# untitled.net
KiCad netlist of a schematic drawn in EAGLE
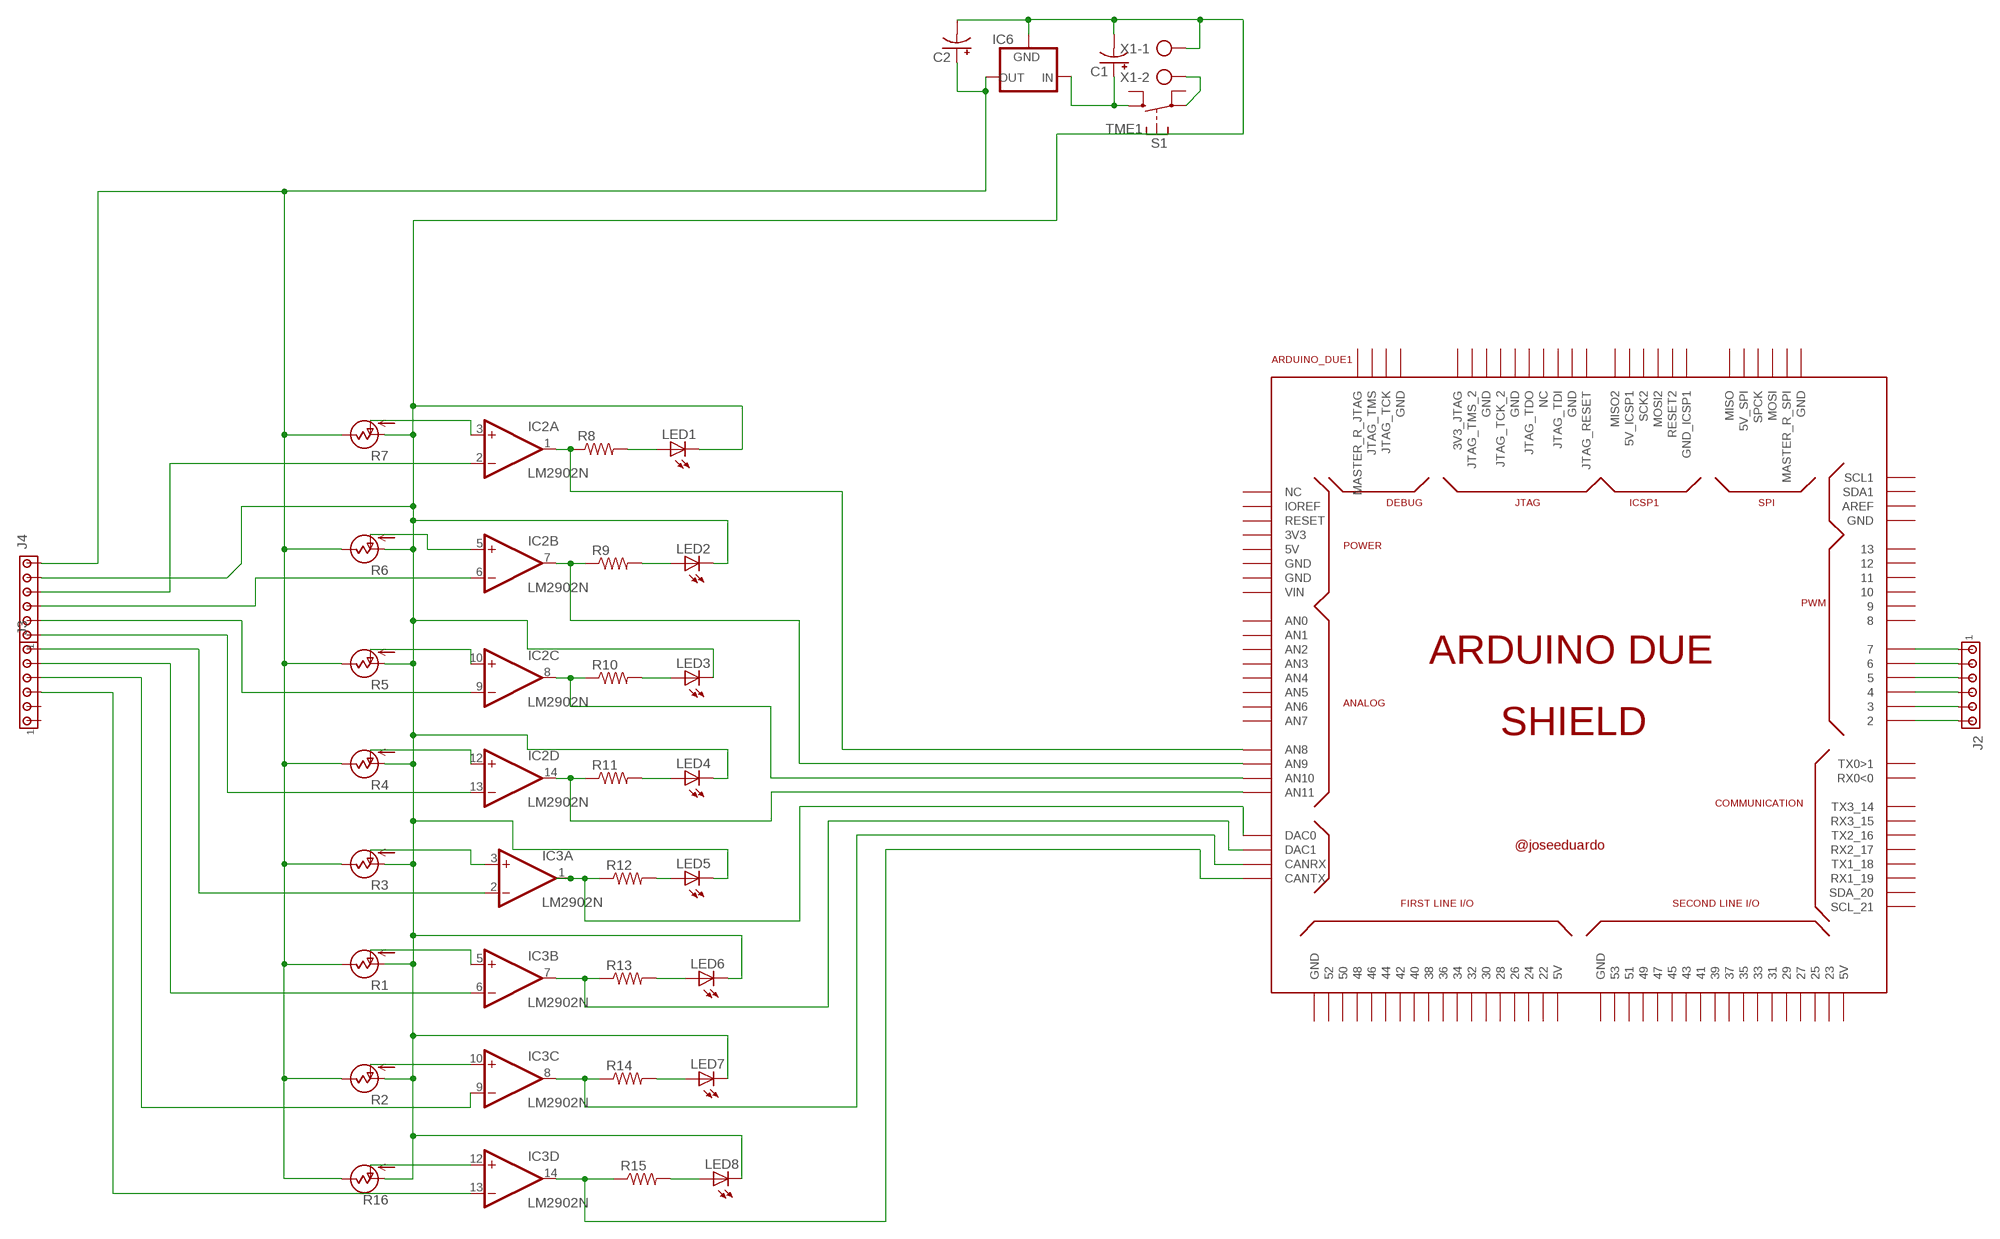
[diagram p0: schematic, sheet 1]
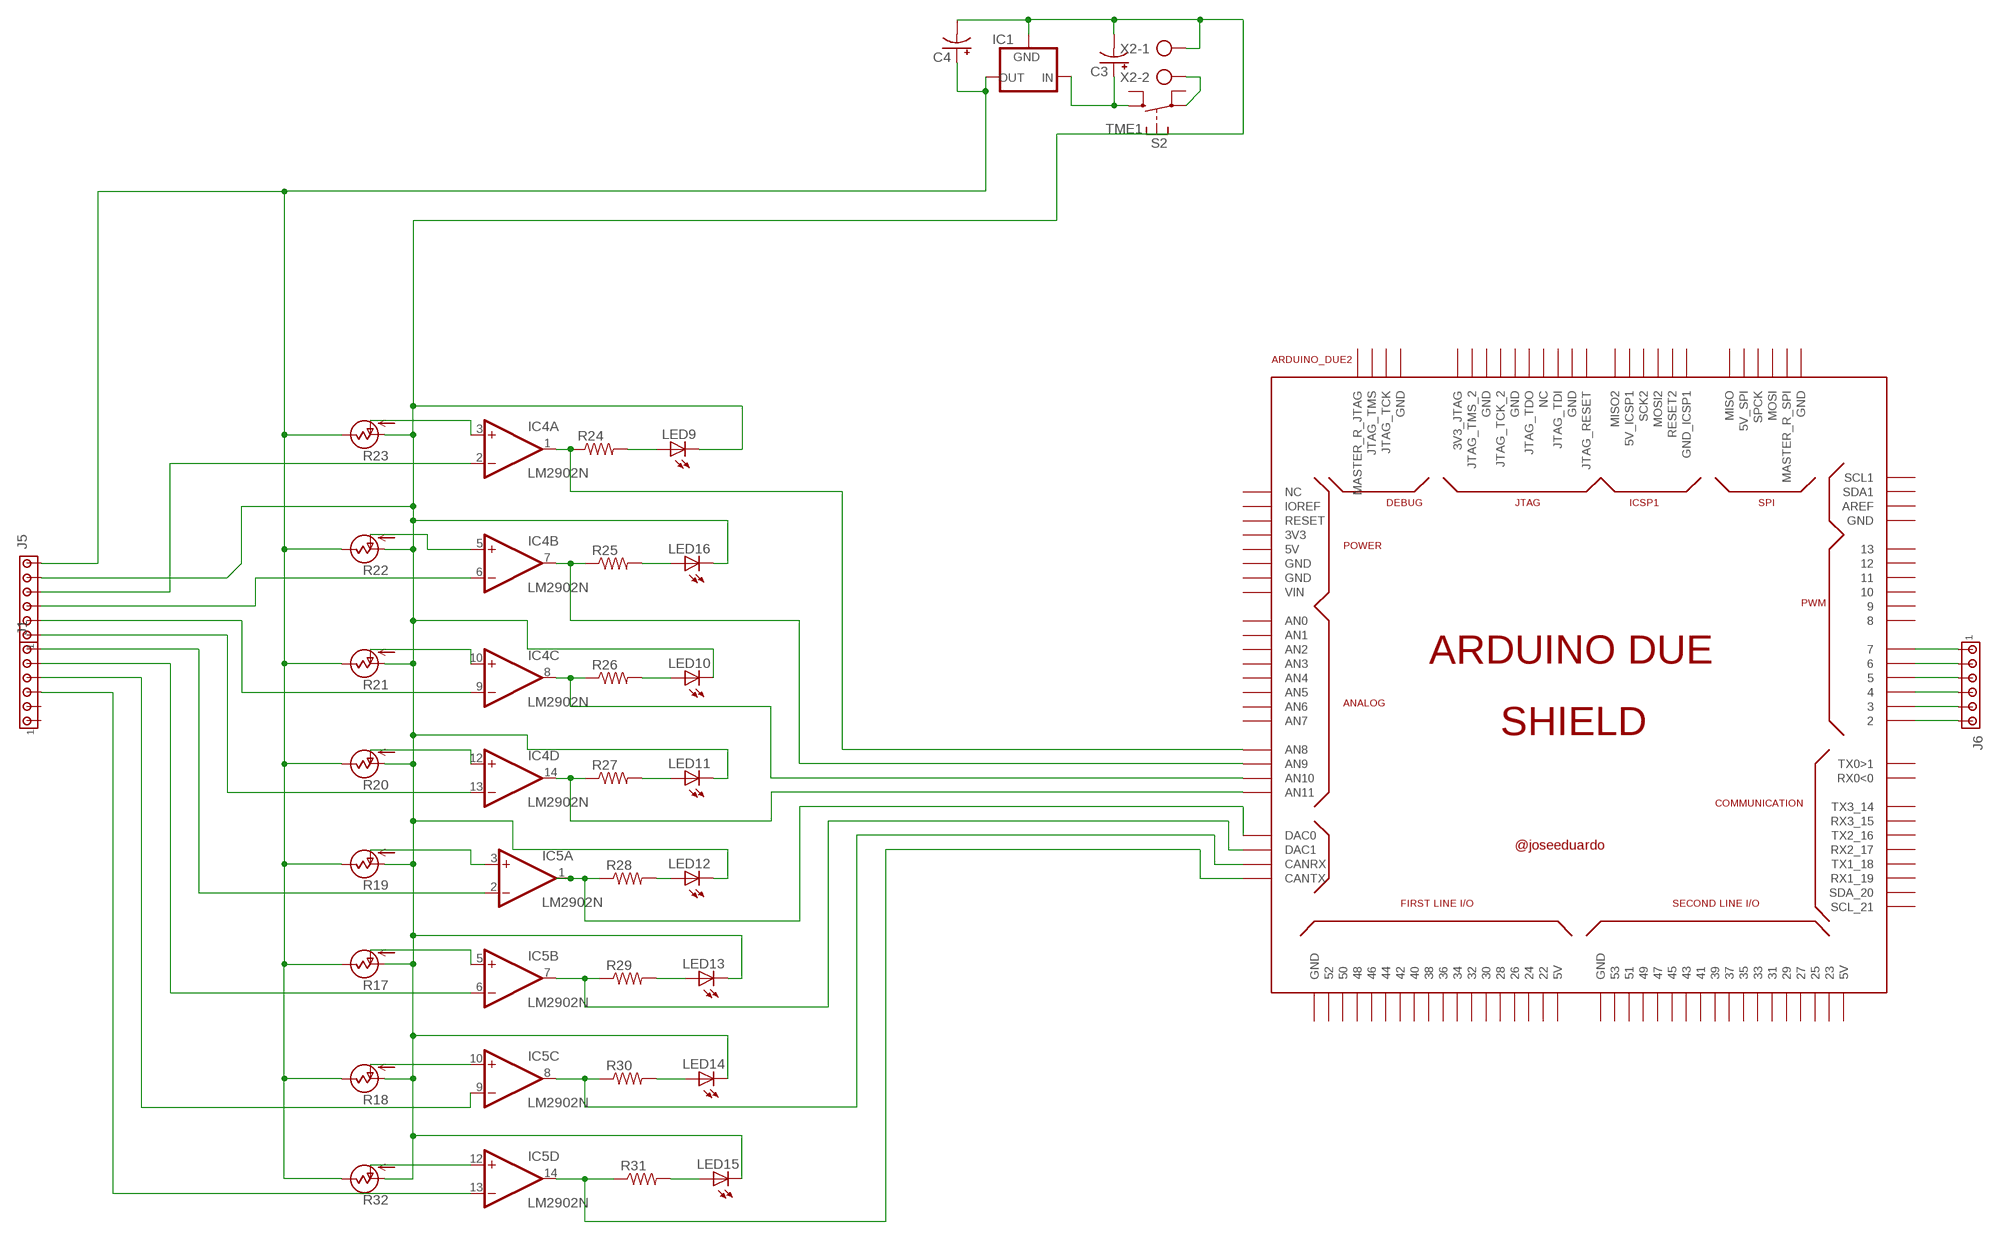
[diagram p1: schematic, sheet 2]
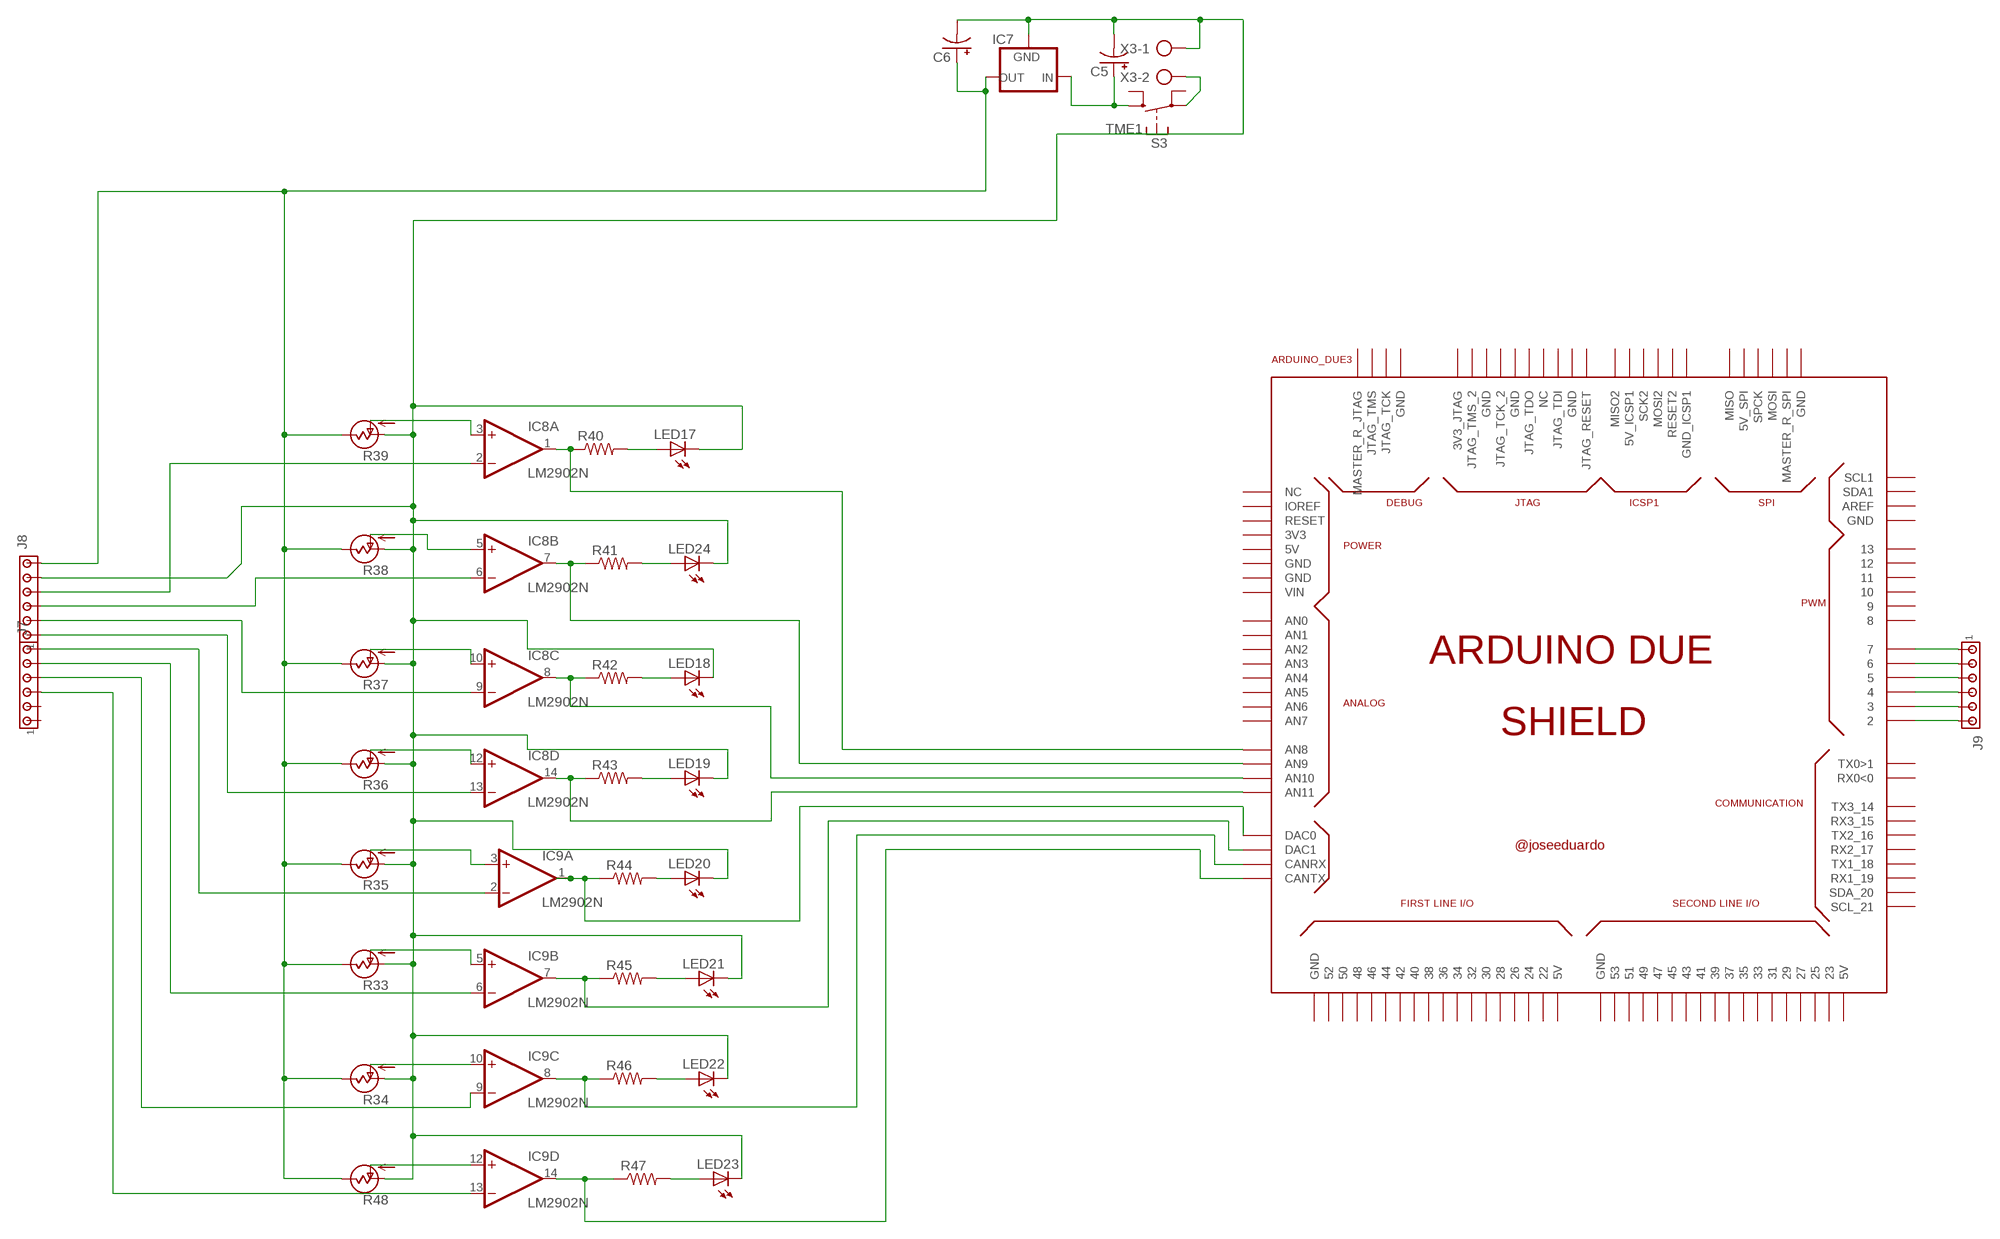
[diagram p2: schematic, sheet 3]
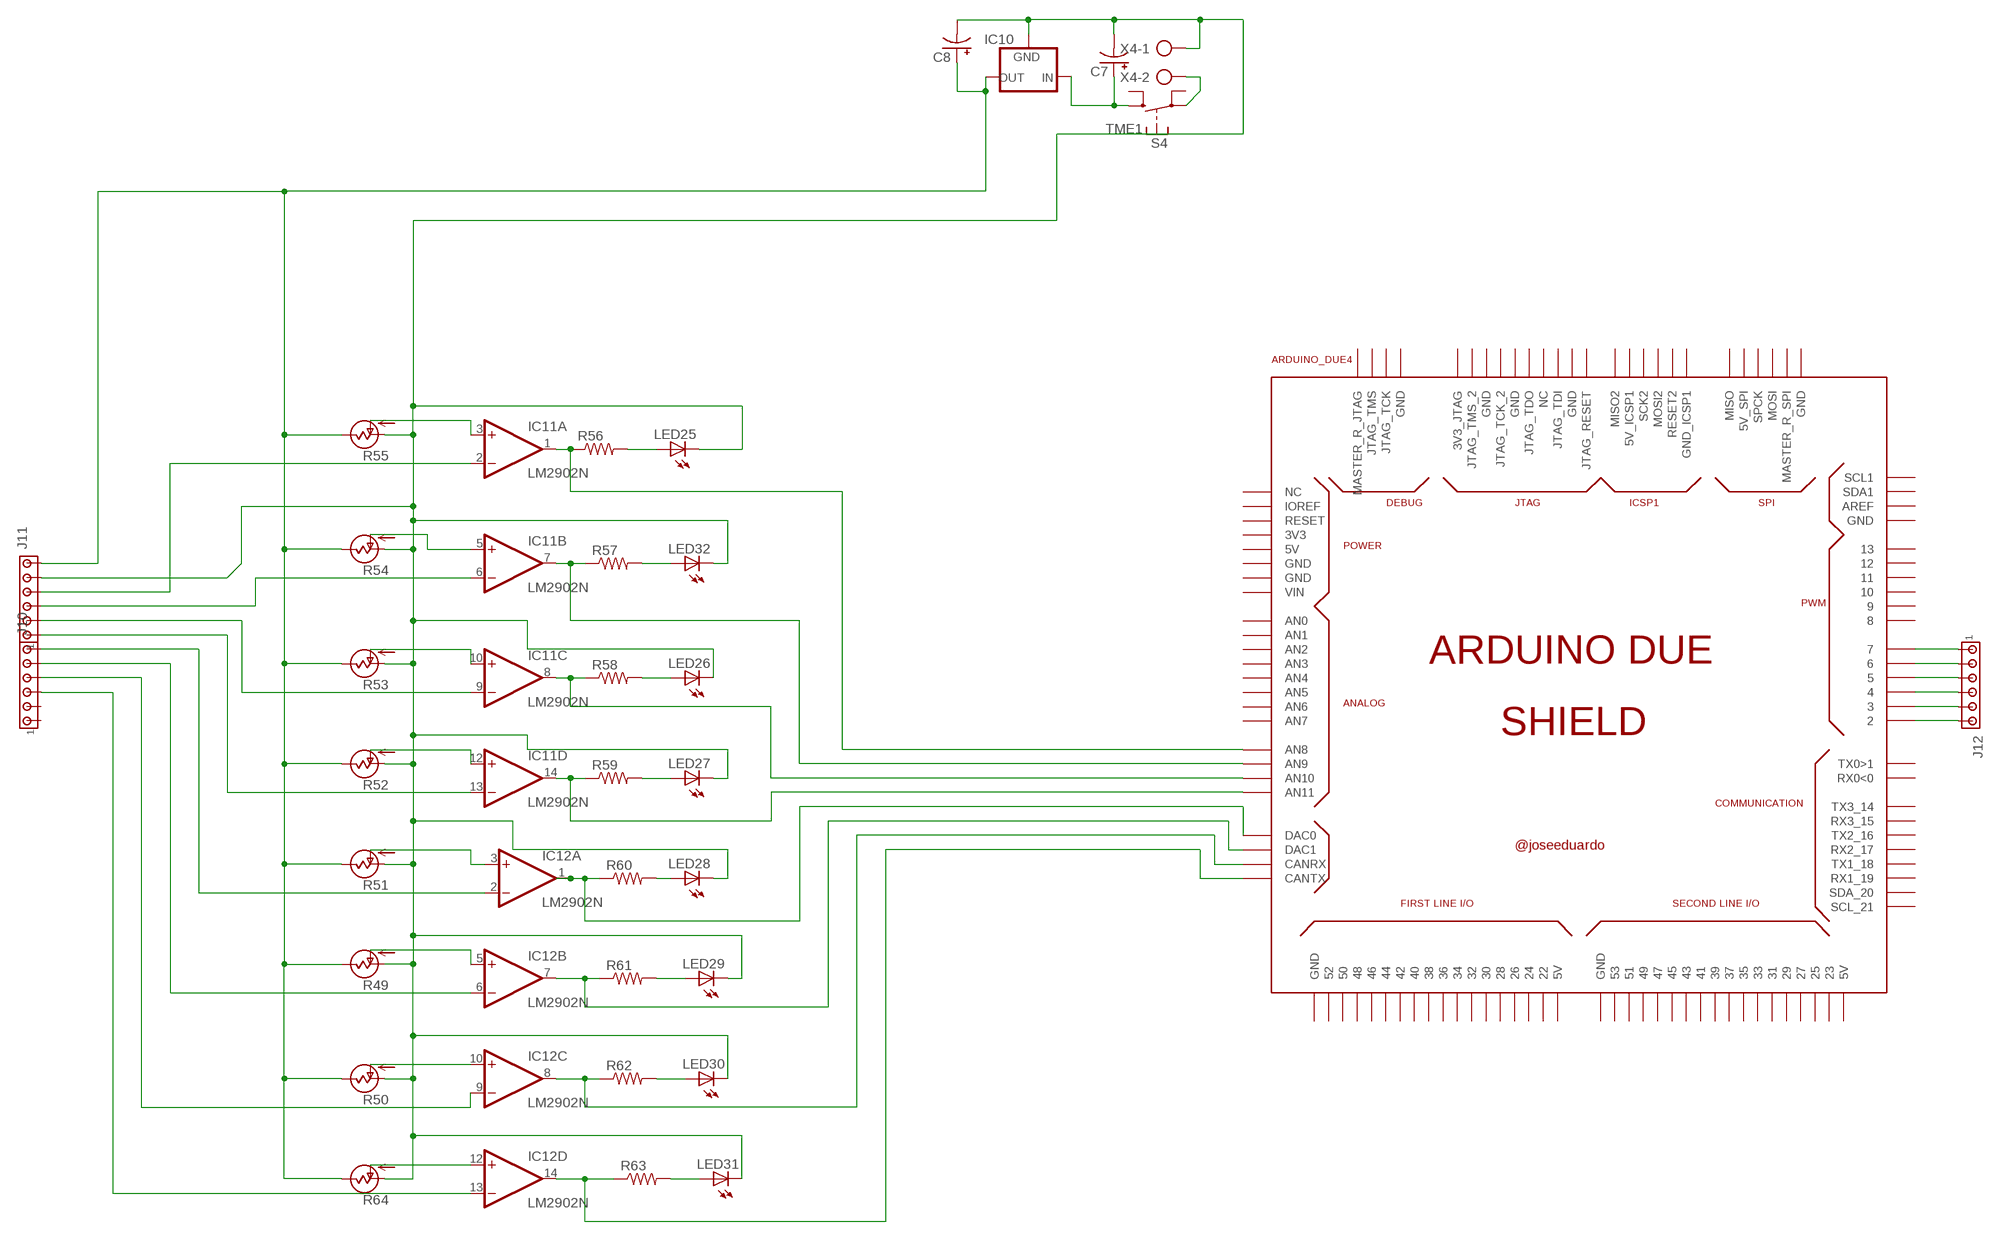
[diagram p3: schematic, sheet 4]

(export (version "E")
  (design (tool "Eeschema 10.0.6"))
  (components
    (comp (ref "ARDUINO_DUE1")
      (value "ARDUINO_DUE_SHIELD")
      (footprint "eagle-import:ARDUINO_DUE_SHIELD")
      (libsource (lib "eagle-import") (part "ARDUINO_DUE_SHIELD"))
    )
    (comp (ref "C1")
      (value "CPOL-USE5-10.5")
      (footprint "eagle-import:E5-10,5")
      (libsource (lib "eagle-import") (part "CPOL-USE5-10.5"))
    )
    (comp (ref "C2")
      (value "CPOL-USE5-10.5")
      (footprint "eagle-import:E5-10,5")
      (libsource (lib "eagle-import") (part "CPOL-USE5-10.5"))
    )
    (comp (ref "IC2")
      (value "LM2902N")
      (footprint "eagle-import:DIL14")
      (libsource (lib "eagle-import") (part "LM2902N"))
    )
    (comp (ref "IC3")
      (value "LM2902N")
      (footprint "eagle-import:DIL14")
      (libsource (lib "eagle-import") (part "LM2902N"))
    )
    (comp (ref "IC6")
      (value "V_REG_78XXSIDE")
      (footprint "eagle-import:78XXL")
      (libsource (lib "eagle-import") (part "V_REG_78XXSIDE"))
    )
    (comp (ref "J2")
      (value "MTA06-156")
      (footprint "eagle-import:1X6MTA")
      (libsource (lib "eagle-import") (part "MTA06-156"))
    )
    (comp (ref "J3")
      (value "MTA06-156")
      (footprint "eagle-import:1X6MTA")
      (libsource (lib "eagle-import") (part "MTA06-156"))
    )
    (comp (ref "J4")
      (value "MTA06-156")
      (footprint "eagle-import:1X6MTA")
      (libsource (lib "eagle-import") (part "MTA06-156"))
    )
    (comp (ref "LED1")
      (value "LED3MM")
      (footprint "eagle-import:LED3MM")
      (libsource (lib "eagle-import") (part "LED3MM"))
    )
    (comp (ref "LED2")
      (value "LED3MM")
      (footprint "eagle-import:LED3MM")
      (libsource (lib "eagle-import") (part "LED3MM"))
    )
    (comp (ref "LED3")
      (value "LED3MM")
      (footprint "eagle-import:LED3MM")
      (libsource (lib "eagle-import") (part "LED3MM"))
    )
    (comp (ref "LED4")
      (value "LED3MM")
      (footprint "eagle-import:LED3MM")
      (libsource (lib "eagle-import") (part "LED3MM"))
    )
    (comp (ref "LED5")
      (value "LED3MM")
      (footprint "eagle-import:LED3MM")
      (libsource (lib "eagle-import") (part "LED3MM"))
    )
    (comp (ref "LED6")
      (value "LED3MM")
      (footprint "eagle-import:LED3MM")
      (libsource (lib "eagle-import") (part "LED3MM"))
    )
    (comp (ref "LED7")
      (value "LED3MM")
      (footprint "eagle-import:LED3MM")
      (libsource (lib "eagle-import") (part "LED3MM"))
    )
    (comp (ref "LED8")
      (value "LED3MM")
      (footprint "eagle-import:LED3MM")
      (libsource (lib "eagle-import") (part "LED3MM"))
    )
    (comp (ref "R1")
      (value "POTTRS63P")
      (footprint "eagle-import:S63P")
      (libsource (lib "eagle-import") (part "POTTRS63P"))
    )
    (comp (ref "R2")
      (value "POTTRS63P")
      (footprint "eagle-import:S63P")
      (libsource (lib "eagle-import") (part "POTTRS63P"))
    )
    (comp (ref "R3")
      (value "POTTRS63P")
      (footprint "eagle-import:S63P")
      (libsource (lib "eagle-import") (part "POTTRS63P"))
    )
    (comp (ref "R4")
      (value "POTTRS63P")
      (footprint "eagle-import:S63P")
      (libsource (lib "eagle-import") (part "POTTRS63P"))
    )
    (comp (ref "R5")
      (value "POTTRS63P")
      (footprint "eagle-import:S63P")
      (libsource (lib "eagle-import") (part "POTTRS63P"))
    )
    (comp (ref "R6")
      (value "POTTRS63P")
      (footprint "eagle-import:S63P")
      (libsource (lib "eagle-import") (part "POTTRS63P"))
    )
    (comp (ref "R7")
      (value "POTTRS63P")
      (footprint "eagle-import:S63P")
      (libsource (lib "eagle-import") (part "POTTRS63P"))
    )
    (comp (ref "R8")
      (value "R-US_0207/10")
      (footprint "eagle-import:0207_10")
      (libsource (lib "eagle-import") (part "R-US_0207/10"))
    )
    (comp (ref "R9")
      (value "R-US_0207/10")
      (footprint "eagle-import:0207_10")
      (libsource (lib "eagle-import") (part "R-US_0207/10"))
    )
    (comp (ref "R10")
      (value "R-US_0207/10")
      (footprint "eagle-import:0207_10")
      (libsource (lib "eagle-import") (part "R-US_0207/10"))
    )
    (comp (ref "R11")
      (value "R-US_0207/10")
      (footprint "eagle-import:0207_10")
      (libsource (lib "eagle-import") (part "R-US_0207/10"))
    )
    (comp (ref "R12")
      (value "R-US_0207/10")
      (footprint "eagle-import:0207_10")
      (libsource (lib "eagle-import") (part "R-US_0207/10"))
    )
    (comp (ref "R13")
      (value "R-US_0207/10")
      (footprint "eagle-import:0207_10")
      (libsource (lib "eagle-import") (part "R-US_0207/10"))
    )
    (comp (ref "R14")
      (value "R-US_0207/10")
      (footprint "eagle-import:0207_10")
      (libsource (lib "eagle-import") (part "R-US_0207/10"))
    )
    (comp (ref "R15")
      (value "R-US_0207/10")
      (footprint "eagle-import:0207_10")
      (libsource (lib "eagle-import") (part "R-US_0207/10"))
    )
    (comp (ref "R16")
      (value "POTTRS63P")
      (footprint "eagle-import:S63P")
      (libsource (lib "eagle-import") (part "POTTRS63P"))
    )
    (comp (ref "S1")
      (value "TME1")
      (footprint "eagle-import:TME1")
      (libsource (lib "eagle-import") (part "TME1"))
    )
    (comp (ref "X1")
      (value "AK300/2")
      (footprint "eagle-import:AK300_2")
      (libsource (lib "eagle-import") (part "AK300/2"))
    )
    (comp (ref "ARDUINO_DUE3")
      (value "ARDUINO_DUE_SHIELD")
      (footprint "eagle-import:ARDUINO_DUE_SHIELD")
      (libsource (lib "eagle-import") (part "ARDUINO_DUE_SHIELD"))
    )
    (comp (ref "C5")
      (value "CPOL-USE5-10.5")
      (footprint "eagle-import:E5-10,5")
      (libsource (lib "eagle-import") (part "CPOL-USE5-10.5"))
    )
    (comp (ref "C6")
      (value "CPOL-USE5-10.5")
      (footprint "eagle-import:E5-10,5")
      (libsource (lib "eagle-import") (part "CPOL-USE5-10.5"))
    )
    (comp (ref "IC7")
      (value "V_REG_78XXSIDE")
      (footprint "eagle-import:78XXL")
      (libsource (lib "eagle-import") (part "V_REG_78XXSIDE"))
    )
    (comp (ref "IC8")
      (value "LM2902N")
      (footprint "eagle-import:DIL14")
      (libsource (lib "eagle-import") (part "LM2902N"))
    )
    (comp (ref "IC9")
      (value "LM2902N")
      (footprint "eagle-import:DIL14")
      (libsource (lib "eagle-import") (part "LM2902N"))
    )
    (comp (ref "J7")
      (value "MTA06-156")
      (footprint "eagle-import:1X6MTA")
      (libsource (lib "eagle-import") (part "MTA06-156"))
    )
    (comp (ref "J8")
      (value "MTA06-156")
      (footprint "eagle-import:1X6MTA")
      (libsource (lib "eagle-import") (part "MTA06-156"))
    )
    (comp (ref "J9")
      (value "MTA06-156")
      (footprint "eagle-import:1X6MTA")
      (libsource (lib "eagle-import") (part "MTA06-156"))
    )
    (comp (ref "LED17")
      (value "LED3MM")
      (footprint "eagle-import:LED3MM")
      (libsource (lib "eagle-import") (part "LED3MM"))
    )
    (comp (ref "LED18")
      (value "LED3MM")
      (footprint "eagle-import:LED3MM")
      (libsource (lib "eagle-import") (part "LED3MM"))
    )
    (comp (ref "LED19")
      (value "LED3MM")
      (footprint "eagle-import:LED3MM")
      (libsource (lib "eagle-import") (part "LED3MM"))
    )
    (comp (ref "LED20")
      (value "LED3MM")
      (footprint "eagle-import:LED3MM")
      (libsource (lib "eagle-import") (part "LED3MM"))
    )
    (comp (ref "LED21")
      (value "LED3MM")
      (footprint "eagle-import:LED3MM")
      (libsource (lib "eagle-import") (part "LED3MM"))
    )
    (comp (ref "LED22")
      (value "LED3MM")
      (footprint "eagle-import:LED3MM")
      (libsource (lib "eagle-import") (part "LED3MM"))
    )
    (comp (ref "LED23")
      (value "LED3MM")
      (footprint "eagle-import:LED3MM")
      (libsource (lib "eagle-import") (part "LED3MM"))
    )
    (comp (ref "LED24")
      (value "LED3MM")
      (footprint "eagle-import:LED3MM")
      (libsource (lib "eagle-import") (part "LED3MM"))
    )
    (comp (ref "R33")
      (value "POTTRS63P")
      (footprint "eagle-import:S63P")
      (libsource (lib "eagle-import") (part "POTTRS63P"))
    )
    (comp (ref "R34")
      (value "POTTRS63P")
      (footprint "eagle-import:S63P")
      (libsource (lib "eagle-import") (part "POTTRS63P"))
    )
    (comp (ref "R35")
      (value "POTTRS63P")
      (footprint "eagle-import:S63P")
      (libsource (lib "eagle-import") (part "POTTRS63P"))
    )
    (comp (ref "R36")
      (value "POTTRS63P")
      (footprint "eagle-import:S63P")
      (libsource (lib "eagle-import") (part "POTTRS63P"))
    )
    (comp (ref "R37")
      (value "POTTRS63P")
      (footprint "eagle-import:S63P")
      (libsource (lib "eagle-import") (part "POTTRS63P"))
    )
    (comp (ref "R38")
      (value "POTTRS63P")
      (footprint "eagle-import:S63P")
      (libsource (lib "eagle-import") (part "POTTRS63P"))
    )
    (comp (ref "R39")
      (value "POTTRS63P")
      (footprint "eagle-import:S63P")
      (libsource (lib "eagle-import") (part "POTTRS63P"))
    )
    (comp (ref "R40")
      (value "R-US_0207/10")
      (footprint "eagle-import:0207_10")
      (libsource (lib "eagle-import") (part "R-US_0207/10"))
    )
    (comp (ref "R41")
      (value "R-US_0207/10")
      (footprint "eagle-import:0207_10")
      (libsource (lib "eagle-import") (part "R-US_0207/10"))
    )
    (comp (ref "R42")
      (value "R-US_0207/10")
      (footprint "eagle-import:0207_10")
      (libsource (lib "eagle-import") (part "R-US_0207/10"))
    )
    (comp (ref "R43")
      (value "R-US_0207/10")
      (footprint "eagle-import:0207_10")
      (libsource (lib "eagle-import") (part "R-US_0207/10"))
    )
    (comp (ref "R44")
      (value "R-US_0207/10")
      (footprint "eagle-import:0207_10")
      (libsource (lib "eagle-import") (part "R-US_0207/10"))
    )
    (comp (ref "R45")
      (value "R-US_0207/10")
      (footprint "eagle-import:0207_10")
      (libsource (lib "eagle-import") (part "R-US_0207/10"))
    )
    (comp (ref "R46")
      (value "R-US_0207/10")
      (footprint "eagle-import:0207_10")
      (libsource (lib "eagle-import") (part "R-US_0207/10"))
    )
    (comp (ref "R47")
      (value "R-US_0207/10")
      (footprint "eagle-import:0207_10")
      (libsource (lib "eagle-import") (part "R-US_0207/10"))
    )
    (comp (ref "R48")
      (value "POTTRS63P")
      (footprint "eagle-import:S63P")
      (libsource (lib "eagle-import") (part "POTTRS63P"))
    )
    (comp (ref "S3")
      (value "TME1")
      (footprint "eagle-import:TME1")
      (libsource (lib "eagle-import") (part "TME1"))
    )
    (comp (ref "X3")
      (value "AK300/2")
      (footprint "eagle-import:AK300_2")
      (libsource (lib "eagle-import") (part "AK300/2"))
    )
    (comp (ref "ARDUINO_DUE2")
      (value "ARDUINO_DUE_SHIELD")
      (footprint "eagle-import:ARDUINO_DUE_SHIELD")
      (libsource (lib "eagle-import") (part "ARDUINO_DUE_SHIELD"))
    )
    (comp (ref "C3")
      (value "CPOL-USE5-10.5")
      (footprint "eagle-import:E5-10,5")
      (libsource (lib "eagle-import") (part "CPOL-USE5-10.5"))
    )
    (comp (ref "C4")
      (value "CPOL-USE5-10.5")
      (footprint "eagle-import:E5-10,5")
      (libsource (lib "eagle-import") (part "CPOL-USE5-10.5"))
    )
    (comp (ref "IC1")
      (value "V_REG_78XXSIDE")
      (footprint "eagle-import:78XXL")
      (libsource (lib "eagle-import") (part "V_REG_78XXSIDE"))
    )
    (comp (ref "IC4")
      (value "LM2902N")
      (footprint "eagle-import:DIL14")
      (libsource (lib "eagle-import") (part "LM2902N"))
    )
    (comp (ref "IC5")
      (value "LM2902N")
      (footprint "eagle-import:DIL14")
      (libsource (lib "eagle-import") (part "LM2902N"))
    )
    (comp (ref "J1")
      (value "MTA06-156")
      (footprint "eagle-import:1X6MTA")
      (libsource (lib "eagle-import") (part "MTA06-156"))
    )
    (comp (ref "J5")
      (value "MTA06-156")
      (footprint "eagle-import:1X6MTA")
      (libsource (lib "eagle-import") (part "MTA06-156"))
    )
    (comp (ref "J6")
      (value "MTA06-156")
      (footprint "eagle-import:1X6MTA")
      (libsource (lib "eagle-import") (part "MTA06-156"))
    )
    (comp (ref "LED9")
      (value "LED3MM")
      (footprint "eagle-import:LED3MM")
      (libsource (lib "eagle-import") (part "LED3MM"))
    )
    (comp (ref "LED10")
      (value "LED3MM")
      (footprint "eagle-import:LED3MM")
      (libsource (lib "eagle-import") (part "LED3MM"))
    )
    (comp (ref "LED11")
      (value "LED3MM")
      (footprint "eagle-import:LED3MM")
      (libsource (lib "eagle-import") (part "LED3MM"))
    )
    (comp (ref "LED12")
      (value "LED3MM")
      (footprint "eagle-import:LED3MM")
      (libsource (lib "eagle-import") (part "LED3MM"))
    )
    (comp (ref "LED13")
      (value "LED3MM")
      (footprint "eagle-import:LED3MM")
      (libsource (lib "eagle-import") (part "LED3MM"))
    )
    (comp (ref "LED14")
      (value "LED3MM")
      (footprint "eagle-import:LED3MM")
      (libsource (lib "eagle-import") (part "LED3MM"))
    )
    (comp (ref "LED15")
      (value "LED3MM")
      (footprint "eagle-import:LED3MM")
      (libsource (lib "eagle-import") (part "LED3MM"))
    )
    (comp (ref "LED16")
      (value "LED3MM")
      (footprint "eagle-import:LED3MM")
      (libsource (lib "eagle-import") (part "LED3MM"))
    )
    (comp (ref "R17")
      (value "POTTRS63P")
      (footprint "eagle-import:S63P")
      (libsource (lib "eagle-import") (part "POTTRS63P"))
    )
    (comp (ref "R18")
      (value "POTTRS63P")
      (footprint "eagle-import:S63P")
      (libsource (lib "eagle-import") (part "POTTRS63P"))
    )
    (comp (ref "R19")
      (value "POTTRS63P")
      (footprint "eagle-import:S63P")
      (libsource (lib "eagle-import") (part "POTTRS63P"))
    )
    (comp (ref "R20")
      (value "POTTRS63P")
      (footprint "eagle-import:S63P")
      (libsource (lib "eagle-import") (part "POTTRS63P"))
    )
    (comp (ref "R21")
      (value "POTTRS63P")
      (footprint "eagle-import:S63P")
      (libsource (lib "eagle-import") (part "POTTRS63P"))
    )
    (comp (ref "R22")
      (value "POTTRS63P")
      (footprint "eagle-import:S63P")
      (libsource (lib "eagle-import") (part "POTTRS63P"))
    )
    (comp (ref "R23")
      (value "POTTRS63P")
      (footprint "eagle-import:S63P")
      (libsource (lib "eagle-import") (part "POTTRS63P"))
    )
    (comp (ref "R24")
      (value "R-US_0207/10")
      (footprint "eagle-import:0207_10")
      (libsource (lib "eagle-import") (part "R-US_0207/10"))
    )
    (comp (ref "R25")
      (value "R-US_0207/10")
      (footprint "eagle-import:0207_10")
      (libsource (lib "eagle-import") (part "R-US_0207/10"))
    )
    (comp (ref "R26")
      (value "R-US_0207/10")
      (footprint "eagle-import:0207_10")
      (libsource (lib "eagle-import") (part "R-US_0207/10"))
    )
    (comp (ref "R27")
      (value "R-US_0207/10")
      (footprint "eagle-import:0207_10")
      (libsource (lib "eagle-import") (part "R-US_0207/10"))
    )
    (comp (ref "R28")
      (value "R-US_0207/10")
      (footprint "eagle-import:0207_10")
      (libsource (lib "eagle-import") (part "R-US_0207/10"))
    )
    (comp (ref "R29")
      (value "R-US_0207/10")
      (footprint "eagle-import:0207_10")
      (libsource (lib "eagle-import") (part "R-US_0207/10"))
    )
    (comp (ref "R30")
      (value "R-US_0207/10")
      (footprint "eagle-import:0207_10")
      (libsource (lib "eagle-import") (part "R-US_0207/10"))
    )
    (comp (ref "R31")
      (value "R-US_0207/10")
      (footprint "eagle-import:0207_10")
      (libsource (lib "eagle-import") (part "R-US_0207/10"))
    )
    (comp (ref "R32")
      (value "POTTRS63P")
      (footprint "eagle-import:S63P")
      (libsource (lib "eagle-import") (part "POTTRS63P"))
    )
    (comp (ref "S2")
      (value "TME1")
      (footprint "eagle-import:TME1")
      (libsource (lib "eagle-import") (part "TME1"))
    )
    (comp (ref "X2")
      (value "AK300/2")
      (footprint "eagle-import:AK300_2")
      (libsource (lib "eagle-import") (part "AK300/2"))
    )
    (comp (ref "ARDUINO_DUE4")
      (value "ARDUINO_DUE_SHIELD")
      (footprint "eagle-import:ARDUINO_DUE_SHIELD")
      (libsource (lib "eagle-import") (part "ARDUINO_DUE_SHIELD"))
    )
    (comp (ref "C7")
      (value "CPOL-USE5-10.5")
      (footprint "eagle-import:E5-10,5")
      (libsource (lib "eagle-import") (part "CPOL-USE5-10.5"))
    )
    (comp (ref "C8")
      (value "CPOL-USE5-10.5")
      (footprint "eagle-import:E5-10,5")
      (libsource (lib "eagle-import") (part "CPOL-USE5-10.5"))
    )
    (comp (ref "IC10")
      (value "V_REG_78XXSIDE")
      (footprint "eagle-import:78XXL")
      (libsource (lib "eagle-import") (part "V_REG_78XXSIDE"))
    )
    (comp (ref "IC11")
      (value "LM2902N")
      (footprint "eagle-import:DIL14")
      (libsource (lib "eagle-import") (part "LM2902N"))
    )
    (comp (ref "IC12")
      (value "LM2902N")
      (footprint "eagle-import:DIL14")
      (libsource (lib "eagle-import") (part "LM2902N"))
    )
    (comp (ref "J10")
      (value "MTA06-156")
      (footprint "eagle-import:1X6MTA")
      (libsource (lib "eagle-import") (part "MTA06-156"))
    )
    (comp (ref "J11")
      (value "MTA06-156")
      (footprint "eagle-import:1X6MTA")
      (libsource (lib "eagle-import") (part "MTA06-156"))
    )
    (comp (ref "J12")
      (value "MTA06-156")
      (footprint "eagle-import:1X6MTA")
      (libsource (lib "eagle-import") (part "MTA06-156"))
    )
    (comp (ref "LED25")
      (value "LED3MM")
      (footprint "eagle-import:LED3MM")
      (libsource (lib "eagle-import") (part "LED3MM"))
    )
    (comp (ref "LED26")
      (value "LED3MM")
      (footprint "eagle-import:LED3MM")
      (libsource (lib "eagle-import") (part "LED3MM"))
    )
    (comp (ref "LED27")
      (value "LED3MM")
      (footprint "eagle-import:LED3MM")
      (libsource (lib "eagle-import") (part "LED3MM"))
    )
    (comp (ref "LED28")
      (value "LED3MM")
      (footprint "eagle-import:LED3MM")
      (libsource (lib "eagle-import") (part "LED3MM"))
    )
    (comp (ref "LED29")
      (value "LED3MM")
      (footprint "eagle-import:LED3MM")
      (libsource (lib "eagle-import") (part "LED3MM"))
    )
    (comp (ref "LED30")
      (value "LED3MM")
      (footprint "eagle-import:LED3MM")
      (libsource (lib "eagle-import") (part "LED3MM"))
    )
    (comp (ref "LED31")
      (value "LED3MM")
      (footprint "eagle-import:LED3MM")
      (libsource (lib "eagle-import") (part "LED3MM"))
    )
    (comp (ref "LED32")
      (value "LED3MM")
      (footprint "eagle-import:LED3MM")
      (libsource (lib "eagle-import") (part "LED3MM"))
    )
    (comp (ref "R49")
      (value "POTTRS63P")
      (footprint "eagle-import:S63P")
      (libsource (lib "eagle-import") (part "POTTRS63P"))
    )
    (comp (ref "R50")
      (value "POTTRS63P")
      (footprint "eagle-import:S63P")
      (libsource (lib "eagle-import") (part "POTTRS63P"))
    )
    (comp (ref "R51")
      (value "POTTRS63P")
      (footprint "eagle-import:S63P")
      (libsource (lib "eagle-import") (part "POTTRS63P"))
    )
    (comp (ref "R52")
      (value "POTTRS63P")
      (footprint "eagle-import:S63P")
      (libsource (lib "eagle-import") (part "POTTRS63P"))
    )
    (comp (ref "R53")
      (value "POTTRS63P")
      (footprint "eagle-import:S63P")
      (libsource (lib "eagle-import") (part "POTTRS63P"))
    )
    (comp (ref "R54")
      (value "POTTRS63P")
      (footprint "eagle-import:S63P")
      (libsource (lib "eagle-import") (part "POTTRS63P"))
    )
    (comp (ref "R55")
      (value "POTTRS63P")
      (footprint "eagle-import:S63P")
      (libsource (lib "eagle-import") (part "POTTRS63P"))
    )
    (comp (ref "R56")
      (value "R-US_0207/10")
      (footprint "eagle-import:0207_10")
      (libsource (lib "eagle-import") (part "R-US_0207/10"))
    )
    (comp (ref "R57")
      (value "R-US_0207/10")
      (footprint "eagle-import:0207_10")
      (libsource (lib "eagle-import") (part "R-US_0207/10"))
    )
    (comp (ref "R58")
      (value "R-US_0207/10")
      (footprint "eagle-import:0207_10")
      (libsource (lib "eagle-import") (part "R-US_0207/10"))
    )
    (comp (ref "R59")
      (value "R-US_0207/10")
      (footprint "eagle-import:0207_10")
      (libsource (lib "eagle-import") (part "R-US_0207/10"))
    )
    (comp (ref "R60")
      (value "R-US_0207/10")
      (footprint "eagle-import:0207_10")
      (libsource (lib "eagle-import") (part "R-US_0207/10"))
    )
    (comp (ref "R61")
      (value "R-US_0207/10")
      (footprint "eagle-import:0207_10")
      (libsource (lib "eagle-import") (part "R-US_0207/10"))
    )
    (comp (ref "R62")
      (value "R-US_0207/10")
      (footprint "eagle-import:0207_10")
      (libsource (lib "eagle-import") (part "R-US_0207/10"))
    )
    (comp (ref "R63")
      (value "R-US_0207/10")
      (footprint "eagle-import:0207_10")
      (libsource (lib "eagle-import") (part "R-US_0207/10"))
    )
    (comp (ref "R64")
      (value "POTTRS63P")
      (footprint "eagle-import:S63P")
      (libsource (lib "eagle-import") (part "POTTRS63P"))
    )
    (comp (ref "S4")
      (value "TME1")
      (footprint "eagle-import:TME1")
      (libsource (lib "eagle-import") (part "TME1"))
    )
    (comp (ref "X4")
      (value "AK300/2")
      (footprint "eagle-import:AK300_2")
      (libsource (lib "eagle-import") (part "AK300/2"))
    )
  )
  (nets
    (net (code "1") (name "Net-(ARDUINO_DUE1-AN8)") (class "Default")
      (node (ref "ARDUINO_DUE1") (pin "A8") (pinfunction "AN8_A8") (pintype "bidirectional"))
      (node (ref "IC2") (pin "1") (pinfunction "OUT_1") (pintype "output"))
      (node (ref "R8") (pin "1") (pinfunction "1_1") (pintype "passive"))
    )
    (net (code "2") (name "Net-(ARDUINO_DUE1-AN9)") (class "Default")
      (node (ref "ARDUINO_DUE1") (pin "A9") (pinfunction "AN9_A9") (pintype "bidirectional"))
      (node (ref "IC2") (pin "7") (pinfunction "OUT_7") (pintype "output"))
      (node (ref "R9") (pin "1") (pinfunction "1_1") (pintype "passive"))
    )
    (net (code "3") (name "Net-(ARDUINO_DUE1-AN10)") (class "Default")
      (node (ref "ARDUINO_DUE1") (pin "A10") (pinfunction "AN10_A10") (pintype "bidirectional"))
      (node (ref "IC2") (pin "8") (pinfunction "OUT_8") (pintype "output"))
      (node (ref "R10") (pin "1") (pinfunction "1_1") (pintype "passive"))
    )
    (net (code "4") (name "Net-(ARDUINO_DUE1-AN11)") (class "Default")
      (node (ref "ARDUINO_DUE1") (pin "A11") (pinfunction "AN11_A11") (pintype "bidirectional"))
      (node (ref "IC2") (pin "14") (pinfunction "OUT_14") (pintype "output"))
      (node (ref "R11") (pin "1") (pinfunction "1_1") (pintype "passive"))
    )
    (net (code "5") (name "Net-(ARDUINO_DUE1-Pad2)") (class "Default")
      (node (ref "ARDUINO_DUE1") (pin "2") (pinfunction "2_2") (pintype "bidirectional"))
      (node (ref "J2") (pin "6") (pinfunction "6_6") (pintype "passive"))
    )
    (net (code "6") (name "Net-(ARDUINO_DUE1-Pad3)") (class "Default")
      (node (ref "ARDUINO_DUE1") (pin "3") (pinfunction "3_3") (pintype "bidirectional"))
      (node (ref "J2") (pin "5") (pinfunction "5_5") (pintype "passive"))
    )
    (net (code "7") (name "Net-(ARDUINO_DUE1-Pad4)") (class "Default")
      (node (ref "ARDUINO_DUE1") (pin "4") (pinfunction "4_4") (pintype "bidirectional"))
      (node (ref "J2") (pin "4") (pinfunction "4_4") (pintype "passive"))
    )
    (net (code "8") (name "Net-(ARDUINO_DUE1-Pad5)") (class "Default")
      (node (ref "ARDUINO_DUE1") (pin "5") (pinfunction "5_5") (pintype "bidirectional"))
      (node (ref "J2") (pin "3") (pinfunction "3_3") (pintype "passive"))
    )
    (net (code "9") (name "Net-(ARDUINO_DUE1-Pad6)") (class "Default")
      (node (ref "ARDUINO_DUE1") (pin "6") (pinfunction "6_6") (pintype "bidirectional"))
      (node (ref "J2") (pin "2") (pinfunction "2_2") (pintype "passive"))
    )
    (net (code "10") (name "Net-(ARDUINO_DUE1-Pad7)") (class "Default")
      (node (ref "ARDUINO_DUE1") (pin "7") (pinfunction "7_7") (pintype "bidirectional"))
      (node (ref "J2") (pin "1") (pinfunction "1_1") (pintype "passive"))
    )
    (net (code "11") (name "Net-(ARDUINO_DUE2-AN8)") (class "Default")
      (node (ref "ARDUINO_DUE2") (pin "A8") (pinfunction "AN8_A8") (pintype "bidirectional"))
      (node (ref "IC4") (pin "1") (pinfunction "OUT_1") (pintype "output"))
      (node (ref "R24") (pin "1") (pinfunction "1_1") (pintype "passive"))
    )
    (net (code "12") (name "Net-(ARDUINO_DUE2-AN9)") (class "Default")
      (node (ref "ARDUINO_DUE2") (pin "A9") (pinfunction "AN9_A9") (pintype "bidirectional"))
      (node (ref "IC4") (pin "7") (pinfunction "OUT_7") (pintype "output"))
      (node (ref "R25") (pin "1") (pinfunction "1_1") (pintype "passive"))
    )
    (net (code "13") (name "Net-(ARDUINO_DUE2-AN10)") (class "Default")
      (node (ref "ARDUINO_DUE2") (pin "A10") (pinfunction "AN10_A10") (pintype "bidirectional"))
      (node (ref "IC4") (pin "8") (pinfunction "OUT_8") (pintype "output"))
      (node (ref "R26") (pin "1") (pinfunction "1_1") (pintype "passive"))
    )
    (net (code "14") (name "Net-(ARDUINO_DUE2-AN11)") (class "Default")
      (node (ref "ARDUINO_DUE2") (pin "A11") (pinfunction "AN11_A11") (pintype "bidirectional"))
      (node (ref "IC4") (pin "14") (pinfunction "OUT_14") (pintype "output"))
      (node (ref "R27") (pin "1") (pinfunction "1_1") (pintype "passive"))
    )
    (net (code "15") (name "Net-(ARDUINO_DUE2-Pad2)") (class "Default")
      (node (ref "ARDUINO_DUE2") (pin "2") (pinfunction "2_2") (pintype "bidirectional"))
      (node (ref "J6") (pin "6") (pinfunction "6_6") (pintype "passive"))
    )
    (net (code "16") (name "Net-(ARDUINO_DUE2-Pad3)") (class "Default")
      (node (ref "ARDUINO_DUE2") (pin "3") (pinfunction "3_3") (pintype "bidirectional"))
      (node (ref "J6") (pin "5") (pinfunction "5_5") (pintype "passive"))
    )
    (net (code "17") (name "Net-(ARDUINO_DUE2-Pad4)") (class "Default")
      (node (ref "ARDUINO_DUE2") (pin "4") (pinfunction "4_4") (pintype "bidirectional"))
      (node (ref "J6") (pin "4") (pinfunction "4_4") (pintype "passive"))
    )
    (net (code "18") (name "Net-(ARDUINO_DUE2-Pad5)") (class "Default")
      (node (ref "ARDUINO_DUE2") (pin "5") (pinfunction "5_5") (pintype "bidirectional"))
      (node (ref "J6") (pin "3") (pinfunction "3_3") (pintype "passive"))
    )
    (net (code "19") (name "Net-(ARDUINO_DUE2-Pad6)") (class "Default")
      (node (ref "ARDUINO_DUE2") (pin "6") (pinfunction "6_6") (pintype "bidirectional"))
      (node (ref "J6") (pin "2") (pinfunction "2_2") (pintype "passive"))
    )
    (net (code "20") (name "Net-(ARDUINO_DUE2-Pad7)") (class "Default")
      (node (ref "ARDUINO_DUE2") (pin "7") (pinfunction "7_7") (pintype "bidirectional"))
      (node (ref "J6") (pin "1") (pinfunction "1_1") (pintype "passive"))
    )
    (net (code "21") (name "Net-(ARDUINO_DUE3-AN8)") (class "Default")
      (node (ref "ARDUINO_DUE3") (pin "A8") (pinfunction "AN8_A8") (pintype "bidirectional"))
      (node (ref "IC8") (pin "1") (pinfunction "OUT_1") (pintype "output"))
      (node (ref "R40") (pin "1") (pinfunction "1_1") (pintype "passive"))
    )
    (net (code "22") (name "Net-(ARDUINO_DUE3-AN9)") (class "Default")
      (node (ref "ARDUINO_DUE3") (pin "A9") (pinfunction "AN9_A9") (pintype "bidirectional"))
      (node (ref "IC8") (pin "7") (pinfunction "OUT_7") (pintype "output"))
      (node (ref "R41") (pin "1") (pinfunction "1_1") (pintype "passive"))
    )
    (net (code "23") (name "Net-(ARDUINO_DUE3-AN10)") (class "Default")
      (node (ref "ARDUINO_DUE3") (pin "A10") (pinfunction "AN10_A10") (pintype "bidirectional"))
      (node (ref "IC8") (pin "8") (pinfunction "OUT_8") (pintype "output"))
      (node (ref "R42") (pin "1") (pinfunction "1_1") (pintype "passive"))
    )
    (net (code "24") (name "Net-(ARDUINO_DUE3-AN11)") (class "Default")
      (node (ref "ARDUINO_DUE3") (pin "A11") (pinfunction "AN11_A11") (pintype "bidirectional"))
      (node (ref "IC8") (pin "14") (pinfunction "OUT_14") (pintype "output"))
      (node (ref "R43") (pin "1") (pinfunction "1_1") (pintype "passive"))
    )
    (net (code "25") (name "Net-(ARDUINO_DUE3-Pad2)") (class "Default")
      (node (ref "ARDUINO_DUE3") (pin "2") (pinfunction "2_2") (pintype "bidirectional"))
      (node (ref "J9") (pin "6") (pinfunction "6_6") (pintype "passive"))
    )
    (net (code "26") (name "Net-(ARDUINO_DUE3-Pad3)") (class "Default")
      (node (ref "ARDUINO_DUE3") (pin "3") (pinfunction "3_3") (pintype "bidirectional"))
      (node (ref "J9") (pin "5") (pinfunction "5_5") (pintype "passive"))
    )
    (net (code "27") (name "Net-(ARDUINO_DUE3-Pad4)") (class "Default")
      (node (ref "ARDUINO_DUE3") (pin "4") (pinfunction "4_4") (pintype "bidirectional"))
      (node (ref "J9") (pin "4") (pinfunction "4_4") (pintype "passive"))
    )
    (net (code "28") (name "Net-(ARDUINO_DUE3-Pad5)") (class "Default")
      (node (ref "ARDUINO_DUE3") (pin "5") (pinfunction "5_5") (pintype "bidirectional"))
      (node (ref "J9") (pin "3") (pinfunction "3_3") (pintype "passive"))
    )
    (net (code "29") (name "Net-(ARDUINO_DUE3-Pad6)") (class "Default")
      (node (ref "ARDUINO_DUE3") (pin "6") (pinfunction "6_6") (pintype "bidirectional"))
      (node (ref "J9") (pin "2") (pinfunction "2_2") (pintype "passive"))
    )
    (net (code "30") (name "Net-(ARDUINO_DUE3-Pad7)") (class "Default")
      (node (ref "ARDUINO_DUE3") (pin "7") (pinfunction "7_7") (pintype "bidirectional"))
      (node (ref "J9") (pin "1") (pinfunction "1_1") (pintype "passive"))
    )
    (net (code "31") (name "Net-(ARDUINO_DUE4-AN8)") (class "Default")
      (node (ref "ARDUINO_DUE4") (pin "A8") (pinfunction "AN8_A8") (pintype "bidirectional"))
      (node (ref "IC11") (pin "1") (pinfunction "OUT_1") (pintype "output"))
      (node (ref "R56") (pin "1") (pinfunction "1_1") (pintype "passive"))
    )
    (net (code "32") (name "Net-(ARDUINO_DUE4-AN9)") (class "Default")
      (node (ref "ARDUINO_DUE4") (pin "A9") (pinfunction "AN9_A9") (pintype "bidirectional"))
      (node (ref "IC11") (pin "7") (pinfunction "OUT_7") (pintype "output"))
      (node (ref "R57") (pin "1") (pinfunction "1_1") (pintype "passive"))
    )
    (net (code "33") (name "Net-(ARDUINO_DUE4-AN10)") (class "Default")
      (node (ref "ARDUINO_DUE4") (pin "A10") (pinfunction "AN10_A10") (pintype "bidirectional"))
      (node (ref "IC11") (pin "8") (pinfunction "OUT_8") (pintype "output"))
      (node (ref "R58") (pin "1") (pinfunction "1_1") (pintype "passive"))
    )
    (net (code "34") (name "Net-(ARDUINO_DUE4-AN11)") (class "Default")
      (node (ref "ARDUINO_DUE4") (pin "A11") (pinfunction "AN11_A11") (pintype "bidirectional"))
      (node (ref "IC11") (pin "14") (pinfunction "OUT_14") (pintype "output"))
      (node (ref "R59") (pin "1") (pinfunction "1_1") (pintype "passive"))
    )
    (net (code "35") (name "Net-(ARDUINO_DUE4-Pad2)") (class "Default")
      (node (ref "ARDUINO_DUE4") (pin "2") (pinfunction "2_2") (pintype "bidirectional"))
      (node (ref "J12") (pin "6") (pinfunction "6_6") (pintype "passive"))
    )
    (net (code "36") (name "Net-(ARDUINO_DUE4-Pad3)") (class "Default")
      (node (ref "ARDUINO_DUE4") (pin "3") (pinfunction "3_3") (pintype "bidirectional"))
      (node (ref "J12") (pin "5") (pinfunction "5_5") (pintype "passive"))
    )
    (net (code "37") (name "Net-(ARDUINO_DUE4-Pad4)") (class "Default")
      (node (ref "ARDUINO_DUE4") (pin "4") (pinfunction "4_4") (pintype "bidirectional"))
      (node (ref "J12") (pin "4") (pinfunction "4_4") (pintype "passive"))
    )
    (net (code "38") (name "Net-(ARDUINO_DUE4-Pad5)") (class "Default")
      (node (ref "ARDUINO_DUE4") (pin "5") (pinfunction "5_5") (pintype "bidirectional"))
      (node (ref "J12") (pin "3") (pinfunction "3_3") (pintype "passive"))
    )
    (net (code "39") (name "Net-(ARDUINO_DUE4-Pad6)") (class "Default")
      (node (ref "ARDUINO_DUE4") (pin "6") (pinfunction "6_6") (pintype "bidirectional"))
      (node (ref "J12") (pin "2") (pinfunction "2_2") (pintype "passive"))
    )
    (net (code "40") (name "Net-(ARDUINO_DUE4-Pad7)") (class "Default")
      (node (ref "ARDUINO_DUE4") (pin "7") (pinfunction "7_7") (pintype "bidirectional"))
      (node (ref "J12") (pin "1") (pinfunction "1_1") (pintype "passive"))
    )
    (net (code "41") (name "Net-(C1-Pad+)") (class "Default")
      (node (ref "C1") (pin "+") (pinfunction "+_+") (pintype "passive"))
      (node (ref "IC6") (pin "IN") (pinfunction "IN_IN") (pintype "input"))
      (node (ref "S1") (pin "1") (pinfunction "S_1") (pintype "passive"))
    )
    (net (code "42") (name "Net-(C3-Pad+)") (class "Default")
      (node (ref "C3") (pin "+") (pinfunction "+_+") (pintype "passive"))
      (node (ref "IC1") (pin "IN") (pinfunction "IN_IN") (pintype "input"))
      (node (ref "S2") (pin "1") (pinfunction "S_1") (pintype "passive"))
    )
    (net (code "43") (name "Net-(C5-Pad+)") (class "Default")
      (node (ref "C5") (pin "+") (pinfunction "+_+") (pintype "passive"))
      (node (ref "IC7") (pin "IN") (pinfunction "IN_IN") (pintype "input"))
      (node (ref "S3") (pin "1") (pinfunction "S_1") (pintype "passive"))
    )
    (net (code "44") (name "Net-(C7-Pad+)") (class "Default")
      (node (ref "C7") (pin "+") (pinfunction "+_+") (pintype "passive"))
      (node (ref "IC10") (pin "IN") (pinfunction "IN_IN") (pintype "input"))
      (node (ref "S4") (pin "1") (pinfunction "S_1") (pintype "passive"))
    )
    (net (code "45") (name "Net-(IC2A-+IN)") (class "Default")
      (node (ref "IC2") (pin "3") (pinfunction "+IN_3") (pintype "input"))
      (node (ref "R7") (pin "S") (pinfunction "OUT_S") (pintype "passive"))
    )
    (net (code "46") (name "Net-(IC2A--IN)") (class "Default")
      (node (ref "IC2") (pin "2") (pinfunction "-IN_2") (pintype "input"))
      (node (ref "J4") (pin "4") (pinfunction "4_4") (pintype "passive"))
    )
    (net (code "47") (name "Net-(IC2B-+IN)") (class "Default")
      (node (ref "IC2") (pin "5") (pinfunction "+IN_5") (pintype "input"))
      (node (ref "R6") (pin "S") (pinfunction "OUT_S") (pintype "passive"))
    )
    (net (code "48") (name "Net-(IC2B--IN)") (class "Default")
      (node (ref "IC2") (pin "6") (pinfunction "-IN_6") (pintype "input"))
      (node (ref "J4") (pin "3") (pinfunction "3_3") (pintype "passive"))
    )
    (net (code "49") (name "Net-(IC2C-+IN)") (class "Default")
      (node (ref "IC2") (pin "10") (pinfunction "+IN_10") (pintype "input"))
      (node (ref "R5") (pin "S") (pinfunction "OUT_S") (pintype "passive"))
    )
    (net (code "50") (name "Net-(IC2C--IN)") (class "Default")
      (node (ref "IC2") (pin "9") (pinfunction "-IN_9") (pintype "input"))
      (node (ref "J4") (pin "2") (pinfunction "2_2") (pintype "passive"))
    )
    (net (code "51") (name "Net-(IC2D-+IN)") (class "Default")
      (node (ref "IC2") (pin "12") (pinfunction "+IN_12") (pintype "input"))
      (node (ref "R4") (pin "S") (pinfunction "OUT_S") (pintype "passive"))
    )
    (net (code "52") (name "Net-(IC2D--IN)") (class "Default")
      (node (ref "IC2") (pin "13") (pinfunction "-IN_13") (pintype "input"))
      (node (ref "J4") (pin "1") (pinfunction "1_1") (pintype "passive"))
    )
    (net (code "53") (name "Net-(IC3A-+IN)") (class "Default")
      (node (ref "IC3") (pin "3") (pinfunction "+IN_3") (pintype "input"))
      (node (ref "R3") (pin "S") (pinfunction "OUT_S") (pintype "passive"))
    )
    (net (code "54") (name "Net-(IC3A--IN)") (class "Default")
      (node (ref "IC3") (pin "2") (pinfunction "-IN_2") (pintype "input"))
      (node (ref "J3") (pin "6") (pinfunction "6_6") (pintype "passive"))
    )
    (net (code "55") (name "Net-(IC3A-OUT)") (class "Default")
      (node (ref "ARDUINO_DUE1") (pin "DAC0") (pinfunction "DAC0_DAC0") (pintype "bidirectional"))
      (node (ref "IC3") (pin "1") (pinfunction "OUT_1") (pintype "output"))
      (node (ref "R12") (pin "1") (pinfunction "1_1") (pintype "passive"))
    )
    (net (code "56") (name "Net-(IC3B-+IN)") (class "Default")
      (node (ref "IC3") (pin "5") (pinfunction "+IN_5") (pintype "input"))
      (node (ref "R1") (pin "S") (pinfunction "OUT_S") (pintype "passive"))
    )
    (net (code "57") (name "Net-(IC3B--IN)") (class "Default")
      (node (ref "IC3") (pin "6") (pinfunction "-IN_6") (pintype "input"))
      (node (ref "J3") (pin "5") (pinfunction "5_5") (pintype "passive"))
    )
    (net (code "58") (name "Net-(IC3B-OUT)") (class "Default")
      (node (ref "ARDUINO_DUE1") (pin "DAC1") (pinfunction "DAC1_DAC1") (pintype "bidirectional"))
      (node (ref "IC3") (pin "7") (pinfunction "OUT_7") (pintype "output"))
      (node (ref "R13") (pin "1") (pinfunction "1_1") (pintype "passive"))
    )
    (net (code "59") (name "Net-(IC3C-+IN)") (class "Default")
      (node (ref "IC3") (pin "10") (pinfunction "+IN_10") (pintype "input"))
      (node (ref "R2") (pin "S") (pinfunction "OUT_S") (pintype "passive"))
    )
    (net (code "60") (name "Net-(IC3C--IN)") (class "Default")
      (node (ref "IC3") (pin "9") (pinfunction "-IN_9") (pintype "input"))
      (node (ref "J3") (pin "4") (pinfunction "4_4") (pintype "passive"))
    )
    (net (code "61") (name "Net-(IC3C-OUT)") (class "Default")
      (node (ref "ARDUINO_DUE1") (pin "CANRX") (pinfunction "CANRX_CANRX") (pintype "bidirectional"))
      (node (ref "IC3") (pin "8") (pinfunction "OUT_8") (pintype "output"))
      (node (ref "R14") (pin "1") (pinfunction "1_1") (pintype "passive"))
    )
    (net (code "62") (name "Net-(IC3D-+IN)") (class "Default")
      (node (ref "IC3") (pin "12") (pinfunction "+IN_12") (pintype "input"))
      (node (ref "R16") (pin "S") (pinfunction "OUT_S") (pintype "passive"))
    )
    (net (code "63") (name "Net-(IC3D--IN)") (class "Default")
      (node (ref "IC3") (pin "13") (pinfunction "-IN_13") (pintype "input"))
      (node (ref "J3") (pin "3") (pinfunction "3_3") (pintype "passive"))
    )
    (net (code "64") (name "Net-(IC3D-OUT)") (class "Default")
      (node (ref "ARDUINO_DUE1") (pin "CANTX") (pinfunction "CANTX_CANTX") (pintype "bidirectional"))
      (node (ref "IC3") (pin "14") (pinfunction "OUT_14") (pintype "output"))
      (node (ref "R15") (pin "1") (pinfunction "1_1") (pintype "passive"))
    )
    (net (code "65") (name "Net-(IC4A-+IN)") (class "Default")
      (node (ref "IC4") (pin "3") (pinfunction "+IN_3") (pintype "input"))
      (node (ref "R23") (pin "S") (pinfunction "OUT_S") (pintype "passive"))
    )
    (net (code "66") (name "Net-(IC4A--IN)") (class "Default")
      (node (ref "IC4") (pin "2") (pinfunction "-IN_2") (pintype "input"))
      (node (ref "J5") (pin "4") (pinfunction "4_4") (pintype "passive"))
    )
    (net (code "67") (name "Net-(IC4B-+IN)") (class "Default")
      (node (ref "IC4") (pin "5") (pinfunction "+IN_5") (pintype "input"))
      (node (ref "R22") (pin "S") (pinfunction "OUT_S") (pintype "passive"))
    )
    (net (code "68") (name "Net-(IC4B--IN)") (class "Default")
      (node (ref "IC4") (pin "6") (pinfunction "-IN_6") (pintype "input"))
      (node (ref "J5") (pin "3") (pinfunction "3_3") (pintype "passive"))
    )
    (net (code "69") (name "Net-(IC4C-+IN)") (class "Default")
      (node (ref "IC4") (pin "10") (pinfunction "+IN_10") (pintype "input"))
      (node (ref "R21") (pin "S") (pinfunction "OUT_S") (pintype "passive"))
    )
    (net (code "70") (name "Net-(IC4C--IN)") (class "Default")
      (node (ref "IC4") (pin "9") (pinfunction "-IN_9") (pintype "input"))
      (node (ref "J5") (pin "2") (pinfunction "2_2") (pintype "passive"))
    )
    (net (code "71") (name "Net-(IC4D-+IN)") (class "Default")
      (node (ref "IC4") (pin "12") (pinfunction "+IN_12") (pintype "input"))
      (node (ref "R20") (pin "S") (pinfunction "OUT_S") (pintype "passive"))
    )
    (net (code "72") (name "Net-(IC4D--IN)") (class "Default")
      (node (ref "IC4") (pin "13") (pinfunction "-IN_13") (pintype "input"))
      (node (ref "J5") (pin "1") (pinfunction "1_1") (pintype "passive"))
    )
    (net (code "73") (name "Net-(IC5A-+IN)") (class "Default")
      (node (ref "IC5") (pin "3") (pinfunction "+IN_3") (pintype "input"))
      (node (ref "R19") (pin "S") (pinfunction "OUT_S") (pintype "passive"))
    )
    (net (code "74") (name "Net-(IC5A--IN)") (class "Default")
      (node (ref "IC5") (pin "2") (pinfunction "-IN_2") (pintype "input"))
      (node (ref "J1") (pin "6") (pinfunction "6_6") (pintype "passive"))
    )
    (net (code "75") (name "Net-(IC5A-OUT)") (class "Default")
      (node (ref "ARDUINO_DUE2") (pin "DAC0") (pinfunction "DAC0_DAC0") (pintype "bidirectional"))
      (node (ref "IC5") (pin "1") (pinfunction "OUT_1") (pintype "output"))
      (node (ref "R28") (pin "1") (pinfunction "1_1") (pintype "passive"))
    )
    (net (code "76") (name "Net-(IC5B-+IN)") (class "Default")
      (node (ref "IC5") (pin "5") (pinfunction "+IN_5") (pintype "input"))
      (node (ref "R17") (pin "S") (pinfunction "OUT_S") (pintype "passive"))
    )
    (net (code "77") (name "Net-(IC5B--IN)") (class "Default")
      (node (ref "IC5") (pin "6") (pinfunction "-IN_6") (pintype "input"))
      (node (ref "J1") (pin "5") (pinfunction "5_5") (pintype "passive"))
    )
    (net (code "78") (name "Net-(IC5B-OUT)") (class "Default")
      (node (ref "ARDUINO_DUE2") (pin "DAC1") (pinfunction "DAC1_DAC1") (pintype "bidirectional"))
      (node (ref "IC5") (pin "7") (pinfunction "OUT_7") (pintype "output"))
      (node (ref "R29") (pin "1") (pinfunction "1_1") (pintype "passive"))
    )
    (net (code "79") (name "Net-(IC5C-+IN)") (class "Default")
      (node (ref "IC5") (pin "10") (pinfunction "+IN_10") (pintype "input"))
      (node (ref "R18") (pin "S") (pinfunction "OUT_S") (pintype "passive"))
    )
    (net (code "80") (name "Net-(IC5C--IN)") (class "Default")
      (node (ref "IC5") (pin "9") (pinfunction "-IN_9") (pintype "input"))
      (node (ref "J1") (pin "4") (pinfunction "4_4") (pintype "passive"))
    )
    (net (code "81") (name "Net-(IC5C-OUT)") (class "Default")
      (node (ref "ARDUINO_DUE2") (pin "CANRX") (pinfunction "CANRX_CANRX") (pintype "bidirectional"))
      (node (ref "IC5") (pin "8") (pinfunction "OUT_8") (pintype "output"))
      (node (ref "R30") (pin "1") (pinfunction "1_1") (pintype "passive"))
    )
    (net (code "82") (name "Net-(IC5D-+IN)") (class "Default")
      (node (ref "IC5") (pin "12") (pinfunction "+IN_12") (pintype "input"))
      (node (ref "R32") (pin "S") (pinfunction "OUT_S") (pintype "passive"))
    )
    (net (code "83") (name "Net-(IC5D--IN)") (class "Default")
      (node (ref "IC5") (pin "13") (pinfunction "-IN_13") (pintype "input"))
      (node (ref "J1") (pin "3") (pinfunction "3_3") (pintype "passive"))
    )
    (net (code "84") (name "Net-(IC5D-OUT)") (class "Default")
      (node (ref "ARDUINO_DUE2") (pin "CANTX") (pinfunction "CANTX_CANTX") (pintype "bidirectional"))
      (node (ref "IC5") (pin "14") (pinfunction "OUT_14") (pintype "output"))
      (node (ref "R31") (pin "1") (pinfunction "1_1") (pintype "passive"))
    )
    (net (code "85") (name "Net-(IC8A-+IN)") (class "Default")
      (node (ref "IC8") (pin "3") (pinfunction "+IN_3") (pintype "input"))
      (node (ref "R39") (pin "S") (pinfunction "OUT_S") (pintype "passive"))
    )
    (net (code "86") (name "Net-(IC8A--IN)") (class "Default")
      (node (ref "IC8") (pin "2") (pinfunction "-IN_2") (pintype "input"))
      (node (ref "J8") (pin "4") (pinfunction "4_4") (pintype "passive"))
    )
    (net (code "87") (name "Net-(IC8B-+IN)") (class "Default")
      (node (ref "IC8") (pin "5") (pinfunction "+IN_5") (pintype "input"))
      (node (ref "R38") (pin "S") (pinfunction "OUT_S") (pintype "passive"))
    )
    (net (code "88") (name "Net-(IC8B--IN)") (class "Default")
      (node (ref "IC8") (pin "6") (pinfunction "-IN_6") (pintype "input"))
      (node (ref "J8") (pin "3") (pinfunction "3_3") (pintype "passive"))
    )
    (net (code "89") (name "Net-(IC8C-+IN)") (class "Default")
      (node (ref "IC8") (pin "10") (pinfunction "+IN_10") (pintype "input"))
      (node (ref "R37") (pin "S") (pinfunction "OUT_S") (pintype "passive"))
    )
    (net (code "90") (name "Net-(IC8C--IN)") (class "Default")
      (node (ref "IC8") (pin "9") (pinfunction "-IN_9") (pintype "input"))
      (node (ref "J8") (pin "2") (pinfunction "2_2") (pintype "passive"))
    )
    (net (code "91") (name "Net-(IC8D-+IN)") (class "Default")
      (node (ref "IC8") (pin "12") (pinfunction "+IN_12") (pintype "input"))
      (node (ref "R36") (pin "S") (pinfunction "OUT_S") (pintype "passive"))
    )
    (net (code "92") (name "Net-(IC8D--IN)") (class "Default")
      (node (ref "IC8") (pin "13") (pinfunction "-IN_13") (pintype "input"))
      (node (ref "J8") (pin "1") (pinfunction "1_1") (pintype "passive"))
    )
    (net (code "93") (name "Net-(IC9A-+IN)") (class "Default")
      (node (ref "IC9") (pin "3") (pinfunction "+IN_3") (pintype "input"))
      (node (ref "R35") (pin "S") (pinfunction "OUT_S") (pintype "passive"))
    )
    (net (code "94") (name "Net-(IC9A--IN)") (class "Default")
      (node (ref "IC9") (pin "2") (pinfunction "-IN_2") (pintype "input"))
      (node (ref "J7") (pin "6") (pinfunction "6_6") (pintype "passive"))
    )
    (net (code "95") (name "Net-(IC9A-OUT)") (class "Default")
      (node (ref "ARDUINO_DUE3") (pin "DAC0") (pinfunction "DAC0_DAC0") (pintype "bidirectional"))
      (node (ref "IC9") (pin "1") (pinfunction "OUT_1") (pintype "output"))
      (node (ref "R44") (pin "1") (pinfunction "1_1") (pintype "passive"))
    )
    (net (code "96") (name "Net-(IC9B-+IN)") (class "Default")
      (node (ref "IC9") (pin "5") (pinfunction "+IN_5") (pintype "input"))
      (node (ref "R33") (pin "S") (pinfunction "OUT_S") (pintype "passive"))
    )
    (net (code "97") (name "Net-(IC9B--IN)") (class "Default")
      (node (ref "IC9") (pin "6") (pinfunction "-IN_6") (pintype "input"))
      (node (ref "J7") (pin "5") (pinfunction "5_5") (pintype "passive"))
    )
    (net (code "98") (name "Net-(IC9B-OUT)") (class "Default")
      (node (ref "ARDUINO_DUE3") (pin "DAC1") (pinfunction "DAC1_DAC1") (pintype "bidirectional"))
      (node (ref "IC9") (pin "7") (pinfunction "OUT_7") (pintype "output"))
      (node (ref "R45") (pin "1") (pinfunction "1_1") (pintype "passive"))
    )
    (net (code "99") (name "Net-(IC9C-+IN)") (class "Default")
      (node (ref "IC9") (pin "10") (pinfunction "+IN_10") (pintype "input"))
      (node (ref "R34") (pin "S") (pinfunction "OUT_S") (pintype "passive"))
    )
    (net (code "100") (name "Net-(IC9C--IN)") (class "Default")
      (node (ref "IC9") (pin "9") (pinfunction "-IN_9") (pintype "input"))
      (node (ref "J7") (pin "4") (pinfunction "4_4") (pintype "passive"))
    )
    (net (code "101") (name "Net-(IC9C-OUT)") (class "Default")
      (node (ref "ARDUINO_DUE3") (pin "CANRX") (pinfunction "CANRX_CANRX") (pintype "bidirectional"))
      (node (ref "IC9") (pin "8") (pinfunction "OUT_8") (pintype "output"))
      (node (ref "R46") (pin "1") (pinfunction "1_1") (pintype "passive"))
    )
    (net (code "102") (name "Net-(IC9D-+IN)") (class "Default")
      (node (ref "IC9") (pin "12") (pinfunction "+IN_12") (pintype "input"))
      (node (ref "R48") (pin "S") (pinfunction "OUT_S") (pintype "passive"))
    )
    (net (code "103") (name "Net-(IC9D--IN)") (class "Default")
      (node (ref "IC9") (pin "13") (pinfunction "-IN_13") (pintype "input"))
      (node (ref "J7") (pin "3") (pinfunction "3_3") (pintype "passive"))
    )
    (net (code "104") (name "Net-(IC9D-OUT)") (class "Default")
      (node (ref "ARDUINO_DUE3") (pin "CANTX") (pinfunction "CANTX_CANTX") (pintype "bidirectional"))
      (node (ref "IC9") (pin "14") (pinfunction "OUT_14") (pintype "output"))
      (node (ref "R47") (pin "1") (pinfunction "1_1") (pintype "passive"))
    )
    (net (code "105") (name "Net-(IC11A-+IN)") (class "Default")
      (node (ref "IC11") (pin "3") (pinfunction "+IN_3") (pintype "input"))
      (node (ref "R55") (pin "S") (pinfunction "OUT_S") (pintype "passive"))
    )
    (net (code "106") (name "Net-(IC11A--IN)") (class "Default")
      (node (ref "IC11") (pin "2") (pinfunction "-IN_2") (pintype "input"))
      (node (ref "J11") (pin "4") (pinfunction "4_4") (pintype "passive"))
    )
    (net (code "107") (name "Net-(IC11B-+IN)") (class "Default")
      (node (ref "IC11") (pin "5") (pinfunction "+IN_5") (pintype "input"))
      (node (ref "R54") (pin "S") (pinfunction "OUT_S") (pintype "passive"))
    )
    (net (code "108") (name "Net-(IC11B--IN)") (class "Default")
      (node (ref "IC11") (pin "6") (pinfunction "-IN_6") (pintype "input"))
      (node (ref "J11") (pin "3") (pinfunction "3_3") (pintype "passive"))
    )
    (net (code "109") (name "Net-(IC11C-+IN)") (class "Default")
      (node (ref "IC11") (pin "10") (pinfunction "+IN_10") (pintype "input"))
      (node (ref "R53") (pin "S") (pinfunction "OUT_S") (pintype "passive"))
    )
    (net (code "110") (name "Net-(IC11C--IN)") (class "Default")
      (node (ref "IC11") (pin "9") (pinfunction "-IN_9") (pintype "input"))
      (node (ref "J11") (pin "2") (pinfunction "2_2") (pintype "passive"))
    )
    (net (code "111") (name "Net-(IC11D-+IN)") (class "Default")
      (node (ref "IC11") (pin "12") (pinfunction "+IN_12") (pintype "input"))
      (node (ref "R52") (pin "S") (pinfunction "OUT_S") (pintype "passive"))
    )
    (net (code "112") (name "Net-(IC11D--IN)") (class "Default")
      (node (ref "IC11") (pin "13") (pinfunction "-IN_13") (pintype "input"))
      (node (ref "J11") (pin "1") (pinfunction "1_1") (pintype "passive"))
    )
    (net (code "113") (name "Net-(IC12A-+IN)") (class "Default")
      (node (ref "IC12") (pin "3") (pinfunction "+IN_3") (pintype "input"))
      (node (ref "R51") (pin "S") (pinfunction "OUT_S") (pintype "passive"))
    )
    (net (code "114") (name "Net-(IC12A--IN)") (class "Default")
      (node (ref "IC12") (pin "2") (pinfunction "-IN_2") (pintype "input"))
      (node (ref "J10") (pin "6") (pinfunction "6_6") (pintype "passive"))
    )
    (net (code "115") (name "Net-(IC12A-OUT)") (class "Default")
      (node (ref "ARDUINO_DUE4") (pin "DAC0") (pinfunction "DAC0_DAC0") (pintype "bidirectional"))
      (node (ref "IC12") (pin "1") (pinfunction "OUT_1") (pintype "output"))
      (node (ref "R60") (pin "1") (pinfunction "1_1") (pintype "passive"))
    )
    (net (code "116") (name "Net-(IC12B-+IN)") (class "Default")
      (node (ref "IC12") (pin "5") (pinfunction "+IN_5") (pintype "input"))
      (node (ref "R49") (pin "S") (pinfunction "OUT_S") (pintype "passive"))
    )
    (net (code "117") (name "Net-(IC12B--IN)") (class "Default")
      (node (ref "IC12") (pin "6") (pinfunction "-IN_6") (pintype "input"))
      (node (ref "J10") (pin "5") (pinfunction "5_5") (pintype "passive"))
    )
    (net (code "118") (name "Net-(IC12B-OUT)") (class "Default")
      (node (ref "ARDUINO_DUE4") (pin "DAC1") (pinfunction "DAC1_DAC1") (pintype "bidirectional"))
      (node (ref "IC12") (pin "7") (pinfunction "OUT_7") (pintype "output"))
      (node (ref "R61") (pin "1") (pinfunction "1_1") (pintype "passive"))
    )
    (net (code "119") (name "Net-(IC12C-+IN)") (class "Default")
      (node (ref "IC12") (pin "10") (pinfunction "+IN_10") (pintype "input"))
      (node (ref "R50") (pin "S") (pinfunction "OUT_S") (pintype "passive"))
    )
    (net (code "120") (name "Net-(IC12C--IN)") (class "Default")
      (node (ref "IC12") (pin "9") (pinfunction "-IN_9") (pintype "input"))
      (node (ref "J10") (pin "4") (pinfunction "4_4") (pintype "passive"))
    )
    (net (code "121") (name "Net-(IC12C-OUT)") (class "Default")
      (node (ref "ARDUINO_DUE4") (pin "CANRX") (pinfunction "CANRX_CANRX") (pintype "bidirectional"))
      (node (ref "IC12") (pin "8") (pinfunction "OUT_8") (pintype "output"))
      (node (ref "R62") (pin "1") (pinfunction "1_1") (pintype "passive"))
    )
    (net (code "122") (name "Net-(IC12D-+IN)") (class "Default")
      (node (ref "IC12") (pin "12") (pinfunction "+IN_12") (pintype "input"))
      (node (ref "R64") (pin "S") (pinfunction "OUT_S") (pintype "passive"))
    )
    (net (code "123") (name "Net-(IC12D--IN)") (class "Default")
      (node (ref "IC12") (pin "13") (pinfunction "-IN_13") (pintype "input"))
      (node (ref "J10") (pin "3") (pinfunction "3_3") (pintype "passive"))
    )
    (net (code "124") (name "Net-(IC12D-OUT)") (class "Default")
      (node (ref "ARDUINO_DUE4") (pin "CANTX") (pinfunction "CANTX_CANTX") (pintype "bidirectional"))
      (node (ref "IC12") (pin "14") (pinfunction "OUT_14") (pintype "output"))
      (node (ref "R63") (pin "1") (pinfunction "1_1") (pintype "passive"))
    )
    (net (code "125") (name "Net-(LED1-C)") (class "Default")
      (node (ref "C1") (pin "-") (pinfunction "-_-") (pintype "passive"))
      (node (ref "C2") (pin "-") (pinfunction "-_-") (pintype "passive"))
      (node (ref "IC6") (pin "GND") (pinfunction "GND_GND") (pintype "input"))
      (node (ref "J4") (pin "5") (pinfunction "5_5") (pintype "passive"))
      (node (ref "LED1") (pin "K") (pinfunction "C_K") (pintype "passive"))
      (node (ref "LED2") (pin "K") (pinfunction "C_K") (pintype "passive"))
      (node (ref "LED3") (pin "K") (pinfunction "C_K") (pintype "passive"))
      (node (ref "LED4") (pin "K") (pinfunction "C_K") (pintype "passive"))
      (node (ref "LED5") (pin "K") (pinfunction "C_K") (pintype "passive"))
      (node (ref "LED6") (pin "K") (pinfunction "C_K") (pintype "passive"))
      (node (ref "LED7") (pin "K") (pinfunction "C_K") (pintype "passive"))
      (node (ref "LED8") (pin "K") (pinfunction "C_K") (pintype "passive"))
      (node (ref "R1") (pin "A") (pinfunction "VDD_A") (pintype "passive"))
      (node (ref "R16") (pin "A") (pinfunction "VDD_A") (pintype "passive"))
      (node (ref "R2") (pin "A") (pinfunction "VDD_A") (pintype "passive"))
      (node (ref "R3") (pin "A") (pinfunction "VDD_A") (pintype "passive"))
      (node (ref "R4") (pin "A") (pinfunction "VDD_A") (pintype "passive"))
      (node (ref "R5") (pin "A") (pinfunction "VDD_A") (pintype "passive"))
      (node (ref "R6") (pin "A") (pinfunction "VDD_A") (pintype "passive"))
      (node (ref "R7") (pin "A") (pinfunction "VDD_A") (pintype "passive"))
      (node (ref "X1") (pin "1") (pinfunction "KL_1") (pintype "passive"))
    )
    (net (code "126") (name "Net-(LED1-PadA)") (class "Default")
      (node (ref "LED1") (pin "A") (pinfunction "A_A") (pintype "passive"))
      (node (ref "R8") (pin "2") (pinfunction "2_2") (pintype "passive"))
    )
    (net (code "127") (name "Net-(LED2-PadA)") (class "Default")
      (node (ref "LED2") (pin "A") (pinfunction "A_A") (pintype "passive"))
      (node (ref "R9") (pin "2") (pinfunction "2_2") (pintype "passive"))
    )
    (net (code "128") (name "Net-(LED3-PadA)") (class "Default")
      (node (ref "LED3") (pin "A") (pinfunction "A_A") (pintype "passive"))
      (node (ref "R10") (pin "2") (pinfunction "2_2") (pintype "passive"))
    )
    (net (code "129") (name "Net-(LED4-PadA)") (class "Default")
      (node (ref "LED4") (pin "A") (pinfunction "A_A") (pintype "passive"))
      (node (ref "R11") (pin "2") (pinfunction "2_2") (pintype "passive"))
    )
    (net (code "130") (name "Net-(LED5-PadA)") (class "Default")
      (node (ref "LED5") (pin "A") (pinfunction "A_A") (pintype "passive"))
      (node (ref "R12") (pin "2") (pinfunction "2_2") (pintype "passive"))
    )
    (net (code "131") (name "Net-(LED6-PadA)") (class "Default")
      (node (ref "LED6") (pin "A") (pinfunction "A_A") (pintype "passive"))
      (node (ref "R13") (pin "2") (pinfunction "2_2") (pintype "passive"))
    )
    (net (code "132") (name "Net-(LED7-PadA)") (class "Default")
      (node (ref "LED7") (pin "A") (pinfunction "A_A") (pintype "passive"))
      (node (ref "R14") (pin "2") (pinfunction "2_2") (pintype "passive"))
    )
    (net (code "133") (name "Net-(LED8-PadA)") (class "Default")
      (node (ref "LED8") (pin "A") (pinfunction "A_A") (pintype "passive"))
      (node (ref "R15") (pin "2") (pinfunction "2_2") (pintype "passive"))
    )
    (net (code "134") (name "Net-(LED9-PadA)") (class "Default")
      (node (ref "LED9") (pin "A") (pinfunction "A_A") (pintype "passive"))
      (node (ref "R24") (pin "2") (pinfunction "2_2") (pintype "passive"))
    )
    (net (code "135") (name "Net-(LED10-C)") (class "Default")
      (node (ref "C3") (pin "-") (pinfunction "-_-") (pintype "passive"))
      (node (ref "C4") (pin "-") (pinfunction "-_-") (pintype "passive"))
      (node (ref "IC1") (pin "GND") (pinfunction "GND_GND") (pintype "input"))
      (node (ref "J5") (pin "5") (pinfunction "5_5") (pintype "passive"))
      (node (ref "LED10") (pin "K") (pinfunction "C_K") (pintype "passive"))
      (node (ref "LED11") (pin "K") (pinfunction "C_K") (pintype "passive"))
      (node (ref "LED12") (pin "K") (pinfunction "C_K") (pintype "passive"))
      (node (ref "LED13") (pin "K") (pinfunction "C_K") (pintype "passive"))
      (node (ref "LED14") (pin "K") (pinfunction "C_K") (pintype "passive"))
      (node (ref "LED15") (pin "K") (pinfunction "C_K") (pintype "passive"))
      (node (ref "LED16") (pin "K") (pinfunction "C_K") (pintype "passive"))
      (node (ref "LED9") (pin "K") (pinfunction "C_K") (pintype "passive"))
      (node (ref "R17") (pin "A") (pinfunction "VDD_A") (pintype "passive"))
      (node (ref "R18") (pin "A") (pinfunction "VDD_A") (pintype "passive"))
      (node (ref "R19") (pin "A") (pinfunction "VDD_A") (pintype "passive"))
      (node (ref "R20") (pin "A") (pinfunction "VDD_A") (pintype "passive"))
      (node (ref "R21") (pin "A") (pinfunction "VDD_A") (pintype "passive"))
      (node (ref "R22") (pin "A") (pinfunction "VDD_A") (pintype "passive"))
      (node (ref "R23") (pin "A") (pinfunction "VDD_A") (pintype "passive"))
      (node (ref "R32") (pin "A") (pinfunction "VDD_A") (pintype "passive"))
      (node (ref "X2") (pin "1") (pinfunction "KL_1") (pintype "passive"))
    )
    (net (code "136") (name "Net-(LED10-PadA)") (class "Default")
      (node (ref "LED10") (pin "A") (pinfunction "A_A") (pintype "passive"))
      (node (ref "R26") (pin "2") (pinfunction "2_2") (pintype "passive"))
    )
    (net (code "137") (name "Net-(LED11-PadA)") (class "Default")
      (node (ref "LED11") (pin "A") (pinfunction "A_A") (pintype "passive"))
      (node (ref "R27") (pin "2") (pinfunction "2_2") (pintype "passive"))
    )
    (net (code "138") (name "Net-(LED12-PadA)") (class "Default")
      (node (ref "LED12") (pin "A") (pinfunction "A_A") (pintype "passive"))
      (node (ref "R28") (pin "2") (pinfunction "2_2") (pintype "passive"))
    )
    (net (code "139") (name "Net-(LED13-PadA)") (class "Default")
      (node (ref "LED13") (pin "A") (pinfunction "A_A") (pintype "passive"))
      (node (ref "R29") (pin "2") (pinfunction "2_2") (pintype "passive"))
    )
    (net (code "140") (name "Net-(LED14-PadA)") (class "Default")
      (node (ref "LED14") (pin "A") (pinfunction "A_A") (pintype "passive"))
      (node (ref "R30") (pin "2") (pinfunction "2_2") (pintype "passive"))
    )
    (net (code "141") (name "Net-(LED15-PadA)") (class "Default")
      (node (ref "LED15") (pin "A") (pinfunction "A_A") (pintype "passive"))
      (node (ref "R31") (pin "2") (pinfunction "2_2") (pintype "passive"))
    )
    (net (code "142") (name "Net-(LED16-PadA)") (class "Default")
      (node (ref "LED16") (pin "A") (pinfunction "A_A") (pintype "passive"))
      (node (ref "R25") (pin "2") (pinfunction "2_2") (pintype "passive"))
    )
    (net (code "143") (name "Net-(LED17-C)") (class "Default")
      (node (ref "C5") (pin "-") (pinfunction "-_-") (pintype "passive"))
      (node (ref "C6") (pin "-") (pinfunction "-_-") (pintype "passive"))
      (node (ref "IC7") (pin "GND") (pinfunction "GND_GND") (pintype "input"))
      (node (ref "J8") (pin "5") (pinfunction "5_5") (pintype "passive"))
      (node (ref "LED17") (pin "K") (pinfunction "C_K") (pintype "passive"))
      (node (ref "LED18") (pin "K") (pinfunction "C_K") (pintype "passive"))
      (node (ref "LED19") (pin "K") (pinfunction "C_K") (pintype "passive"))
      (node (ref "LED20") (pin "K") (pinfunction "C_K") (pintype "passive"))
      (node (ref "LED21") (pin "K") (pinfunction "C_K") (pintype "passive"))
      (node (ref "LED22") (pin "K") (pinfunction "C_K") (pintype "passive"))
      (node (ref "LED23") (pin "K") (pinfunction "C_K") (pintype "passive"))
      (node (ref "LED24") (pin "K") (pinfunction "C_K") (pintype "passive"))
      (node (ref "R33") (pin "A") (pinfunction "VDD_A") (pintype "passive"))
      (node (ref "R34") (pin "A") (pinfunction "VDD_A") (pintype "passive"))
      (node (ref "R35") (pin "A") (pinfunction "VDD_A") (pintype "passive"))
      (node (ref "R36") (pin "A") (pinfunction "VDD_A") (pintype "passive"))
      (node (ref "R37") (pin "A") (pinfunction "VDD_A") (pintype "passive"))
      (node (ref "R38") (pin "A") (pinfunction "VDD_A") (pintype "passive"))
      (node (ref "R39") (pin "A") (pinfunction "VDD_A") (pintype "passive"))
      (node (ref "R48") (pin "A") (pinfunction "VDD_A") (pintype "passive"))
      (node (ref "X3") (pin "1") (pinfunction "KL_1") (pintype "passive"))
    )
    (net (code "144") (name "Net-(LED17-PadA)") (class "Default")
      (node (ref "LED17") (pin "A") (pinfunction "A_A") (pintype "passive"))
      (node (ref "R40") (pin "2") (pinfunction "2_2") (pintype "passive"))
    )
    (net (code "145") (name "Net-(LED18-PadA)") (class "Default")
      (node (ref "LED18") (pin "A") (pinfunction "A_A") (pintype "passive"))
      (node (ref "R42") (pin "2") (pinfunction "2_2") (pintype "passive"))
    )
    (net (code "146") (name "Net-(LED19-PadA)") (class "Default")
      (node (ref "LED19") (pin "A") (pinfunction "A_A") (pintype "passive"))
      (node (ref "R43") (pin "2") (pinfunction "2_2") (pintype "passive"))
    )
    (net (code "147") (name "Net-(LED20-PadA)") (class "Default")
      (node (ref "LED20") (pin "A") (pinfunction "A_A") (pintype "passive"))
      (node (ref "R44") (pin "2") (pinfunction "2_2") (pintype "passive"))
    )
    (net (code "148") (name "Net-(LED21-PadA)") (class "Default")
      (node (ref "LED21") (pin "A") (pinfunction "A_A") (pintype "passive"))
      (node (ref "R45") (pin "2") (pinfunction "2_2") (pintype "passive"))
    )
    (net (code "149") (name "Net-(LED22-PadA)") (class "Default")
      (node (ref "LED22") (pin "A") (pinfunction "A_A") (pintype "passive"))
      (node (ref "R46") (pin "2") (pinfunction "2_2") (pintype "passive"))
    )
    (net (code "150") (name "Net-(LED23-PadA)") (class "Default")
      (node (ref "LED23") (pin "A") (pinfunction "A_A") (pintype "passive"))
      (node (ref "R47") (pin "2") (pinfunction "2_2") (pintype "passive"))
    )
    (net (code "151") (name "Net-(LED24-PadA)") (class "Default")
      (node (ref "LED24") (pin "A") (pinfunction "A_A") (pintype "passive"))
      (node (ref "R41") (pin "2") (pinfunction "2_2") (pintype "passive"))
    )
    (net (code "152") (name "Net-(LED25-C)") (class "Default")
      (node (ref "C7") (pin "-") (pinfunction "-_-") (pintype "passive"))
      (node (ref "C8") (pin "-") (pinfunction "-_-") (pintype "passive"))
      (node (ref "IC10") (pin "GND") (pinfunction "GND_GND") (pintype "input"))
      (node (ref "J11") (pin "5") (pinfunction "5_5") (pintype "passive"))
      (node (ref "LED25") (pin "K") (pinfunction "C_K") (pintype "passive"))
      (node (ref "LED26") (pin "K") (pinfunction "C_K") (pintype "passive"))
      (node (ref "LED27") (pin "K") (pinfunction "C_K") (pintype "passive"))
      (node (ref "LED28") (pin "K") (pinfunction "C_K") (pintype "passive"))
      (node (ref "LED29") (pin "K") (pinfunction "C_K") (pintype "passive"))
      (node (ref "LED30") (pin "K") (pinfunction "C_K") (pintype "passive"))
      (node (ref "LED31") (pin "K") (pinfunction "C_K") (pintype "passive"))
      (node (ref "LED32") (pin "K") (pinfunction "C_K") (pintype "passive"))
      (node (ref "R49") (pin "A") (pinfunction "VDD_A") (pintype "passive"))
      (node (ref "R50") (pin "A") (pinfunction "VDD_A") (pintype "passive"))
      (node (ref "R51") (pin "A") (pinfunction "VDD_A") (pintype "passive"))
      (node (ref "R52") (pin "A") (pinfunction "VDD_A") (pintype "passive"))
      (node (ref "R53") (pin "A") (pinfunction "VDD_A") (pintype "passive"))
      (node (ref "R54") (pin "A") (pinfunction "VDD_A") (pintype "passive"))
      (node (ref "R55") (pin "A") (pinfunction "VDD_A") (pintype "passive"))
      (node (ref "R64") (pin "A") (pinfunction "VDD_A") (pintype "passive"))
      (node (ref "X4") (pin "1") (pinfunction "KL_1") (pintype "passive"))
    )
    (net (code "153") (name "Net-(LED25-PadA)") (class "Default")
      (node (ref "LED25") (pin "A") (pinfunction "A_A") (pintype "passive"))
      (node (ref "R56") (pin "2") (pinfunction "2_2") (pintype "passive"))
    )
    (net (code "154") (name "Net-(LED26-PadA)") (class "Default")
      (node (ref "LED26") (pin "A") (pinfunction "A_A") (pintype "passive"))
      (node (ref "R58") (pin "2") (pinfunction "2_2") (pintype "passive"))
    )
    (net (code "155") (name "Net-(LED27-PadA)") (class "Default")
      (node (ref "LED27") (pin "A") (pinfunction "A_A") (pintype "passive"))
      (node (ref "R59") (pin "2") (pinfunction "2_2") (pintype "passive"))
    )
    (net (code "156") (name "Net-(LED28-PadA)") (class "Default")
      (node (ref "LED28") (pin "A") (pinfunction "A_A") (pintype "passive"))
      (node (ref "R60") (pin "2") (pinfunction "2_2") (pintype "passive"))
    )
    (net (code "157") (name "Net-(LED29-PadA)") (class "Default")
      (node (ref "LED29") (pin "A") (pinfunction "A_A") (pintype "passive"))
      (node (ref "R61") (pin "2") (pinfunction "2_2") (pintype "passive"))
    )
    (net (code "158") (name "Net-(LED30-PadA)") (class "Default")
      (node (ref "LED30") (pin "A") (pinfunction "A_A") (pintype "passive"))
      (node (ref "R62") (pin "2") (pinfunction "2_2") (pintype "passive"))
    )
    (net (code "159") (name "Net-(LED31-PadA)") (class "Default")
      (node (ref "LED31") (pin "A") (pinfunction "A_A") (pintype "passive"))
      (node (ref "R63") (pin "2") (pinfunction "2_2") (pintype "passive"))
    )
    (net (code "160") (name "Net-(LED32-PadA)") (class "Default")
      (node (ref "LED32") (pin "A") (pinfunction "A_A") (pintype "passive"))
      (node (ref "R57") (pin "2") (pinfunction "2_2") (pintype "passive"))
    )
    (net (code "161") (name "Net-(R1-VSS)") (class "Default")
      (node (ref "C2") (pin "+") (pinfunction "+_+") (pintype "passive"))
      (node (ref "IC6") (pin "OUT") (pinfunction "OUT_OUT") (pintype "output"))
      (node (ref "J4") (pin "6") (pinfunction "6_6") (pintype "passive"))
      (node (ref "R1") (pin "E") (pinfunction "VSS_E") (pintype "passive"))
      (node (ref "R16") (pin "E") (pinfunction "VSS_E") (pintype "passive"))
      (node (ref "R2") (pin "E") (pinfunction "VSS_E") (pintype "passive"))
      (node (ref "R3") (pin "E") (pinfunction "VSS_E") (pintype "passive"))
      (node (ref "R4") (pin "E") (pinfunction "VSS_E") (pintype "passive"))
      (node (ref "R5") (pin "E") (pinfunction "VSS_E") (pintype "passive"))
      (node (ref "R6") (pin "E") (pinfunction "VSS_E") (pintype "passive"))
      (node (ref "R7") (pin "E") (pinfunction "VSS_E") (pintype "passive"))
    )
    (net (code "162") (name "Net-(R17-VSS)") (class "Default")
      (node (ref "C4") (pin "+") (pinfunction "+_+") (pintype "passive"))
      (node (ref "IC1") (pin "OUT") (pinfunction "OUT_OUT") (pintype "output"))
      (node (ref "J5") (pin "6") (pinfunction "6_6") (pintype "passive"))
      (node (ref "R17") (pin "E") (pinfunction "VSS_E") (pintype "passive"))
      (node (ref "R18") (pin "E") (pinfunction "VSS_E") (pintype "passive"))
      (node (ref "R19") (pin "E") (pinfunction "VSS_E") (pintype "passive"))
      (node (ref "R20") (pin "E") (pinfunction "VSS_E") (pintype "passive"))
      (node (ref "R21") (pin "E") (pinfunction "VSS_E") (pintype "passive"))
      (node (ref "R22") (pin "E") (pinfunction "VSS_E") (pintype "passive"))
      (node (ref "R23") (pin "E") (pinfunction "VSS_E") (pintype "passive"))
      (node (ref "R32") (pin "E") (pinfunction "VSS_E") (pintype "passive"))
    )
    (net (code "163") (name "Net-(R33-VSS)") (class "Default")
      (node (ref "C6") (pin "+") (pinfunction "+_+") (pintype "passive"))
      (node (ref "IC7") (pin "OUT") (pinfunction "OUT_OUT") (pintype "output"))
      (node (ref "J8") (pin "6") (pinfunction "6_6") (pintype "passive"))
      (node (ref "R33") (pin "E") (pinfunction "VSS_E") (pintype "passive"))
      (node (ref "R34") (pin "E") (pinfunction "VSS_E") (pintype "passive"))
      (node (ref "R35") (pin "E") (pinfunction "VSS_E") (pintype "passive"))
      (node (ref "R36") (pin "E") (pinfunction "VSS_E") (pintype "passive"))
      (node (ref "R37") (pin "E") (pinfunction "VSS_E") (pintype "passive"))
      (node (ref "R38") (pin "E") (pinfunction "VSS_E") (pintype "passive"))
      (node (ref "R39") (pin "E") (pinfunction "VSS_E") (pintype "passive"))
      (node (ref "R48") (pin "E") (pinfunction "VSS_E") (pintype "passive"))
    )
    (net (code "164") (name "Net-(R49-VSS)") (class "Default")
      (node (ref "C8") (pin "+") (pinfunction "+_+") (pintype "passive"))
      (node (ref "IC10") (pin "OUT") (pinfunction "OUT_OUT") (pintype "output"))
      (node (ref "J11") (pin "6") (pinfunction "6_6") (pintype "passive"))
      (node (ref "R49") (pin "E") (pinfunction "VSS_E") (pintype "passive"))
      (node (ref "R50") (pin "E") (pinfunction "VSS_E") (pintype "passive"))
      (node (ref "R51") (pin "E") (pinfunction "VSS_E") (pintype "passive"))
      (node (ref "R52") (pin "E") (pinfunction "VSS_E") (pintype "passive"))
      (node (ref "R53") (pin "E") (pinfunction "VSS_E") (pintype "passive"))
      (node (ref "R54") (pin "E") (pinfunction "VSS_E") (pintype "passive"))
      (node (ref "R55") (pin "E") (pinfunction "VSS_E") (pintype "passive"))
      (node (ref "R64") (pin "E") (pinfunction "VSS_E") (pintype "passive"))
    )
    (net (code "165") (name "Net-(X1B-KL)") (class "Default")
      (node (ref "S1") (pin "2") (pinfunction "P_2") (pintype "passive"))
      (node (ref "X1") (pin "2") (pinfunction "KL_2") (pintype "passive"))
    )
    (net (code "166") (name "Net-(X2B-KL)") (class "Default")
      (node (ref "S2") (pin "2") (pinfunction "P_2") (pintype "passive"))
      (node (ref "X2") (pin "2") (pinfunction "KL_2") (pintype "passive"))
    )
    (net (code "167") (name "Net-(X3B-KL)") (class "Default")
      (node (ref "S3") (pin "2") (pinfunction "P_2") (pintype "passive"))
      (node (ref "X3") (pin "2") (pinfunction "KL_2") (pintype "passive"))
    )
    (net (code "168") (name "Net-(X4B-KL)") (class "Default")
      (node (ref "S4") (pin "2") (pinfunction "P_2") (pintype "passive"))
      (node (ref "X4") (pin "2") (pinfunction "KL_2") (pintype "passive"))
    )
    (net (code "169") (name "unconnected-(ARDUINO_DUE1-5V-Pad5V0)") (class "Default")
      (node (ref "ARDUINO_DUE1") (pin "5V0") (pinfunction "5V_5V0") (pintype "bidirectional"))
    )
    (net (code "170") (name "unconnected-(ARDUINO_DUE1-5V-Pad5V0_1)") (class "Default")
      (node (ref "ARDUINO_DUE1") (pin "5V0_1") (pinfunction "5V_5V0_1") (pintype "bidirectional"))
    )
    (net (code "171") (name "unconnected-(ARDUINO_DUE1-5V-Pad5V0_2)") (class "Default")
      (node (ref "ARDUINO_DUE1") (pin "5V0_2") (pinfunction "5V_5V0_2") (pintype "bidirectional"))
    )
    (net (code "172") (name "unconnected-(ARDUINO_DUE1-5V_SPI-Pad5V_2)") (class "Default")
      (node (ref "ARDUINO_DUE1") (pin "5V_2") (pinfunction "5V_SPI_5V_2") (pintype "bidirectional"))
    )
    (net (code "173") (name "unconnected-(ARDUINO_DUE1-AN0-PadA0)") (class "Default")
      (node (ref "ARDUINO_DUE1") (pin "A0") (pinfunction "AN0_A0") (pintype "bidirectional"))
    )
    (net (code "174") (name "unconnected-(ARDUINO_DUE1-AN1-PadA1)") (class "Default")
      (node (ref "ARDUINO_DUE1") (pin "A1") (pinfunction "AN1_A1") (pintype "bidirectional"))
    )
    (net (code "175") (name "unconnected-(ARDUINO_DUE1-AN2-PadA2)") (class "Default")
      (node (ref "ARDUINO_DUE1") (pin "A2") (pinfunction "AN2_A2") (pintype "bidirectional"))
    )
    (net (code "176") (name "unconnected-(ARDUINO_DUE1-AN3-PadA3)") (class "Default")
      (node (ref "ARDUINO_DUE1") (pin "A3") (pinfunction "AN3_A3") (pintype "bidirectional"))
    )
    (net (code "177") (name "unconnected-(ARDUINO_DUE1-AN4-PadA4)") (class "Default")
      (node (ref "ARDUINO_DUE1") (pin "A4") (pinfunction "AN4_A4") (pintype "bidirectional"))
    )
    (net (code "178") (name "unconnected-(ARDUINO_DUE1-AN5-PadA5)") (class "Default")
      (node (ref "ARDUINO_DUE1") (pin "A5") (pinfunction "AN5_A5") (pintype "bidirectional"))
    )
    (net (code "179") (name "unconnected-(ARDUINO_DUE1-AN6-PadA6)") (class "Default")
      (node (ref "ARDUINO_DUE1") (pin "A6") (pinfunction "AN6_A6") (pintype "bidirectional"))
    )
    (net (code "180") (name "unconnected-(ARDUINO_DUE1-AN7-PadA7)") (class "Default")
      (node (ref "ARDUINO_DUE1") (pin "A7") (pinfunction "AN7_A7") (pintype "bidirectional"))
    )
    (net (code "181") (name "unconnected-(ARDUINO_DUE1-GND-PadGND_1)") (class "Default")
      (node (ref "ARDUINO_DUE1") (pin "GND_1") (pinfunction "GND_GND_1") (pintype "bidirectional"))
    )
    (net (code "182") (name "unconnected-(ARDUINO_DUE1-GND-PadGND_2)") (class "Default")
      (node (ref "ARDUINO_DUE1") (pin "GND_2") (pinfunction "GND_GND_2") (pintype "bidirectional"))
    )
    (net (code "183") (name "unconnected-(ARDUINO_DUE1-GND-PadGND_3)") (class "Default")
      (node (ref "ARDUINO_DUE1") (pin "GND_3") (pinfunction "GND_GND_3") (pintype "bidirectional"))
    )
    (net (code "184") (name "unconnected-(ARDUINO_DUE1-GND-PadGND_4)") (class "Default")
      (node (ref "ARDUINO_DUE1") (pin "GND_4") (pinfunction "GND_GND_4") (pintype "bidirectional"))
    )
    (net (code "185") (name "unconnected-(ARDUINO_DUE1-GND-PadGND_5)") (class "Default")
      (node (ref "ARDUINO_DUE1") (pin "GND_5") (pinfunction "GND_GND_5") (pintype "bidirectional"))
    )
    (net (code "186") (name "unconnected-(ARDUINO_DUE1-GND-PadGND_7)") (class "Default")
      (node (ref "ARDUINO_DUE1") (pin "GND_7") (pinfunction "GND_GND_7") (pintype "bidirectional"))
    )
    (net (code "187") (name "unconnected-(ARDUINO_DUE1-GND-PadGND_8)") (class "Default")
      (node (ref "ARDUINO_DUE1") (pin "GND_8") (pinfunction "GND_GND_8") (pintype "bidirectional"))
    )
    (net (code "188") (name "unconnected-(ARDUINO_DUE1-GND-PadGND_9)") (class "Default")
      (node (ref "ARDUINO_DUE1") (pin "GND_9") (pinfunction "GND_GND_9") (pintype "bidirectional"))
    )
    (net (code "189") (name "unconnected-(ARDUINO_DUE1-GND-PadGND_10)") (class "Default")
      (node (ref "ARDUINO_DUE1") (pin "GND_10") (pinfunction "GND_GND_10") (pintype "bidirectional"))
    )
    (net (code "190") (name "unconnected-(ARDUINO_DUE1-MASTER_R_JTAG-PadMASTER_RESET_JTAG)") (class "Default")
      (node (ref "ARDUINO_DUE1") (pin "MASTER_RESET_JTAG") (pinfunction "MASTER_R_JTAG_MASTER_RESET_JTAG") (pintype "bidirectional"))
    )
    (net (code "191") (name "unconnected-(ARDUINO_DUE1-MASTER_R_SPI-PadMASTER_RESET_SPI)") (class "Default")
      (node (ref "ARDUINO_DUE1") (pin "MASTER_RESET_SPI") (pinfunction "MASTER_R_SPI_MASTER_RESET_SPI") (pintype "bidirectional"))
    )
    (net (code "192") (name "unconnected-(ARDUINO_DUE1-NC-PadNC_2)") (class "Default")
      (node (ref "ARDUINO_DUE1") (pin "NC_2") (pinfunction "NC_NC_2") (pintype "no_connect"))
    )
    (net (code "193") (name "unconnected-(ARDUINO_DUE1-NC-PadNC_5)") (class "Default")
      (node (ref "ARDUINO_DUE1") (pin "NC_5") (pinfunction "NC_NC_5") (pintype "bidirectional"))
    )
    (net (code "194") (name "unconnected-(ARDUINO_DUE1-Pad3V3)") (class "Default")
      (node (ref "ARDUINO_DUE1") (pin "3V3") (pinfunction "3V3_3V3") (pintype "bidirectional"))
    )
    (net (code "195") (name "unconnected-(ARDUINO_DUE1-Pad3V3_JTAG)") (class "Default")
      (node (ref "ARDUINO_DUE1") (pin "3V3_JTAG") (pinfunction "3V3_JTAG_3V3_JTAG") (pintype "bidirectional"))
    )
    (net (code "196") (name "unconnected-(ARDUINO_DUE1-Pad5V_ICSP1)") (class "Default")
      (node (ref "ARDUINO_DUE1") (pin "5V_ICSP1") (pinfunction "5V_ICSP1_5V_ICSP1") (pintype "bidirectional"))
    )
    (net (code "197") (name "unconnected-(ARDUINO_DUE1-Pad8)") (class "Default")
      (node (ref "ARDUINO_DUE1") (pin "8") (pinfunction "8_8") (pintype "bidirectional"))
    )
    (net (code "198") (name "unconnected-(ARDUINO_DUE1-Pad9)") (class "Default")
      (node (ref "ARDUINO_DUE1") (pin "9") (pinfunction "9_9") (pintype "bidirectional"))
    )
    (net (code "199") (name "unconnected-(ARDUINO_DUE1-Pad10)") (class "Default")
      (node (ref "ARDUINO_DUE1") (pin "10") (pinfunction "10_10") (pintype "bidirectional"))
    )
    (net (code "200") (name "unconnected-(ARDUINO_DUE1-Pad11)") (class "Default")
      (node (ref "ARDUINO_DUE1") (pin "11") (pinfunction "11_11") (pintype "bidirectional"))
    )
    (net (code "201") (name "unconnected-(ARDUINO_DUE1-Pad12)") (class "Default")
      (node (ref "ARDUINO_DUE1") (pin "12") (pinfunction "12_12") (pintype "bidirectional"))
    )
    (net (code "202") (name "unconnected-(ARDUINO_DUE1-Pad13)") (class "Default")
      (node (ref "ARDUINO_DUE1") (pin "13") (pinfunction "13_13") (pintype "bidirectional"))
    )
    (net (code "203") (name "unconnected-(ARDUINO_DUE1-Pad22)") (class "Default")
      (node (ref "ARDUINO_DUE1") (pin "22") (pinfunction "22_22") (pintype "bidirectional"))
    )
    (net (code "204") (name "unconnected-(ARDUINO_DUE1-Pad23)") (class "Default")
      (node (ref "ARDUINO_DUE1") (pin "23") (pinfunction "23_23") (pintype "bidirectional"))
    )
    (net (code "205") (name "unconnected-(ARDUINO_DUE1-Pad24)") (class "Default")
      (node (ref "ARDUINO_DUE1") (pin "24") (pinfunction "24_24") (pintype "bidirectional"))
    )
    (net (code "206") (name "unconnected-(ARDUINO_DUE1-Pad25)") (class "Default")
      (node (ref "ARDUINO_DUE1") (pin "25") (pinfunction "25_25") (pintype "bidirectional"))
    )
    (net (code "207") (name "unconnected-(ARDUINO_DUE1-Pad26)") (class "Default")
      (node (ref "ARDUINO_DUE1") (pin "26") (pinfunction "26_26") (pintype "bidirectional"))
    )
    (net (code "208") (name "unconnected-(ARDUINO_DUE1-Pad27)") (class "Default")
      (node (ref "ARDUINO_DUE1") (pin "27") (pinfunction "27_27") (pintype "bidirectional"))
    )
    (net (code "209") (name "unconnected-(ARDUINO_DUE1-Pad28)") (class "Default")
      (node (ref "ARDUINO_DUE1") (pin "28") (pinfunction "28_28") (pintype "bidirectional"))
    )
    (net (code "210") (name "unconnected-(ARDUINO_DUE1-Pad29)") (class "Default")
      (node (ref "ARDUINO_DUE1") (pin "29") (pinfunction "29_29") (pintype "bidirectional"))
    )
    (net (code "211") (name "unconnected-(ARDUINO_DUE1-Pad30)") (class "Default")
      (node (ref "ARDUINO_DUE1") (pin "30") (pinfunction "30_30") (pintype "bidirectional"))
    )
    (net (code "212") (name "unconnected-(ARDUINO_DUE1-Pad31)") (class "Default")
      (node (ref "ARDUINO_DUE1") (pin "31") (pinfunction "31_31") (pintype "bidirectional"))
    )
    (net (code "213") (name "unconnected-(ARDUINO_DUE1-Pad32)") (class "Default")
      (node (ref "ARDUINO_DUE1") (pin "32") (pinfunction "32_32") (pintype "bidirectional"))
    )
    (net (code "214") (name "unconnected-(ARDUINO_DUE1-Pad33)") (class "Default")
      (node (ref "ARDUINO_DUE1") (pin "33") (pinfunction "33_33") (pintype "bidirectional"))
    )
    (net (code "215") (name "unconnected-(ARDUINO_DUE1-Pad34)") (class "Default")
      (node (ref "ARDUINO_DUE1") (pin "34") (pinfunction "34_34") (pintype "bidirectional"))
    )
    (net (code "216") (name "unconnected-(ARDUINO_DUE1-Pad35)") (class "Default")
      (node (ref "ARDUINO_DUE1") (pin "35") (pinfunction "35_35") (pintype "bidirectional"))
    )
    (net (code "217") (name "unconnected-(ARDUINO_DUE1-Pad36)") (class "Default")
      (node (ref "ARDUINO_DUE1") (pin "36") (pinfunction "36_36") (pintype "bidirectional"))
    )
    (net (code "218") (name "unconnected-(ARDUINO_DUE1-Pad37)") (class "Default")
      (node (ref "ARDUINO_DUE1") (pin "37") (pinfunction "37_37") (pintype "bidirectional"))
    )
    (net (code "219") (name "unconnected-(ARDUINO_DUE1-Pad38)") (class "Default")
      (node (ref "ARDUINO_DUE1") (pin "38") (pinfunction "38_38") (pintype "bidirectional"))
    )
    (net (code "220") (name "unconnected-(ARDUINO_DUE1-Pad39)") (class "Default")
      (node (ref "ARDUINO_DUE1") (pin "39") (pinfunction "39_39") (pintype "bidirectional"))
    )
    (net (code "221") (name "unconnected-(ARDUINO_DUE1-Pad40)") (class "Default")
      (node (ref "ARDUINO_DUE1") (pin "40") (pinfunction "40_40") (pintype "bidirectional"))
    )
    (net (code "222") (name "unconnected-(ARDUINO_DUE1-Pad41)") (class "Default")
      (node (ref "ARDUINO_DUE1") (pin "41") (pinfunction "41_41") (pintype "bidirectional"))
    )
    (net (code "223") (name "unconnected-(ARDUINO_DUE1-Pad42)") (class "Default")
      (node (ref "ARDUINO_DUE1") (pin "42") (pinfunction "42_42") (pintype "bidirectional"))
    )
    (net (code "224") (name "unconnected-(ARDUINO_DUE1-Pad43)") (class "Default")
      (node (ref "ARDUINO_DUE1") (pin "43") (pinfunction "43_43") (pintype "bidirectional"))
    )
    (net (code "225") (name "unconnected-(ARDUINO_DUE1-Pad44)") (class "Default")
      (node (ref "ARDUINO_DUE1") (pin "44") (pinfunction "44_44") (pintype "bidirectional"))
    )
    (net (code "226") (name "unconnected-(ARDUINO_DUE1-Pad45)") (class "Default")
      (node (ref "ARDUINO_DUE1") (pin "45") (pinfunction "45_45") (pintype "bidirectional"))
    )
    (net (code "227") (name "unconnected-(ARDUINO_DUE1-Pad46)") (class "Default")
      (node (ref "ARDUINO_DUE1") (pin "46") (pinfunction "46_46") (pintype "bidirectional"))
    )
    (net (code "228") (name "unconnected-(ARDUINO_DUE1-Pad47)") (class "Default")
      (node (ref "ARDUINO_DUE1") (pin "47") (pinfunction "47_47") (pintype "bidirectional"))
    )
    (net (code "229") (name "unconnected-(ARDUINO_DUE1-Pad48)") (class "Default")
      (node (ref "ARDUINO_DUE1") (pin "48") (pinfunction "48_48") (pintype "bidirectional"))
    )
    (net (code "230") (name "unconnected-(ARDUINO_DUE1-Pad49)") (class "Default")
      (node (ref "ARDUINO_DUE1") (pin "49") (pinfunction "49_49") (pintype "bidirectional"))
    )
    (net (code "231") (name "unconnected-(ARDUINO_DUE1-Pad50)") (class "Default")
      (node (ref "ARDUINO_DUE1") (pin "50") (pinfunction "50_50") (pintype "bidirectional"))
    )
    (net (code "232") (name "unconnected-(ARDUINO_DUE1-Pad51)") (class "Default")
      (node (ref "ARDUINO_DUE1") (pin "51") (pinfunction "51_51") (pintype "bidirectional"))
    )
    (net (code "233") (name "unconnected-(ARDUINO_DUE1-Pad52)") (class "Default")
      (node (ref "ARDUINO_DUE1") (pin "52") (pinfunction "52_52") (pintype "bidirectional"))
    )
    (net (code "234") (name "unconnected-(ARDUINO_DUE1-Pad53)") (class "Default")
      (node (ref "ARDUINO_DUE1") (pin "53") (pinfunction "53_53") (pintype "bidirectional"))
    )
    (net (code "235") (name "unconnected-(ARDUINO_DUE1-PadAREF)") (class "Default")
      (node (ref "ARDUINO_DUE1") (pin "AREF") (pinfunction "AREF_AREF") (pintype "bidirectional"))
    )
    (net (code "236") (name "unconnected-(ARDUINO_DUE1-PadGND)") (class "Default")
      (node (ref "ARDUINO_DUE1") (pin "GND") (pinfunction "GND_GND") (pintype "bidirectional"))
    )
    (net (code "237") (name "unconnected-(ARDUINO_DUE1-PadGND_ICSP1)") (class "Default")
      (node (ref "ARDUINO_DUE1") (pin "GND_ICSP1") (pinfunction "GND_ICSP1_GND_ICSP1") (pintype "bidirectional"))
    )
    (net (code "238") (name "unconnected-(ARDUINO_DUE1-PadIOREF)") (class "Default")
      (node (ref "ARDUINO_DUE1") (pin "IOREF") (pinfunction "IOREF_IOREF") (pintype "bidirectional"))
    )
    (net (code "239") (name "unconnected-(ARDUINO_DUE1-PadJTAG_RESET)") (class "Default")
      (node (ref "ARDUINO_DUE1") (pin "JTAG_RESET") (pinfunction "JTAG_RESET_JTAG_RESET") (pintype "bidirectional"))
    )
    (net (code "240") (name "unconnected-(ARDUINO_DUE1-PadJTAG_TCK)") (class "Default")
      (node (ref "ARDUINO_DUE1") (pin "JTAG_TCK") (pinfunction "JTAG_TCK_JTAG_TCK") (pintype "bidirectional"))
    )
    (net (code "241") (name "unconnected-(ARDUINO_DUE1-PadJTAG_TCK_2)") (class "Default")
      (node (ref "ARDUINO_DUE1") (pin "JTAG_TCK_2") (pinfunction "JTAG_TCK_2_JTAG_TCK_2") (pintype "bidirectional"))
    )
    (net (code "242") (name "unconnected-(ARDUINO_DUE1-PadJTAG_TDI)") (class "Default")
      (node (ref "ARDUINO_DUE1") (pin "JTAG_TDI") (pinfunction "JTAG_TDI_JTAG_TDI") (pintype "bidirectional"))
    )
    (net (code "243") (name "unconnected-(ARDUINO_DUE1-PadJTAG_TDO)") (class "Default")
      (node (ref "ARDUINO_DUE1") (pin "JTAG_TDO") (pinfunction "JTAG_TDO_JTAG_TDO") (pintype "bidirectional"))
    )
    (net (code "244") (name "unconnected-(ARDUINO_DUE1-PadJTAG_TMS)") (class "Default")
      (node (ref "ARDUINO_DUE1") (pin "JTAG_TMS") (pinfunction "JTAG_TMS_JTAG_TMS") (pintype "bidirectional"))
    )
    (net (code "245") (name "unconnected-(ARDUINO_DUE1-PadJTAG_TMS_2)") (class "Default")
      (node (ref "ARDUINO_DUE1") (pin "JTAG_TMS_2") (pinfunction "JTAG_TMS_2_JTAG_TMS_2") (pintype "bidirectional"))
    )
    (net (code "246") (name "unconnected-(ARDUINO_DUE1-PadMISO)") (class "Default")
      (node (ref "ARDUINO_DUE1") (pin "MISO") (pinfunction "MISO_MISO") (pintype "bidirectional"))
    )
    (net (code "247") (name "unconnected-(ARDUINO_DUE1-PadMISO2)") (class "Default")
      (node (ref "ARDUINO_DUE1") (pin "MISO2") (pinfunction "MISO2_MISO2") (pintype "bidirectional"))
    )
    (net (code "248") (name "unconnected-(ARDUINO_DUE1-PadMOSI)") (class "Default")
      (node (ref "ARDUINO_DUE1") (pin "MOSI") (pinfunction "MOSI_MOSI") (pintype "bidirectional"))
    )
    (net (code "249") (name "unconnected-(ARDUINO_DUE1-PadMOSI2)") (class "Default")
      (node (ref "ARDUINO_DUE1") (pin "MOSI2") (pinfunction "MOSI2_MOSI2") (pintype "bidirectional"))
    )
    (net (code "250") (name "unconnected-(ARDUINO_DUE1-PadRESET)") (class "Default")
      (node (ref "ARDUINO_DUE1") (pin "RESET") (pinfunction "RESET_RESET") (pintype "bidirectional"))
    )
    (net (code "251") (name "unconnected-(ARDUINO_DUE1-PadRESET2)") (class "Default")
      (node (ref "ARDUINO_DUE1") (pin "RESET2") (pinfunction "RESET2_RESET2") (pintype "bidirectional"))
    )
    (net (code "252") (name "unconnected-(ARDUINO_DUE1-PadSCK2)") (class "Default")
      (node (ref "ARDUINO_DUE1") (pin "SCK2") (pinfunction "SCK2_SCK2") (pintype "bidirectional"))
    )
    (net (code "253") (name "unconnected-(ARDUINO_DUE1-PadSCL1)") (class "Default")
      (node (ref "ARDUINO_DUE1") (pin "SCL1") (pinfunction "SCL1_SCL1") (pintype "bidirectional"))
    )
    (net (code "254") (name "unconnected-(ARDUINO_DUE1-PadSDA1)") (class "Default")
      (node (ref "ARDUINO_DUE1") (pin "SDA1") (pinfunction "SDA1_SDA1") (pintype "bidirectional"))
    )
    (net (code "255") (name "unconnected-(ARDUINO_DUE1-PadSPCK)") (class "Default")
      (node (ref "ARDUINO_DUE1") (pin "SPCK") (pinfunction "SPCK_SPCK") (pintype "bidirectional"))
    )
    (net (code "256") (name "unconnected-(ARDUINO_DUE1-PadVIN)") (class "Default")
      (node (ref "ARDUINO_DUE1") (pin "VIN") (pinfunction "VIN_VIN") (pintype "bidirectional"))
    )
    (net (code "257") (name "unconnected-(ARDUINO_DUE1-RX0<0-Pad0)") (class "Default")
      (node (ref "ARDUINO_DUE1") (pin "0") (pinfunction "RX0<0_0") (pintype "bidirectional"))
    )
    (net (code "258") (name "unconnected-(ARDUINO_DUE1-RX1_19-Pad19)") (class "Default")
      (node (ref "ARDUINO_DUE1") (pin "19") (pinfunction "RX1_19_19") (pintype "bidirectional"))
    )
    (net (code "259") (name "unconnected-(ARDUINO_DUE1-RX2_17-Pad17)") (class "Default")
      (node (ref "ARDUINO_DUE1") (pin "17") (pinfunction "RX2_17_17") (pintype "bidirectional"))
    )
    (net (code "260") (name "unconnected-(ARDUINO_DUE1-RX3_15-Pad15)") (class "Default")
      (node (ref "ARDUINO_DUE1") (pin "15") (pinfunction "RX3_15_15") (pintype "bidirectional"))
    )
    (net (code "261") (name "unconnected-(ARDUINO_DUE1-SCL_21-Pad21)") (class "Default")
      (node (ref "ARDUINO_DUE1") (pin "21") (pinfunction "SCL_21_21") (pintype "bidirectional"))
    )
    (net (code "262") (name "unconnected-(ARDUINO_DUE1-SDA_20-Pad20)") (class "Default")
      (node (ref "ARDUINO_DUE1") (pin "20") (pinfunction "SDA_20_20") (pintype "bidirectional"))
    )
    (net (code "263") (name "unconnected-(ARDUINO_DUE1-TX0>1-Pad1)") (class "Default")
      (node (ref "ARDUINO_DUE1") (pin "1") (pinfunction "TX0>1_1") (pintype "bidirectional"))
    )
    (net (code "264") (name "unconnected-(ARDUINO_DUE1-TX1_18-Pad18)") (class "Default")
      (node (ref "ARDUINO_DUE1") (pin "18") (pinfunction "TX1_18_18") (pintype "bidirectional"))
    )
    (net (code "265") (name "unconnected-(ARDUINO_DUE1-TX2_16-Pad16)") (class "Default")
      (node (ref "ARDUINO_DUE1") (pin "16") (pinfunction "TX2_16_16") (pintype "bidirectional"))
    )
    (net (code "266") (name "unconnected-(ARDUINO_DUE1-TX3_14-Pad14)") (class "Default")
      (node (ref "ARDUINO_DUE1") (pin "14") (pinfunction "TX3_14_14") (pintype "bidirectional"))
    )
    (net (code "267") (name "unconnected-(ARDUINO_DUE2-5V-Pad5V0)") (class "Default")
      (node (ref "ARDUINO_DUE2") (pin "5V0") (pinfunction "5V_5V0") (pintype "bidirectional"))
    )
    (net (code "268") (name "unconnected-(ARDUINO_DUE2-5V-Pad5V0_1)") (class "Default")
      (node (ref "ARDUINO_DUE2") (pin "5V0_1") (pinfunction "5V_5V0_1") (pintype "bidirectional"))
    )
    (net (code "269") (name "unconnected-(ARDUINO_DUE2-5V-Pad5V0_2)") (class "Default")
      (node (ref "ARDUINO_DUE2") (pin "5V0_2") (pinfunction "5V_5V0_2") (pintype "bidirectional"))
    )
    (net (code "270") (name "unconnected-(ARDUINO_DUE2-5V_SPI-Pad5V_2)") (class "Default")
      (node (ref "ARDUINO_DUE2") (pin "5V_2") (pinfunction "5V_SPI_5V_2") (pintype "bidirectional"))
    )
    (net (code "271") (name "unconnected-(ARDUINO_DUE2-AN0-PadA0)") (class "Default")
      (node (ref "ARDUINO_DUE2") (pin "A0") (pinfunction "AN0_A0") (pintype "bidirectional"))
    )
    (net (code "272") (name "unconnected-(ARDUINO_DUE2-AN1-PadA1)") (class "Default")
      (node (ref "ARDUINO_DUE2") (pin "A1") (pinfunction "AN1_A1") (pintype "bidirectional"))
    )
    (net (code "273") (name "unconnected-(ARDUINO_DUE2-AN2-PadA2)") (class "Default")
      (node (ref "ARDUINO_DUE2") (pin "A2") (pinfunction "AN2_A2") (pintype "bidirectional"))
    )
    (net (code "274") (name "unconnected-(ARDUINO_DUE2-AN3-PadA3)") (class "Default")
      (node (ref "ARDUINO_DUE2") (pin "A3") (pinfunction "AN3_A3") (pintype "bidirectional"))
    )
    (net (code "275") (name "unconnected-(ARDUINO_DUE2-AN4-PadA4)") (class "Default")
      (node (ref "ARDUINO_DUE2") (pin "A4") (pinfunction "AN4_A4") (pintype "bidirectional"))
    )
    (net (code "276") (name "unconnected-(ARDUINO_DUE2-AN5-PadA5)") (class "Default")
      (node (ref "ARDUINO_DUE2") (pin "A5") (pinfunction "AN5_A5") (pintype "bidirectional"))
    )
    (net (code "277") (name "unconnected-(ARDUINO_DUE2-AN6-PadA6)") (class "Default")
      (node (ref "ARDUINO_DUE2") (pin "A6") (pinfunction "AN6_A6") (pintype "bidirectional"))
    )
    (net (code "278") (name "unconnected-(ARDUINO_DUE2-AN7-PadA7)") (class "Default")
      (node (ref "ARDUINO_DUE2") (pin "A7") (pinfunction "AN7_A7") (pintype "bidirectional"))
    )
    (net (code "279") (name "unconnected-(ARDUINO_DUE2-GND-PadGND_1)") (class "Default")
      (node (ref "ARDUINO_DUE2") (pin "GND_1") (pinfunction "GND_GND_1") (pintype "bidirectional"))
    )
    (net (code "280") (name "unconnected-(ARDUINO_DUE2-GND-PadGND_2)") (class "Default")
      (node (ref "ARDUINO_DUE2") (pin "GND_2") (pinfunction "GND_GND_2") (pintype "bidirectional"))
    )
    (net (code "281") (name "unconnected-(ARDUINO_DUE2-GND-PadGND_3)") (class "Default")
      (node (ref "ARDUINO_DUE2") (pin "GND_3") (pinfunction "GND_GND_3") (pintype "bidirectional"))
    )
    (net (code "282") (name "unconnected-(ARDUINO_DUE2-GND-PadGND_4)") (class "Default")
      (node (ref "ARDUINO_DUE2") (pin "GND_4") (pinfunction "GND_GND_4") (pintype "bidirectional"))
    )
    (net (code "283") (name "unconnected-(ARDUINO_DUE2-GND-PadGND_5)") (class "Default")
      (node (ref "ARDUINO_DUE2") (pin "GND_5") (pinfunction "GND_GND_5") (pintype "bidirectional"))
    )
    (net (code "284") (name "unconnected-(ARDUINO_DUE2-GND-PadGND_7)") (class "Default")
      (node (ref "ARDUINO_DUE2") (pin "GND_7") (pinfunction "GND_GND_7") (pintype "bidirectional"))
    )
    (net (code "285") (name "unconnected-(ARDUINO_DUE2-GND-PadGND_8)") (class "Default")
      (node (ref "ARDUINO_DUE2") (pin "GND_8") (pinfunction "GND_GND_8") (pintype "bidirectional"))
    )
    (net (code "286") (name "unconnected-(ARDUINO_DUE2-GND-PadGND_9)") (class "Default")
      (node (ref "ARDUINO_DUE2") (pin "GND_9") (pinfunction "GND_GND_9") (pintype "bidirectional"))
    )
    (net (code "287") (name "unconnected-(ARDUINO_DUE2-GND-PadGND_10)") (class "Default")
      (node (ref "ARDUINO_DUE2") (pin "GND_10") (pinfunction "GND_GND_10") (pintype "bidirectional"))
    )
    (net (code "288") (name "unconnected-(ARDUINO_DUE2-MASTER_R_JTAG-PadMASTER_RESET_JTAG)") (class "Default")
      (node (ref "ARDUINO_DUE2") (pin "MASTER_RESET_JTAG") (pinfunction "MASTER_R_JTAG_MASTER_RESET_JTAG") (pintype "bidirectional"))
    )
    (net (code "289") (name "unconnected-(ARDUINO_DUE2-MASTER_R_SPI-PadMASTER_RESET_SPI)") (class "Default")
      (node (ref "ARDUINO_DUE2") (pin "MASTER_RESET_SPI") (pinfunction "MASTER_R_SPI_MASTER_RESET_SPI") (pintype "bidirectional"))
    )
    (net (code "290") (name "unconnected-(ARDUINO_DUE2-NC-PadNC_2)") (class "Default")
      (node (ref "ARDUINO_DUE2") (pin "NC_2") (pinfunction "NC_NC_2") (pintype "no_connect"))
    )
    (net (code "291") (name "unconnected-(ARDUINO_DUE2-NC-PadNC_5)") (class "Default")
      (node (ref "ARDUINO_DUE2") (pin "NC_5") (pinfunction "NC_NC_5") (pintype "bidirectional"))
    )
    (net (code "292") (name "unconnected-(ARDUINO_DUE2-Pad3V3)") (class "Default")
      (node (ref "ARDUINO_DUE2") (pin "3V3") (pinfunction "3V3_3V3") (pintype "bidirectional"))
    )
    (net (code "293") (name "unconnected-(ARDUINO_DUE2-Pad3V3_JTAG)") (class "Default")
      (node (ref "ARDUINO_DUE2") (pin "3V3_JTAG") (pinfunction "3V3_JTAG_3V3_JTAG") (pintype "bidirectional"))
    )
    (net (code "294") (name "unconnected-(ARDUINO_DUE2-Pad5V_ICSP1)") (class "Default")
      (node (ref "ARDUINO_DUE2") (pin "5V_ICSP1") (pinfunction "5V_ICSP1_5V_ICSP1") (pintype "bidirectional"))
    )
    (net (code "295") (name "unconnected-(ARDUINO_DUE2-Pad8)") (class "Default")
      (node (ref "ARDUINO_DUE2") (pin "8") (pinfunction "8_8") (pintype "bidirectional"))
    )
    (net (code "296") (name "unconnected-(ARDUINO_DUE2-Pad9)") (class "Default")
      (node (ref "ARDUINO_DUE2") (pin "9") (pinfunction "9_9") (pintype "bidirectional"))
    )
    (net (code "297") (name "unconnected-(ARDUINO_DUE2-Pad10)") (class "Default")
      (node (ref "ARDUINO_DUE2") (pin "10") (pinfunction "10_10") (pintype "bidirectional"))
    )
    (net (code "298") (name "unconnected-(ARDUINO_DUE2-Pad11)") (class "Default")
      (node (ref "ARDUINO_DUE2") (pin "11") (pinfunction "11_11") (pintype "bidirectional"))
    )
    (net (code "299") (name "unconnected-(ARDUINO_DUE2-Pad12)") (class "Default")
      (node (ref "ARDUINO_DUE2") (pin "12") (pinfunction "12_12") (pintype "bidirectional"))
    )
    (net (code "300") (name "unconnected-(ARDUINO_DUE2-Pad13)") (class "Default")
      (node (ref "ARDUINO_DUE2") (pin "13") (pinfunction "13_13") (pintype "bidirectional"))
    )
    (net (code "301") (name "unconnected-(ARDUINO_DUE2-Pad22)") (class "Default")
      (node (ref "ARDUINO_DUE2") (pin "22") (pinfunction "22_22") (pintype "bidirectional"))
    )
    (net (code "302") (name "unconnected-(ARDUINO_DUE2-Pad23)") (class "Default")
      (node (ref "ARDUINO_DUE2") (pin "23") (pinfunction "23_23") (pintype "bidirectional"))
    )
    (net (code "303") (name "unconnected-(ARDUINO_DUE2-Pad24)") (class "Default")
      (node (ref "ARDUINO_DUE2") (pin "24") (pinfunction "24_24") (pintype "bidirectional"))
    )
    (net (code "304") (name "unconnected-(ARDUINO_DUE2-Pad25)") (class "Default")
      (node (ref "ARDUINO_DUE2") (pin "25") (pinfunction "25_25") (pintype "bidirectional"))
    )
    (net (code "305") (name "unconnected-(ARDUINO_DUE2-Pad26)") (class "Default")
      (node (ref "ARDUINO_DUE2") (pin "26") (pinfunction "26_26") (pintype "bidirectional"))
    )
    (net (code "306") (name "unconnected-(ARDUINO_DUE2-Pad27)") (class "Default")
      (node (ref "ARDUINO_DUE2") (pin "27") (pinfunction "27_27") (pintype "bidirectional"))
    )
    (net (code "307") (name "unconnected-(ARDUINO_DUE2-Pad28)") (class "Default")
      (node (ref "ARDUINO_DUE2") (pin "28") (pinfunction "28_28") (pintype "bidirectional"))
    )
    (net (code "308") (name "unconnected-(ARDUINO_DUE2-Pad29)") (class "Default")
      (node (ref "ARDUINO_DUE2") (pin "29") (pinfunction "29_29") (pintype "bidirectional"))
    )
    (net (code "309") (name "unconnected-(ARDUINO_DUE2-Pad30)") (class "Default")
      (node (ref "ARDUINO_DUE2") (pin "30") (pinfunction "30_30") (pintype "bidirectional"))
    )
    (net (code "310") (name "unconnected-(ARDUINO_DUE2-Pad31)") (class "Default")
      (node (ref "ARDUINO_DUE2") (pin "31") (pinfunction "31_31") (pintype "bidirectional"))
    )
    (net (code "311") (name "unconnected-(ARDUINO_DUE2-Pad32)") (class "Default")
      (node (ref "ARDUINO_DUE2") (pin "32") (pinfunction "32_32") (pintype "bidirectional"))
    )
    (net (code "312") (name "unconnected-(ARDUINO_DUE2-Pad33)") (class "Default")
      (node (ref "ARDUINO_DUE2") (pin "33") (pinfunction "33_33") (pintype "bidirectional"))
    )
    (net (code "313") (name "unconnected-(ARDUINO_DUE2-Pad34)") (class "Default")
      (node (ref "ARDUINO_DUE2") (pin "34") (pinfunction "34_34") (pintype "bidirectional"))
    )
    (net (code "314") (name "unconnected-(ARDUINO_DUE2-Pad35)") (class "Default")
      (node (ref "ARDUINO_DUE2") (pin "35") (pinfunction "35_35") (pintype "bidirectional"))
    )
    (net (code "315") (name "unconnected-(ARDUINO_DUE2-Pad36)") (class "Default")
      (node (ref "ARDUINO_DUE2") (pin "36") (pinfunction "36_36") (pintype "bidirectional"))
    )
    (net (code "316") (name "unconnected-(ARDUINO_DUE2-Pad37)") (class "Default")
      (node (ref "ARDUINO_DUE2") (pin "37") (pinfunction "37_37") (pintype "bidirectional"))
    )
    (net (code "317") (name "unconnected-(ARDUINO_DUE2-Pad38)") (class "Default")
      (node (ref "ARDUINO_DUE2") (pin "38") (pinfunction "38_38") (pintype "bidirectional"))
    )
    (net (code "318") (name "unconnected-(ARDUINO_DUE2-Pad39)") (class "Default")
      (node (ref "ARDUINO_DUE2") (pin "39") (pinfunction "39_39") (pintype "bidirectional"))
    )
    (net (code "319") (name "unconnected-(ARDUINO_DUE2-Pad40)") (class "Default")
      (node (ref "ARDUINO_DUE2") (pin "40") (pinfunction "40_40") (pintype "bidirectional"))
    )
    (net (code "320") (name "unconnected-(ARDUINO_DUE2-Pad41)") (class "Default")
      (node (ref "ARDUINO_DUE2") (pin "41") (pinfunction "41_41") (pintype "bidirectional"))
    )
    (net (code "321") (name "unconnected-(ARDUINO_DUE2-Pad42)") (class "Default")
      (node (ref "ARDUINO_DUE2") (pin "42") (pinfunction "42_42") (pintype "bidirectional"))
    )
    (net (code "322") (name "unconnected-(ARDUINO_DUE2-Pad43)") (class "Default")
      (node (ref "ARDUINO_DUE2") (pin "43") (pinfunction "43_43") (pintype "bidirectional"))
    )
    (net (code "323") (name "unconnected-(ARDUINO_DUE2-Pad44)") (class "Default")
      (node (ref "ARDUINO_DUE2") (pin "44") (pinfunction "44_44") (pintype "bidirectional"))
    )
    (net (code "324") (name "unconnected-(ARDUINO_DUE2-Pad45)") (class "Default")
      (node (ref "ARDUINO_DUE2") (pin "45") (pinfunction "45_45") (pintype "bidirectional"))
    )
    (net (code "325") (name "unconnected-(ARDUINO_DUE2-Pad46)") (class "Default")
      (node (ref "ARDUINO_DUE2") (pin "46") (pinfunction "46_46") (pintype "bidirectional"))
    )
    (net (code "326") (name "unconnected-(ARDUINO_DUE2-Pad47)") (class "Default")
      (node (ref "ARDUINO_DUE2") (pin "47") (pinfunction "47_47") (pintype "bidirectional"))
    )
    (net (code "327") (name "unconnected-(ARDUINO_DUE2-Pad48)") (class "Default")
      (node (ref "ARDUINO_DUE2") (pin "48") (pinfunction "48_48") (pintype "bidirectional"))
    )
    (net (code "328") (name "unconnected-(ARDUINO_DUE2-Pad49)") (class "Default")
      (node (ref "ARDUINO_DUE2") (pin "49") (pinfunction "49_49") (pintype "bidirectional"))
    )
    (net (code "329") (name "unconnected-(ARDUINO_DUE2-Pad50)") (class "Default")
      (node (ref "ARDUINO_DUE2") (pin "50") (pinfunction "50_50") (pintype "bidirectional"))
    )
    (net (code "330") (name "unconnected-(ARDUINO_DUE2-Pad51)") (class "Default")
      (node (ref "ARDUINO_DUE2") (pin "51") (pinfunction "51_51") (pintype "bidirectional"))
    )
    (net (code "331") (name "unconnected-(ARDUINO_DUE2-Pad52)") (class "Default")
      (node (ref "ARDUINO_DUE2") (pin "52") (pinfunction "52_52") (pintype "bidirectional"))
    )
    (net (code "332") (name "unconnected-(ARDUINO_DUE2-Pad53)") (class "Default")
      (node (ref "ARDUINO_DUE2") (pin "53") (pinfunction "53_53") (pintype "bidirectional"))
    )
    (net (code "333") (name "unconnected-(ARDUINO_DUE2-PadAREF)") (class "Default")
      (node (ref "ARDUINO_DUE2") (pin "AREF") (pinfunction "AREF_AREF") (pintype "bidirectional"))
    )
    (net (code "334") (name "unconnected-(ARDUINO_DUE2-PadGND)") (class "Default")
      (node (ref "ARDUINO_DUE2") (pin "GND") (pinfunction "GND_GND") (pintype "bidirectional"))
    )
    (net (code "335") (name "unconnected-(ARDUINO_DUE2-PadGND_ICSP1)") (class "Default")
      (node (ref "ARDUINO_DUE2") (pin "GND_ICSP1") (pinfunction "GND_ICSP1_GND_ICSP1") (pintype "bidirectional"))
    )
    (net (code "336") (name "unconnected-(ARDUINO_DUE2-PadIOREF)") (class "Default")
      (node (ref "ARDUINO_DUE2") (pin "IOREF") (pinfunction "IOREF_IOREF") (pintype "bidirectional"))
    )
    (net (code "337") (name "unconnected-(ARDUINO_DUE2-PadJTAG_RESET)") (class "Default")
      (node (ref "ARDUINO_DUE2") (pin "JTAG_RESET") (pinfunction "JTAG_RESET_JTAG_RESET") (pintype "bidirectional"))
    )
    (net (code "338") (name "unconnected-(ARDUINO_DUE2-PadJTAG_TCK)") (class "Default")
      (node (ref "ARDUINO_DUE2") (pin "JTAG_TCK") (pinfunction "JTAG_TCK_JTAG_TCK") (pintype "bidirectional"))
    )
    (net (code "339") (name "unconnected-(ARDUINO_DUE2-PadJTAG_TCK_2)") (class "Default")
      (node (ref "ARDUINO_DUE2") (pin "JTAG_TCK_2") (pinfunction "JTAG_TCK_2_JTAG_TCK_2") (pintype "bidirectional"))
    )
    (net (code "340") (name "unconnected-(ARDUINO_DUE2-PadJTAG_TDI)") (class "Default")
      (node (ref "ARDUINO_DUE2") (pin "JTAG_TDI") (pinfunction "JTAG_TDI_JTAG_TDI") (pintype "bidirectional"))
    )
    (net (code "341") (name "unconnected-(ARDUINO_DUE2-PadJTAG_TDO)") (class "Default")
      (node (ref "ARDUINO_DUE2") (pin "JTAG_TDO") (pinfunction "JTAG_TDO_JTAG_TDO") (pintype "bidirectional"))
    )
    (net (code "342") (name "unconnected-(ARDUINO_DUE2-PadJTAG_TMS)") (class "Default")
      (node (ref "ARDUINO_DUE2") (pin "JTAG_TMS") (pinfunction "JTAG_TMS_JTAG_TMS") (pintype "bidirectional"))
    )
    (net (code "343") (name "unconnected-(ARDUINO_DUE2-PadJTAG_TMS_2)") (class "Default")
      (node (ref "ARDUINO_DUE2") (pin "JTAG_TMS_2") (pinfunction "JTAG_TMS_2_JTAG_TMS_2") (pintype "bidirectional"))
    )
    (net (code "344") (name "unconnected-(ARDUINO_DUE2-PadMISO)") (class "Default")
      (node (ref "ARDUINO_DUE2") (pin "MISO") (pinfunction "MISO_MISO") (pintype "bidirectional"))
    )
    (net (code "345") (name "unconnected-(ARDUINO_DUE2-PadMISO2)") (class "Default")
      (node (ref "ARDUINO_DUE2") (pin "MISO2") (pinfunction "MISO2_MISO2") (pintype "bidirectional"))
    )
    (net (code "346") (name "unconnected-(ARDUINO_DUE2-PadMOSI)") (class "Default")
      (node (ref "ARDUINO_DUE2") (pin "MOSI") (pinfunction "MOSI_MOSI") (pintype "bidirectional"))
    )
    (net (code "347") (name "unconnected-(ARDUINO_DUE2-PadMOSI2)") (class "Default")
      (node (ref "ARDUINO_DUE2") (pin "MOSI2") (pinfunction "MOSI2_MOSI2") (pintype "bidirectional"))
    )
    (net (code "348") (name "unconnected-(ARDUINO_DUE2-PadRESET)") (class "Default")
      (node (ref "ARDUINO_DUE2") (pin "RESET") (pinfunction "RESET_RESET") (pintype "bidirectional"))
    )
    (net (code "349") (name "unconnected-(ARDUINO_DUE2-PadRESET2)") (class "Default")
      (node (ref "ARDUINO_DUE2") (pin "RESET2") (pinfunction "RESET2_RESET2") (pintype "bidirectional"))
    )
    (net (code "350") (name "unconnected-(ARDUINO_DUE2-PadSCK2)") (class "Default")
      (node (ref "ARDUINO_DUE2") (pin "SCK2") (pinfunction "SCK2_SCK2") (pintype "bidirectional"))
    )
    (net (code "351") (name "unconnected-(ARDUINO_DUE2-PadSCL1)") (class "Default")
      (node (ref "ARDUINO_DUE2") (pin "SCL1") (pinfunction "SCL1_SCL1") (pintype "bidirectional"))
    )
    (net (code "352") (name "unconnected-(ARDUINO_DUE2-PadSDA1)") (class "Default")
      (node (ref "ARDUINO_DUE2") (pin "SDA1") (pinfunction "SDA1_SDA1") (pintype "bidirectional"))
    )
    (net (code "353") (name "unconnected-(ARDUINO_DUE2-PadSPCK)") (class "Default")
      (node (ref "ARDUINO_DUE2") (pin "SPCK") (pinfunction "SPCK_SPCK") (pintype "bidirectional"))
    )
    (net (code "354") (name "unconnected-(ARDUINO_DUE2-PadVIN)") (class "Default")
      (node (ref "ARDUINO_DUE2") (pin "VIN") (pinfunction "VIN_VIN") (pintype "bidirectional"))
    )
    (net (code "355") (name "unconnected-(ARDUINO_DUE2-RX0<0-Pad0)") (class "Default")
      (node (ref "ARDUINO_DUE2") (pin "0") (pinfunction "RX0<0_0") (pintype "bidirectional"))
    )
    (net (code "356") (name "unconnected-(ARDUINO_DUE2-RX1_19-Pad19)") (class "Default")
      (node (ref "ARDUINO_DUE2") (pin "19") (pinfunction "RX1_19_19") (pintype "bidirectional"))
    )
    (net (code "357") (name "unconnected-(ARDUINO_DUE2-RX2_17-Pad17)") (class "Default")
      (node (ref "ARDUINO_DUE2") (pin "17") (pinfunction "RX2_17_17") (pintype "bidirectional"))
    )
    (net (code "358") (name "unconnected-(ARDUINO_DUE2-RX3_15-Pad15)") (class "Default")
      (node (ref "ARDUINO_DUE2") (pin "15") (pinfunction "RX3_15_15") (pintype "bidirectional"))
    )
    (net (code "359") (name "unconnected-(ARDUINO_DUE2-SCL_21-Pad21)") (class "Default")
      (node (ref "ARDUINO_DUE2") (pin "21") (pinfunction "SCL_21_21") (pintype "bidirectional"))
    )
    (net (code "360") (name "unconnected-(ARDUINO_DUE2-SDA_20-Pad20)") (class "Default")
      (node (ref "ARDUINO_DUE2") (pin "20") (pinfunction "SDA_20_20") (pintype "bidirectional"))
    )
    (net (code "361") (name "unconnected-(ARDUINO_DUE2-TX0>1-Pad1)") (class "Default")
      (node (ref "ARDUINO_DUE2") (pin "1") (pinfunction "TX0>1_1") (pintype "bidirectional"))
    )
    (net (code "362") (name "unconnected-(ARDUINO_DUE2-TX1_18-Pad18)") (class "Default")
      (node (ref "ARDUINO_DUE2") (pin "18") (pinfunction "TX1_18_18") (pintype "bidirectional"))
    )
    (net (code "363") (name "unconnected-(ARDUINO_DUE2-TX2_16-Pad16)") (class "Default")
      (node (ref "ARDUINO_DUE2") (pin "16") (pinfunction "TX2_16_16") (pintype "bidirectional"))
    )
    (net (code "364") (name "unconnected-(ARDUINO_DUE2-TX3_14-Pad14)") (class "Default")
      (node (ref "ARDUINO_DUE2") (pin "14") (pinfunction "TX3_14_14") (pintype "bidirectional"))
    )
    (net (code "365") (name "unconnected-(ARDUINO_DUE3-5V-Pad5V0)") (class "Default")
      (node (ref "ARDUINO_DUE3") (pin "5V0") (pinfunction "5V_5V0") (pintype "bidirectional"))
    )
    (net (code "366") (name "unconnected-(ARDUINO_DUE3-5V-Pad5V0_1)") (class "Default")
      (node (ref "ARDUINO_DUE3") (pin "5V0_1") (pinfunction "5V_5V0_1") (pintype "bidirectional"))
    )
    (net (code "367") (name "unconnected-(ARDUINO_DUE3-5V-Pad5V0_2)") (class "Default")
      (node (ref "ARDUINO_DUE3") (pin "5V0_2") (pinfunction "5V_5V0_2") (pintype "bidirectional"))
    )
    (net (code "368") (name "unconnected-(ARDUINO_DUE3-5V_SPI-Pad5V_2)") (class "Default")
      (node (ref "ARDUINO_DUE3") (pin "5V_2") (pinfunction "5V_SPI_5V_2") (pintype "bidirectional"))
    )
    (net (code "369") (name "unconnected-(ARDUINO_DUE3-AN0-PadA0)") (class "Default")
      (node (ref "ARDUINO_DUE3") (pin "A0") (pinfunction "AN0_A0") (pintype "bidirectional"))
    )
    (net (code "370") (name "unconnected-(ARDUINO_DUE3-AN1-PadA1)") (class "Default")
      (node (ref "ARDUINO_DUE3") (pin "A1") (pinfunction "AN1_A1") (pintype "bidirectional"))
    )
    (net (code "371") (name "unconnected-(ARDUINO_DUE3-AN2-PadA2)") (class "Default")
      (node (ref "ARDUINO_DUE3") (pin "A2") (pinfunction "AN2_A2") (pintype "bidirectional"))
    )
    (net (code "372") (name "unconnected-(ARDUINO_DUE3-AN3-PadA3)") (class "Default")
      (node (ref "ARDUINO_DUE3") (pin "A3") (pinfunction "AN3_A3") (pintype "bidirectional"))
    )
    (net (code "373") (name "unconnected-(ARDUINO_DUE3-AN4-PadA4)") (class "Default")
      (node (ref "ARDUINO_DUE3") (pin "A4") (pinfunction "AN4_A4") (pintype "bidirectional"))
    )
    (net (code "374") (name "unconnected-(ARDUINO_DUE3-AN5-PadA5)") (class "Default")
      (node (ref "ARDUINO_DUE3") (pin "A5") (pinfunction "AN5_A5") (pintype "bidirectional"))
    )
    (net (code "375") (name "unconnected-(ARDUINO_DUE3-AN6-PadA6)") (class "Default")
      (node (ref "ARDUINO_DUE3") (pin "A6") (pinfunction "AN6_A6") (pintype "bidirectional"))
    )
    (net (code "376") (name "unconnected-(ARDUINO_DUE3-AN7-PadA7)") (class "Default")
      (node (ref "ARDUINO_DUE3") (pin "A7") (pinfunction "AN7_A7") (pintype "bidirectional"))
    )
    (net (code "377") (name "unconnected-(ARDUINO_DUE3-GND-PadGND_1)") (class "Default")
      (node (ref "ARDUINO_DUE3") (pin "GND_1") (pinfunction "GND_GND_1") (pintype "bidirectional"))
    )
    (net (code "378") (name "unconnected-(ARDUINO_DUE3-GND-PadGND_2)") (class "Default")
      (node (ref "ARDUINO_DUE3") (pin "GND_2") (pinfunction "GND_GND_2") (pintype "bidirectional"))
    )
    (net (code "379") (name "unconnected-(ARDUINO_DUE3-GND-PadGND_3)") (class "Default")
      (node (ref "ARDUINO_DUE3") (pin "GND_3") (pinfunction "GND_GND_3") (pintype "bidirectional"))
    )
    (net (code "380") (name "unconnected-(ARDUINO_DUE3-GND-PadGND_4)") (class "Default")
      (node (ref "ARDUINO_DUE3") (pin "GND_4") (pinfunction "GND_GND_4") (pintype "bidirectional"))
    )
    (net (code "381") (name "unconnected-(ARDUINO_DUE3-GND-PadGND_5)") (class "Default")
      (node (ref "ARDUINO_DUE3") (pin "GND_5") (pinfunction "GND_GND_5") (pintype "bidirectional"))
    )
    (net (code "382") (name "unconnected-(ARDUINO_DUE3-GND-PadGND_7)") (class "Default")
      (node (ref "ARDUINO_DUE3") (pin "GND_7") (pinfunction "GND_GND_7") (pintype "bidirectional"))
    )
    (net (code "383") (name "unconnected-(ARDUINO_DUE3-GND-PadGND_8)") (class "Default")
      (node (ref "ARDUINO_DUE3") (pin "GND_8") (pinfunction "GND_GND_8") (pintype "bidirectional"))
    )
    (net (code "384") (name "unconnected-(ARDUINO_DUE3-GND-PadGND_9)") (class "Default")
      (node (ref "ARDUINO_DUE3") (pin "GND_9") (pinfunction "GND_GND_9") (pintype "bidirectional"))
    )
    (net (code "385") (name "unconnected-(ARDUINO_DUE3-GND-PadGND_10)") (class "Default")
      (node (ref "ARDUINO_DUE3") (pin "GND_10") (pinfunction "GND_GND_10") (pintype "bidirectional"))
    )
    (net (code "386") (name "unconnected-(ARDUINO_DUE3-MASTER_R_JTAG-PadMASTER_RESET_JTAG)") (class "Default")
      (node (ref "ARDUINO_DUE3") (pin "MASTER_RESET_JTAG") (pinfunction "MASTER_R_JTAG_MASTER_RESET_JTAG") (pintype "bidirectional"))
    )
    (net (code "387") (name "unconnected-(ARDUINO_DUE3-MASTER_R_SPI-PadMASTER_RESET_SPI)") (class "Default")
      (node (ref "ARDUINO_DUE3") (pin "MASTER_RESET_SPI") (pinfunction "MASTER_R_SPI_MASTER_RESET_SPI") (pintype "bidirectional"))
    )
    (net (code "388") (name "unconnected-(ARDUINO_DUE3-NC-PadNC_2)") (class "Default")
      (node (ref "ARDUINO_DUE3") (pin "NC_2") (pinfunction "NC_NC_2") (pintype "no_connect"))
    )
    (net (code "389") (name "unconnected-(ARDUINO_DUE3-NC-PadNC_5)") (class "Default")
      (node (ref "ARDUINO_DUE3") (pin "NC_5") (pinfunction "NC_NC_5") (pintype "bidirectional"))
    )
    (net (code "390") (name "unconnected-(ARDUINO_DUE3-Pad3V3)") (class "Default")
      (node (ref "ARDUINO_DUE3") (pin "3V3") (pinfunction "3V3_3V3") (pintype "bidirectional"))
    )
    (net (code "391") (name "unconnected-(ARDUINO_DUE3-Pad3V3_JTAG)") (class "Default")
      (node (ref "ARDUINO_DUE3") (pin "3V3_JTAG") (pinfunction "3V3_JTAG_3V3_JTAG") (pintype "bidirectional"))
    )
    (net (code "392") (name "unconnected-(ARDUINO_DUE3-Pad5V_ICSP1)") (class "Default")
      (node (ref "ARDUINO_DUE3") (pin "5V_ICSP1") (pinfunction "5V_ICSP1_5V_ICSP1") (pintype "bidirectional"))
    )
    (net (code "393") (name "unconnected-(ARDUINO_DUE3-Pad8)") (class "Default")
      (node (ref "ARDUINO_DUE3") (pin "8") (pinfunction "8_8") (pintype "bidirectional"))
    )
    (net (code "394") (name "unconnected-(ARDUINO_DUE3-Pad9)") (class "Default")
      (node (ref "ARDUINO_DUE3") (pin "9") (pinfunction "9_9") (pintype "bidirectional"))
    )
    (net (code "395") (name "unconnected-(ARDUINO_DUE3-Pad10)") (class "Default")
      (node (ref "ARDUINO_DUE3") (pin "10") (pinfunction "10_10") (pintype "bidirectional"))
    )
    (net (code "396") (name "unconnected-(ARDUINO_DUE3-Pad11)") (class "Default")
      (node (ref "ARDUINO_DUE3") (pin "11") (pinfunction "11_11") (pintype "bidirectional"))
    )
    (net (code "397") (name "unconnected-(ARDUINO_DUE3-Pad12)") (class "Default")
      (node (ref "ARDUINO_DUE3") (pin "12") (pinfunction "12_12") (pintype "bidirectional"))
    )
    (net (code "398") (name "unconnected-(ARDUINO_DUE3-Pad13)") (class "Default")
      (node (ref "ARDUINO_DUE3") (pin "13") (pinfunction "13_13") (pintype "bidirectional"))
    )
    (net (code "399") (name "unconnected-(ARDUINO_DUE3-Pad22)") (class "Default")
      (node (ref "ARDUINO_DUE3") (pin "22") (pinfunction "22_22") (pintype "bidirectional"))
    )
    (net (code "400") (name "unconnected-(ARDUINO_DUE3-Pad23)") (class "Default")
      (node (ref "ARDUINO_DUE3") (pin "23") (pinfunction "23_23") (pintype "bidirectional"))
    )
    (net (code "401") (name "unconnected-(ARDUINO_DUE3-Pad24)") (class "Default")
      (node (ref "ARDUINO_DUE3") (pin "24") (pinfunction "24_24") (pintype "bidirectional"))
    )
    (net (code "402") (name "unconnected-(ARDUINO_DUE3-Pad25)") (class "Default")
      (node (ref "ARDUINO_DUE3") (pin "25") (pinfunction "25_25") (pintype "bidirectional"))
    )
    (net (code "403") (name "unconnected-(ARDUINO_DUE3-Pad26)") (class "Default")
      (node (ref "ARDUINO_DUE3") (pin "26") (pinfunction "26_26") (pintype "bidirectional"))
    )
    (net (code "404") (name "unconnected-(ARDUINO_DUE3-Pad27)") (class "Default")
      (node (ref "ARDUINO_DUE3") (pin "27") (pinfunction "27_27") (pintype "bidirectional"))
    )
    (net (code "405") (name "unconnected-(ARDUINO_DUE3-Pad28)") (class "Default")
      (node (ref "ARDUINO_DUE3") (pin "28") (pinfunction "28_28") (pintype "bidirectional"))
    )
    (net (code "406") (name "unconnected-(ARDUINO_DUE3-Pad29)") (class "Default")
      (node (ref "ARDUINO_DUE3") (pin "29") (pinfunction "29_29") (pintype "bidirectional"))
    )
    (net (code "407") (name "unconnected-(ARDUINO_DUE3-Pad30)") (class "Default")
      (node (ref "ARDUINO_DUE3") (pin "30") (pinfunction "30_30") (pintype "bidirectional"))
    )
    (net (code "408") (name "unconnected-(ARDUINO_DUE3-Pad31)") (class "Default")
      (node (ref "ARDUINO_DUE3") (pin "31") (pinfunction "31_31") (pintype "bidirectional"))
    )
    (net (code "409") (name "unconnected-(ARDUINO_DUE3-Pad32)") (class "Default")
      (node (ref "ARDUINO_DUE3") (pin "32") (pinfunction "32_32") (pintype "bidirectional"))
    )
    (net (code "410") (name "unconnected-(ARDUINO_DUE3-Pad33)") (class "Default")
      (node (ref "ARDUINO_DUE3") (pin "33") (pinfunction "33_33") (pintype "bidirectional"))
    )
    (net (code "411") (name "unconnected-(ARDUINO_DUE3-Pad34)") (class "Default")
      (node (ref "ARDUINO_DUE3") (pin "34") (pinfunction "34_34") (pintype "bidirectional"))
    )
    (net (code "412") (name "unconnected-(ARDUINO_DUE3-Pad35)") (class "Default")
      (node (ref "ARDUINO_DUE3") (pin "35") (pinfunction "35_35") (pintype "bidirectional"))
    )
    (net (code "413") (name "unconnected-(ARDUINO_DUE3-Pad36)") (class "Default")
      (node (ref "ARDUINO_DUE3") (pin "36") (pinfunction "36_36") (pintype "bidirectional"))
    )
    (net (code "414") (name "unconnected-(ARDUINO_DUE3-Pad37)") (class "Default")
      (node (ref "ARDUINO_DUE3") (pin "37") (pinfunction "37_37") (pintype "bidirectional"))
    )
    (net (code "415") (name "unconnected-(ARDUINO_DUE3-Pad38)") (class "Default")
      (node (ref "ARDUINO_DUE3") (pin "38") (pinfunction "38_38") (pintype "bidirectional"))
    )
    (net (code "416") (name "unconnected-(ARDUINO_DUE3-Pad39)") (class "Default")
      (node (ref "ARDUINO_DUE3") (pin "39") (pinfunction "39_39") (pintype "bidirectional"))
    )
    (net (code "417") (name "unconnected-(ARDUINO_DUE3-Pad40)") (class "Default")
      (node (ref "ARDUINO_DUE3") (pin "40") (pinfunction "40_40") (pintype "bidirectional"))
    )
    (net (code "418") (name "unconnected-(ARDUINO_DUE3-Pad41)") (class "Default")
      (node (ref "ARDUINO_DUE3") (pin "41") (pinfunction "41_41") (pintype "bidirectional"))
    )
    (net (code "419") (name "unconnected-(ARDUINO_DUE3-Pad42)") (class "Default")
      (node (ref "ARDUINO_DUE3") (pin "42") (pinfunction "42_42") (pintype "bidirectional"))
    )
    (net (code "420") (name "unconnected-(ARDUINO_DUE3-Pad43)") (class "Default")
      (node (ref "ARDUINO_DUE3") (pin "43") (pinfunction "43_43") (pintype "bidirectional"))
    )
    (net (code "421") (name "unconnected-(ARDUINO_DUE3-Pad44)") (class "Default")
      (node (ref "ARDUINO_DUE3") (pin "44") (pinfunction "44_44") (pintype "bidirectional"))
    )
    (net (code "422") (name "unconnected-(ARDUINO_DUE3-Pad45)") (class "Default")
      (node (ref "ARDUINO_DUE3") (pin "45") (pinfunction "45_45") (pintype "bidirectional"))
    )
    (net (code "423") (name "unconnected-(ARDUINO_DUE3-Pad46)") (class "Default")
      (node (ref "ARDUINO_DUE3") (pin "46") (pinfunction "46_46") (pintype "bidirectional"))
    )
    (net (code "424") (name "unconnected-(ARDUINO_DUE3-Pad47)") (class "Default")
      (node (ref "ARDUINO_DUE3") (pin "47") (pinfunction "47_47") (pintype "bidirectional"))
    )
    (net (code "425") (name "unconnected-(ARDUINO_DUE3-Pad48)") (class "Default")
      (node (ref "ARDUINO_DUE3") (pin "48") (pinfunction "48_48") (pintype "bidirectional"))
    )
    (net (code "426") (name "unconnected-(ARDUINO_DUE3-Pad49)") (class "Default")
      (node (ref "ARDUINO_DUE3") (pin "49") (pinfunction "49_49") (pintype "bidirectional"))
    )
    (net (code "427") (name "unconnected-(ARDUINO_DUE3-Pad50)") (class "Default")
      (node (ref "ARDUINO_DUE3") (pin "50") (pinfunction "50_50") (pintype "bidirectional"))
    )
    (net (code "428") (name "unconnected-(ARDUINO_DUE3-Pad51)") (class "Default")
      (node (ref "ARDUINO_DUE3") (pin "51") (pinfunction "51_51") (pintype "bidirectional"))
    )
    (net (code "429") (name "unconnected-(ARDUINO_DUE3-Pad52)") (class "Default")
      (node (ref "ARDUINO_DUE3") (pin "52") (pinfunction "52_52") (pintype "bidirectional"))
    )
    (net (code "430") (name "unconnected-(ARDUINO_DUE3-Pad53)") (class "Default")
      (node (ref "ARDUINO_DUE3") (pin "53") (pinfunction "53_53") (pintype "bidirectional"))
    )
    (net (code "431") (name "unconnected-(ARDUINO_DUE3-PadAREF)") (class "Default")
      (node (ref "ARDUINO_DUE3") (pin "AREF") (pinfunction "AREF_AREF") (pintype "bidirectional"))
    )
    (net (code "432") (name "unconnected-(ARDUINO_DUE3-PadGND)") (class "Default")
      (node (ref "ARDUINO_DUE3") (pin "GND") (pinfunction "GND_GND") (pintype "bidirectional"))
    )
    (net (code "433") (name "unconnected-(ARDUINO_DUE3-PadGND_ICSP1)") (class "Default")
      (node (ref "ARDUINO_DUE3") (pin "GND_ICSP1") (pinfunction "GND_ICSP1_GND_ICSP1") (pintype "bidirectional"))
    )
    (net (code "434") (name "unconnected-(ARDUINO_DUE3-PadIOREF)") (class "Default")
      (node (ref "ARDUINO_DUE3") (pin "IOREF") (pinfunction "IOREF_IOREF") (pintype "bidirectional"))
    )
    (net (code "435") (name "unconnected-(ARDUINO_DUE3-PadJTAG_RESET)") (class "Default")
      (node (ref "ARDUINO_DUE3") (pin "JTAG_RESET") (pinfunction "JTAG_RESET_JTAG_RESET") (pintype "bidirectional"))
    )
    (net (code "436") (name "unconnected-(ARDUINO_DUE3-PadJTAG_TCK)") (class "Default")
      (node (ref "ARDUINO_DUE3") (pin "JTAG_TCK") (pinfunction "JTAG_TCK_JTAG_TCK") (pintype "bidirectional"))
    )
    (net (code "437") (name "unconnected-(ARDUINO_DUE3-PadJTAG_TCK_2)") (class "Default")
      (node (ref "ARDUINO_DUE3") (pin "JTAG_TCK_2") (pinfunction "JTAG_TCK_2_JTAG_TCK_2") (pintype "bidirectional"))
    )
    (net (code "438") (name "unconnected-(ARDUINO_DUE3-PadJTAG_TDI)") (class "Default")
      (node (ref "ARDUINO_DUE3") (pin "JTAG_TDI") (pinfunction "JTAG_TDI_JTAG_TDI") (pintype "bidirectional"))
    )
    (net (code "439") (name "unconnected-(ARDUINO_DUE3-PadJTAG_TDO)") (class "Default")
      (node (ref "ARDUINO_DUE3") (pin "JTAG_TDO") (pinfunction "JTAG_TDO_JTAG_TDO") (pintype "bidirectional"))
    )
    (net (code "440") (name "unconnected-(ARDUINO_DUE3-PadJTAG_TMS)") (class "Default")
      (node (ref "ARDUINO_DUE3") (pin "JTAG_TMS") (pinfunction "JTAG_TMS_JTAG_TMS") (pintype "bidirectional"))
    )
    (net (code "441") (name "unconnected-(ARDUINO_DUE3-PadJTAG_TMS_2)") (class "Default")
      (node (ref "ARDUINO_DUE3") (pin "JTAG_TMS_2") (pinfunction "JTAG_TMS_2_JTAG_TMS_2") (pintype "bidirectional"))
    )
    (net (code "442") (name "unconnected-(ARDUINO_DUE3-PadMISO)") (class "Default")
      (node (ref "ARDUINO_DUE3") (pin "MISO") (pinfunction "MISO_MISO") (pintype "bidirectional"))
    )
    (net (code "443") (name "unconnected-(ARDUINO_DUE3-PadMISO2)") (class "Default")
      (node (ref "ARDUINO_DUE3") (pin "MISO2") (pinfunction "MISO2_MISO2") (pintype "bidirectional"))
    )
    (net (code "444") (name "unconnected-(ARDUINO_DUE3-PadMOSI)") (class "Default")
      (node (ref "ARDUINO_DUE3") (pin "MOSI") (pinfunction "MOSI_MOSI") (pintype "bidirectional"))
    )
    (net (code "445") (name "unconnected-(ARDUINO_DUE3-PadMOSI2)") (class "Default")
      (node (ref "ARDUINO_DUE3") (pin "MOSI2") (pinfunction "MOSI2_MOSI2") (pintype "bidirectional"))
    )
    (net (code "446") (name "unconnected-(ARDUINO_DUE3-PadRESET)") (class "Default")
      (node (ref "ARDUINO_DUE3") (pin "RESET") (pinfunction "RESET_RESET") (pintype "bidirectional"))
    )
    (net (code "447") (name "unconnected-(ARDUINO_DUE3-PadRESET2)") (class "Default")
      (node (ref "ARDUINO_DUE3") (pin "RESET2") (pinfunction "RESET2_RESET2") (pintype "bidirectional"))
    )
    (net (code "448") (name "unconnected-(ARDUINO_DUE3-PadSCK2)") (class "Default")
      (node (ref "ARDUINO_DUE3") (pin "SCK2") (pinfunction "SCK2_SCK2") (pintype "bidirectional"))
    )
    (net (code "449") (name "unconnected-(ARDUINO_DUE3-PadSCL1)") (class "Default")
      (node (ref "ARDUINO_DUE3") (pin "SCL1") (pinfunction "SCL1_SCL1") (pintype "bidirectional"))
    )
    (net (code "450") (name "unconnected-(ARDUINO_DUE3-PadSDA1)") (class "Default")
      (node (ref "ARDUINO_DUE3") (pin "SDA1") (pinfunction "SDA1_SDA1") (pintype "bidirectional"))
    )
    (net (code "451") (name "unconnected-(ARDUINO_DUE3-PadSPCK)") (class "Default")
      (node (ref "ARDUINO_DUE3") (pin "SPCK") (pinfunction "SPCK_SPCK") (pintype "bidirectional"))
    )
    (net (code "452") (name "unconnected-(ARDUINO_DUE3-PadVIN)") (class "Default")
      (node (ref "ARDUINO_DUE3") (pin "VIN") (pinfunction "VIN_VIN") (pintype "bidirectional"))
    )
    (net (code "453") (name "unconnected-(ARDUINO_DUE3-RX0<0-Pad0)") (class "Default")
      (node (ref "ARDUINO_DUE3") (pin "0") (pinfunction "RX0<0_0") (pintype "bidirectional"))
    )
    (net (code "454") (name "unconnected-(ARDUINO_DUE3-RX1_19-Pad19)") (class "Default")
      (node (ref "ARDUINO_DUE3") (pin "19") (pinfunction "RX1_19_19") (pintype "bidirectional"))
    )
    (net (code "455") (name "unconnected-(ARDUINO_DUE3-RX2_17-Pad17)") (class "Default")
      (node (ref "ARDUINO_DUE3") (pin "17") (pinfunction "RX2_17_17") (pintype "bidirectional"))
    )
    (net (code "456") (name "unconnected-(ARDUINO_DUE3-RX3_15-Pad15)") (class "Default")
      (node (ref "ARDUINO_DUE3") (pin "15") (pinfunction "RX3_15_15") (pintype "bidirectional"))
    )
    (net (code "457") (name "unconnected-(ARDUINO_DUE3-SCL_21-Pad21)") (class "Default")
      (node (ref "ARDUINO_DUE3") (pin "21") (pinfunction "SCL_21_21") (pintype "bidirectional"))
    )
    (net (code "458") (name "unconnected-(ARDUINO_DUE3-SDA_20-Pad20)") (class "Default")
      (node (ref "ARDUINO_DUE3") (pin "20") (pinfunction "SDA_20_20") (pintype "bidirectional"))
    )
    (net (code "459") (name "unconnected-(ARDUINO_DUE3-TX0>1-Pad1)") (class "Default")
      (node (ref "ARDUINO_DUE3") (pin "1") (pinfunction "TX0>1_1") (pintype "bidirectional"))
    )
    (net (code "460") (name "unconnected-(ARDUINO_DUE3-TX1_18-Pad18)") (class "Default")
      (node (ref "ARDUINO_DUE3") (pin "18") (pinfunction "TX1_18_18") (pintype "bidirectional"))
    )
    (net (code "461") (name "unconnected-(ARDUINO_DUE3-TX2_16-Pad16)") (class "Default")
      (node (ref "ARDUINO_DUE3") (pin "16") (pinfunction "TX2_16_16") (pintype "bidirectional"))
    )
    (net (code "462") (name "unconnected-(ARDUINO_DUE3-TX3_14-Pad14)") (class "Default")
      (node (ref "ARDUINO_DUE3") (pin "14") (pinfunction "TX3_14_14") (pintype "bidirectional"))
    )
    (net (code "463") (name "unconnected-(ARDUINO_DUE4-5V-Pad5V0)") (class "Default")
      (node (ref "ARDUINO_DUE4") (pin "5V0") (pinfunction "5V_5V0") (pintype "bidirectional"))
    )
    (net (code "464") (name "unconnected-(ARDUINO_DUE4-5V-Pad5V0_1)") (class "Default")
      (node (ref "ARDUINO_DUE4") (pin "5V0_1") (pinfunction "5V_5V0_1") (pintype "bidirectional"))
    )
    (net (code "465") (name "unconnected-(ARDUINO_DUE4-5V-Pad5V0_2)") (class "Default")
      (node (ref "ARDUINO_DUE4") (pin "5V0_2") (pinfunction "5V_5V0_2") (pintype "bidirectional"))
    )
    (net (code "466") (name "unconnected-(ARDUINO_DUE4-5V_SPI-Pad5V_2)") (class "Default")
      (node (ref "ARDUINO_DUE4") (pin "5V_2") (pinfunction "5V_SPI_5V_2") (pintype "bidirectional"))
    )
    (net (code "467") (name "unconnected-(ARDUINO_DUE4-AN0-PadA0)") (class "Default")
      (node (ref "ARDUINO_DUE4") (pin "A0") (pinfunction "AN0_A0") (pintype "bidirectional"))
    )
    (net (code "468") (name "unconnected-(ARDUINO_DUE4-AN1-PadA1)") (class "Default")
      (node (ref "ARDUINO_DUE4") (pin "A1") (pinfunction "AN1_A1") (pintype "bidirectional"))
    )
    (net (code "469") (name "unconnected-(ARDUINO_DUE4-AN2-PadA2)") (class "Default")
      (node (ref "ARDUINO_DUE4") (pin "A2") (pinfunction "AN2_A2") (pintype "bidirectional"))
    )
    (net (code "470") (name "unconnected-(ARDUINO_DUE4-AN3-PadA3)") (class "Default")
      (node (ref "ARDUINO_DUE4") (pin "A3") (pinfunction "AN3_A3") (pintype "bidirectional"))
    )
    (net (code "471") (name "unconnected-(ARDUINO_DUE4-AN4-PadA4)") (class "Default")
      (node (ref "ARDUINO_DUE4") (pin "A4") (pinfunction "AN4_A4") (pintype "bidirectional"))
    )
    (net (code "472") (name "unconnected-(ARDUINO_DUE4-AN5-PadA5)") (class "Default")
      (node (ref "ARDUINO_DUE4") (pin "A5") (pinfunction "AN5_A5") (pintype "bidirectional"))
    )
    (net (code "473") (name "unconnected-(ARDUINO_DUE4-AN6-PadA6)") (class "Default")
      (node (ref "ARDUINO_DUE4") (pin "A6") (pinfunction "AN6_A6") (pintype "bidirectional"))
    )
    (net (code "474") (name "unconnected-(ARDUINO_DUE4-AN7-PadA7)") (class "Default")
      (node (ref "ARDUINO_DUE4") (pin "A7") (pinfunction "AN7_A7") (pintype "bidirectional"))
    )
    (net (code "475") (name "unconnected-(ARDUINO_DUE4-GND-PadGND_1)") (class "Default")
      (node (ref "ARDUINO_DUE4") (pin "GND_1") (pinfunction "GND_GND_1") (pintype "bidirectional"))
    )
    (net (code "476") (name "unconnected-(ARDUINO_DUE4-GND-PadGND_2)") (class "Default")
      (node (ref "ARDUINO_DUE4") (pin "GND_2") (pinfunction "GND_GND_2") (pintype "bidirectional"))
    )
    (net (code "477") (name "unconnected-(ARDUINO_DUE4-GND-PadGND_3)") (class "Default")
      (node (ref "ARDUINO_DUE4") (pin "GND_3") (pinfunction "GND_GND_3") (pintype "bidirectional"))
    )
    (net (code "478") (name "unconnected-(ARDUINO_DUE4-GND-PadGND_4)") (class "Default")
      (node (ref "ARDUINO_DUE4") (pin "GND_4") (pinfunction "GND_GND_4") (pintype "bidirectional"))
    )
    (net (code "479") (name "unconnected-(ARDUINO_DUE4-GND-PadGND_5)") (class "Default")
      (node (ref "ARDUINO_DUE4") (pin "GND_5") (pinfunction "GND_GND_5") (pintype "bidirectional"))
    )
    (net (code "480") (name "unconnected-(ARDUINO_DUE4-GND-PadGND_7)") (class "Default")
      (node (ref "ARDUINO_DUE4") (pin "GND_7") (pinfunction "GND_GND_7") (pintype "bidirectional"))
    )
    (net (code "481") (name "unconnected-(ARDUINO_DUE4-GND-PadGND_8)") (class "Default")
      (node (ref "ARDUINO_DUE4") (pin "GND_8") (pinfunction "GND_GND_8") (pintype "bidirectional"))
    )
    (net (code "482") (name "unconnected-(ARDUINO_DUE4-GND-PadGND_9)") (class "Default")
      (node (ref "ARDUINO_DUE4") (pin "GND_9") (pinfunction "GND_GND_9") (pintype "bidirectional"))
    )
    (net (code "483") (name "unconnected-(ARDUINO_DUE4-GND-PadGND_10)") (class "Default")
      (node (ref "ARDUINO_DUE4") (pin "GND_10") (pinfunction "GND_GND_10") (pintype "bidirectional"))
    )
    (net (code "484") (name "unconnected-(ARDUINO_DUE4-MASTER_R_JTAG-PadMASTER_RESET_JTAG)") (class "Default")
      (node (ref "ARDUINO_DUE4") (pin "MASTER_RESET_JTAG") (pinfunction "MASTER_R_JTAG_MASTER_RESET_JTAG") (pintype "bidirectional"))
    )
    (net (code "485") (name "unconnected-(ARDUINO_DUE4-MASTER_R_SPI-PadMASTER_RESET_SPI)") (class "Default")
      (node (ref "ARDUINO_DUE4") (pin "MASTER_RESET_SPI") (pinfunction "MASTER_R_SPI_MASTER_RESET_SPI") (pintype "bidirectional"))
    )
    (net (code "486") (name "unconnected-(ARDUINO_DUE4-NC-PadNC_2)") (class "Default")
      (node (ref "ARDUINO_DUE4") (pin "NC_2") (pinfunction "NC_NC_2") (pintype "no_connect"))
    )
    (net (code "487") (name "unconnected-(ARDUINO_DUE4-NC-PadNC_5)") (class "Default")
      (node (ref "ARDUINO_DUE4") (pin "NC_5") (pinfunction "NC_NC_5") (pintype "bidirectional"))
    )
    (net (code "488") (name "unconnected-(ARDUINO_DUE4-Pad3V3)") (class "Default")
      (node (ref "ARDUINO_DUE4") (pin "3V3") (pinfunction "3V3_3V3") (pintype "bidirectional"))
    )
    (net (code "489") (name "unconnected-(ARDUINO_DUE4-Pad3V3_JTAG)") (class "Default")
      (node (ref "ARDUINO_DUE4") (pin "3V3_JTAG") (pinfunction "3V3_JTAG_3V3_JTAG") (pintype "bidirectional"))
    )
    (net (code "490") (name "unconnected-(ARDUINO_DUE4-Pad5V_ICSP1)") (class "Default")
      (node (ref "ARDUINO_DUE4") (pin "5V_ICSP1") (pinfunction "5V_ICSP1_5V_ICSP1") (pintype "bidirectional"))
    )
    (net (code "491") (name "unconnected-(ARDUINO_DUE4-Pad8)") (class "Default")
      (node (ref "ARDUINO_DUE4") (pin "8") (pinfunction "8_8") (pintype "bidirectional"))
    )
    (net (code "492") (name "unconnected-(ARDUINO_DUE4-Pad9)") (class "Default")
      (node (ref "ARDUINO_DUE4") (pin "9") (pinfunction "9_9") (pintype "bidirectional"))
    )
    (net (code "493") (name "unconnected-(ARDUINO_DUE4-Pad10)") (class "Default")
      (node (ref "ARDUINO_DUE4") (pin "10") (pinfunction "10_10") (pintype "bidirectional"))
    )
    (net (code "494") (name "unconnected-(ARDUINO_DUE4-Pad11)") (class "Default")
      (node (ref "ARDUINO_DUE4") (pin "11") (pinfunction "11_11") (pintype "bidirectional"))
    )
    (net (code "495") (name "unconnected-(ARDUINO_DUE4-Pad12)") (class "Default")
      (node (ref "ARDUINO_DUE4") (pin "12") (pinfunction "12_12") (pintype "bidirectional"))
    )
    (net (code "496") (name "unconnected-(ARDUINO_DUE4-Pad13)") (class "Default")
      (node (ref "ARDUINO_DUE4") (pin "13") (pinfunction "13_13") (pintype "bidirectional"))
    )
    (net (code "497") (name "unconnected-(ARDUINO_DUE4-Pad22)") (class "Default")
      (node (ref "ARDUINO_DUE4") (pin "22") (pinfunction "22_22") (pintype "bidirectional"))
    )
    (net (code "498") (name "unconnected-(ARDUINO_DUE4-Pad23)") (class "Default")
      (node (ref "ARDUINO_DUE4") (pin "23") (pinfunction "23_23") (pintype "bidirectional"))
    )
    (net (code "499") (name "unconnected-(ARDUINO_DUE4-Pad24)") (class "Default")
      (node (ref "ARDUINO_DUE4") (pin "24") (pinfunction "24_24") (pintype "bidirectional"))
    )
    (net (code "500") (name "unconnected-(ARDUINO_DUE4-Pad25)") (class "Default")
      (node (ref "ARDUINO_DUE4") (pin "25") (pinfunction "25_25") (pintype "bidirectional"))
    )
    (net (code "501") (name "unconnected-(ARDUINO_DUE4-Pad26)") (class "Default")
      (node (ref "ARDUINO_DUE4") (pin "26") (pinfunction "26_26") (pintype "bidirectional"))
    )
    (net (code "502") (name "unconnected-(ARDUINO_DUE4-Pad27)") (class "Default")
      (node (ref "ARDUINO_DUE4") (pin "27") (pinfunction "27_27") (pintype "bidirectional"))
    )
    (net (code "503") (name "unconnected-(ARDUINO_DUE4-Pad28)") (class "Default")
      (node (ref "ARDUINO_DUE4") (pin "28") (pinfunction "28_28") (pintype "bidirectional"))
    )
    (net (code "504") (name "unconnected-(ARDUINO_DUE4-Pad29)") (class "Default")
      (node (ref "ARDUINO_DUE4") (pin "29") (pinfunction "29_29") (pintype "bidirectional"))
    )
    (net (code "505") (name "unconnected-(ARDUINO_DUE4-Pad30)") (class "Default")
      (node (ref "ARDUINO_DUE4") (pin "30") (pinfunction "30_30") (pintype "bidirectional"))
    )
    (net (code "506") (name "unconnected-(ARDUINO_DUE4-Pad31)") (class "Default")
      (node (ref "ARDUINO_DUE4") (pin "31") (pinfunction "31_31") (pintype "bidirectional"))
    )
    (net (code "507") (name "unconnected-(ARDUINO_DUE4-Pad32)") (class "Default")
      (node (ref "ARDUINO_DUE4") (pin "32") (pinfunction "32_32") (pintype "bidirectional"))
    )
    (net (code "508") (name "unconnected-(ARDUINO_DUE4-Pad33)") (class "Default")
      (node (ref "ARDUINO_DUE4") (pin "33") (pinfunction "33_33") (pintype "bidirectional"))
    )
    (net (code "509") (name "unconnected-(ARDUINO_DUE4-Pad34)") (class "Default")
      (node (ref "ARDUINO_DUE4") (pin "34") (pinfunction "34_34") (pintype "bidirectional"))
    )
    (net (code "510") (name "unconnected-(ARDUINO_DUE4-Pad35)") (class "Default")
      (node (ref "ARDUINO_DUE4") (pin "35") (pinfunction "35_35") (pintype "bidirectional"))
    )
    (net (code "511") (name "unconnected-(ARDUINO_DUE4-Pad36)") (class "Default")
      (node (ref "ARDUINO_DUE4") (pin "36") (pinfunction "36_36") (pintype "bidirectional"))
    )
    (net (code "512") (name "unconnected-(ARDUINO_DUE4-Pad37)") (class "Default")
      (node (ref "ARDUINO_DUE4") (pin "37") (pinfunction "37_37") (pintype "bidirectional"))
    )
    (net (code "513") (name "unconnected-(ARDUINO_DUE4-Pad38)") (class "Default")
      (node (ref "ARDUINO_DUE4") (pin "38") (pinfunction "38_38") (pintype "bidirectional"))
    )
    (net (code "514") (name "unconnected-(ARDUINO_DUE4-Pad39)") (class "Default")
      (node (ref "ARDUINO_DUE4") (pin "39") (pinfunction "39_39") (pintype "bidirectional"))
    )
    (net (code "515") (name "unconnected-(ARDUINO_DUE4-Pad40)") (class "Default")
      (node (ref "ARDUINO_DUE4") (pin "40") (pinfunction "40_40") (pintype "bidirectional"))
    )
    (net (code "516") (name "unconnected-(ARDUINO_DUE4-Pad41)") (class "Default")
      (node (ref "ARDUINO_DUE4") (pin "41") (pinfunction "41_41") (pintype "bidirectional"))
    )
    (net (code "517") (name "unconnected-(ARDUINO_DUE4-Pad42)") (class "Default")
      (node (ref "ARDUINO_DUE4") (pin "42") (pinfunction "42_42") (pintype "bidirectional"))
    )
    (net (code "518") (name "unconnected-(ARDUINO_DUE4-Pad43)") (class "Default")
      (node (ref "ARDUINO_DUE4") (pin "43") (pinfunction "43_43") (pintype "bidirectional"))
    )
    (net (code "519") (name "unconnected-(ARDUINO_DUE4-Pad44)") (class "Default")
      (node (ref "ARDUINO_DUE4") (pin "44") (pinfunction "44_44") (pintype "bidirectional"))
    )
    (net (code "520") (name "unconnected-(ARDUINO_DUE4-Pad45)") (class "Default")
      (node (ref "ARDUINO_DUE4") (pin "45") (pinfunction "45_45") (pintype "bidirectional"))
    )
    (net (code "521") (name "unconnected-(ARDUINO_DUE4-Pad46)") (class "Default")
      (node (ref "ARDUINO_DUE4") (pin "46") (pinfunction "46_46") (pintype "bidirectional"))
    )
    (net (code "522") (name "unconnected-(ARDUINO_DUE4-Pad47)") (class "Default")
      (node (ref "ARDUINO_DUE4") (pin "47") (pinfunction "47_47") (pintype "bidirectional"))
    )
    (net (code "523") (name "unconnected-(ARDUINO_DUE4-Pad48)") (class "Default")
      (node (ref "ARDUINO_DUE4") (pin "48") (pinfunction "48_48") (pintype "bidirectional"))
    )
    (net (code "524") (name "unconnected-(ARDUINO_DUE4-Pad49)") (class "Default")
      (node (ref "ARDUINO_DUE4") (pin "49") (pinfunction "49_49") (pintype "bidirectional"))
    )
    (net (code "525") (name "unconnected-(ARDUINO_DUE4-Pad50)") (class "Default")
      (node (ref "ARDUINO_DUE4") (pin "50") (pinfunction "50_50") (pintype "bidirectional"))
    )
    (net (code "526") (name "unconnected-(ARDUINO_DUE4-Pad51)") (class "Default")
      (node (ref "ARDUINO_DUE4") (pin "51") (pinfunction "51_51") (pintype "bidirectional"))
    )
    (net (code "527") (name "unconnected-(ARDUINO_DUE4-Pad52)") (class "Default")
      (node (ref "ARDUINO_DUE4") (pin "52") (pinfunction "52_52") (pintype "bidirectional"))
    )
    (net (code "528") (name "unconnected-(ARDUINO_DUE4-Pad53)") (class "Default")
      (node (ref "ARDUINO_DUE4") (pin "53") (pinfunction "53_53") (pintype "bidirectional"))
    )
    (net (code "529") (name "unconnected-(ARDUINO_DUE4-PadAREF)") (class "Default")
      (node (ref "ARDUINO_DUE4") (pin "AREF") (pinfunction "AREF_AREF") (pintype "bidirectional"))
    )
    (net (code "530") (name "unconnected-(ARDUINO_DUE4-PadGND)") (class "Default")
      (node (ref "ARDUINO_DUE4") (pin "GND") (pinfunction "GND_GND") (pintype "bidirectional"))
    )
    (net (code "531") (name "unconnected-(ARDUINO_DUE4-PadGND_ICSP1)") (class "Default")
      (node (ref "ARDUINO_DUE4") (pin "GND_ICSP1") (pinfunction "GND_ICSP1_GND_ICSP1") (pintype "bidirectional"))
    )
    (net (code "532") (name "unconnected-(ARDUINO_DUE4-PadIOREF)") (class "Default")
      (node (ref "ARDUINO_DUE4") (pin "IOREF") (pinfunction "IOREF_IOREF") (pintype "bidirectional"))
    )
    (net (code "533") (name "unconnected-(ARDUINO_DUE4-PadJTAG_RESET)") (class "Default")
      (node (ref "ARDUINO_DUE4") (pin "JTAG_RESET") (pinfunction "JTAG_RESET_JTAG_RESET") (pintype "bidirectional"))
    )
    (net (code "534") (name "unconnected-(ARDUINO_DUE4-PadJTAG_TCK)") (class "Default")
      (node (ref "ARDUINO_DUE4") (pin "JTAG_TCK") (pinfunction "JTAG_TCK_JTAG_TCK") (pintype "bidirectional"))
    )
    (net (code "535") (name "unconnected-(ARDUINO_DUE4-PadJTAG_TCK_2)") (class "Default")
      (node (ref "ARDUINO_DUE4") (pin "JTAG_TCK_2") (pinfunction "JTAG_TCK_2_JTAG_TCK_2") (pintype "bidirectional"))
    )
    (net (code "536") (name "unconnected-(ARDUINO_DUE4-PadJTAG_TDI)") (class "Default")
      (node (ref "ARDUINO_DUE4") (pin "JTAG_TDI") (pinfunction "JTAG_TDI_JTAG_TDI") (pintype "bidirectional"))
    )
    (net (code "537") (name "unconnected-(ARDUINO_DUE4-PadJTAG_TDO)") (class "Default")
      (node (ref "ARDUINO_DUE4") (pin "JTAG_TDO") (pinfunction "JTAG_TDO_JTAG_TDO") (pintype "bidirectional"))
    )
    (net (code "538") (name "unconnected-(ARDUINO_DUE4-PadJTAG_TMS)") (class "Default")
      (node (ref "ARDUINO_DUE4") (pin "JTAG_TMS") (pinfunction "JTAG_TMS_JTAG_TMS") (pintype "bidirectional"))
    )
    (net (code "539") (name "unconnected-(ARDUINO_DUE4-PadJTAG_TMS_2)") (class "Default")
      (node (ref "ARDUINO_DUE4") (pin "JTAG_TMS_2") (pinfunction "JTAG_TMS_2_JTAG_TMS_2") (pintype "bidirectional"))
    )
    (net (code "540") (name "unconnected-(ARDUINO_DUE4-PadMISO)") (class "Default")
      (node (ref "ARDUINO_DUE4") (pin "MISO") (pinfunction "MISO_MISO") (pintype "bidirectional"))
    )
    (net (code "541") (name "unconnected-(ARDUINO_DUE4-PadMISO2)") (class "Default")
      (node (ref "ARDUINO_DUE4") (pin "MISO2") (pinfunction "MISO2_MISO2") (pintype "bidirectional"))
    )
    (net (code "542") (name "unconnected-(ARDUINO_DUE4-PadMOSI)") (class "Default")
      (node (ref "ARDUINO_DUE4") (pin "MOSI") (pinfunction "MOSI_MOSI") (pintype "bidirectional"))
    )
    (net (code "543") (name "unconnected-(ARDUINO_DUE4-PadMOSI2)") (class "Default")
      (node (ref "ARDUINO_DUE4") (pin "MOSI2") (pinfunction "MOSI2_MOSI2") (pintype "bidirectional"))
    )
    (net (code "544") (name "unconnected-(ARDUINO_DUE4-PadRESET)") (class "Default")
      (node (ref "ARDUINO_DUE4") (pin "RESET") (pinfunction "RESET_RESET") (pintype "bidirectional"))
    )
    (net (code "545") (name "unconnected-(ARDUINO_DUE4-PadRESET2)") (class "Default")
      (node (ref "ARDUINO_DUE4") (pin "RESET2") (pinfunction "RESET2_RESET2") (pintype "bidirectional"))
    )
    (net (code "546") (name "unconnected-(ARDUINO_DUE4-PadSCK2)") (class "Default")
      (node (ref "ARDUINO_DUE4") (pin "SCK2") (pinfunction "SCK2_SCK2") (pintype "bidirectional"))
    )
    (net (code "547") (name "unconnected-(ARDUINO_DUE4-PadSCL1)") (class "Default")
      (node (ref "ARDUINO_DUE4") (pin "SCL1") (pinfunction "SCL1_SCL1") (pintype "bidirectional"))
    )
    (net (code "548") (name "unconnected-(ARDUINO_DUE4-PadSDA1)") (class "Default")
      (node (ref "ARDUINO_DUE4") (pin "SDA1") (pinfunction "SDA1_SDA1") (pintype "bidirectional"))
    )
    (net (code "549") (name "unconnected-(ARDUINO_DUE4-PadSPCK)") (class "Default")
      (node (ref "ARDUINO_DUE4") (pin "SPCK") (pinfunction "SPCK_SPCK") (pintype "bidirectional"))
    )
    (net (code "550") (name "unconnected-(ARDUINO_DUE4-PadVIN)") (class "Default")
      (node (ref "ARDUINO_DUE4") (pin "VIN") (pinfunction "VIN_VIN") (pintype "bidirectional"))
    )
    (net (code "551") (name "unconnected-(ARDUINO_DUE4-RX0<0-Pad0)") (class "Default")
      (node (ref "ARDUINO_DUE4") (pin "0") (pinfunction "RX0<0_0") (pintype "bidirectional"))
    )
    (net (code "552") (name "unconnected-(ARDUINO_DUE4-RX1_19-Pad19)") (class "Default")
      (node (ref "ARDUINO_DUE4") (pin "19") (pinfunction "RX1_19_19") (pintype "bidirectional"))
    )
    (net (code "553") (name "unconnected-(ARDUINO_DUE4-RX2_17-Pad17)") (class "Default")
      (node (ref "ARDUINO_DUE4") (pin "17") (pinfunction "RX2_17_17") (pintype "bidirectional"))
    )
    (net (code "554") (name "unconnected-(ARDUINO_DUE4-RX3_15-Pad15)") (class "Default")
      (node (ref "ARDUINO_DUE4") (pin "15") (pinfunction "RX3_15_15") (pintype "bidirectional"))
    )
    (net (code "555") (name "unconnected-(ARDUINO_DUE4-SCL_21-Pad21)") (class "Default")
      (node (ref "ARDUINO_DUE4") (pin "21") (pinfunction "SCL_21_21") (pintype "bidirectional"))
    )
    (net (code "556") (name "unconnected-(ARDUINO_DUE4-SDA_20-Pad20)") (class "Default")
      (node (ref "ARDUINO_DUE4") (pin "20") (pinfunction "SDA_20_20") (pintype "bidirectional"))
    )
    (net (code "557") (name "unconnected-(ARDUINO_DUE4-TX0>1-Pad1)") (class "Default")
      (node (ref "ARDUINO_DUE4") (pin "1") (pinfunction "TX0>1_1") (pintype "bidirectional"))
    )
    (net (code "558") (name "unconnected-(ARDUINO_DUE4-TX1_18-Pad18)") (class "Default")
      (node (ref "ARDUINO_DUE4") (pin "18") (pinfunction "TX1_18_18") (pintype "bidirectional"))
    )
    (net (code "559") (name "unconnected-(ARDUINO_DUE4-TX2_16-Pad16)") (class "Default")
      (node (ref "ARDUINO_DUE4") (pin "16") (pinfunction "TX2_16_16") (pintype "bidirectional"))
    )
    (net (code "560") (name "unconnected-(ARDUINO_DUE4-TX3_14-Pad14)") (class "Default")
      (node (ref "ARDUINO_DUE4") (pin "14") (pinfunction "TX3_14_14") (pintype "bidirectional"))
    )
    (net (code "561") (name "unconnected-(J1-Pad1)") (class "Default")
      (node (ref "J1") (pin "1") (pinfunction "1_1") (pintype "passive"))
    )
    (net (code "562") (name "unconnected-(J1-Pad2)") (class "Default")
      (node (ref "J1") (pin "2") (pinfunction "2_2") (pintype "passive"))
    )
    (net (code "563") (name "unconnected-(J3-Pad1)") (class "Default")
      (node (ref "J3") (pin "1") (pinfunction "1_1") (pintype "passive"))
    )
    (net (code "564") (name "unconnected-(J3-Pad2)") (class "Default")
      (node (ref "J3") (pin "2") (pinfunction "2_2") (pintype "passive"))
    )
    (net (code "565") (name "unconnected-(J7-Pad1)") (class "Default")
      (node (ref "J7") (pin "1") (pinfunction "1_1") (pintype "passive"))
    )
    (net (code "566") (name "unconnected-(J7-Pad2)") (class "Default")
      (node (ref "J7") (pin "2") (pinfunction "2_2") (pintype "passive"))
    )
    (net (code "567") (name "unconnected-(J10-Pad1)") (class "Default")
      (node (ref "J10") (pin "1") (pinfunction "1_1") (pintype "passive"))
    )
    (net (code "568") (name "unconnected-(J10-Pad2)") (class "Default")
      (node (ref "J10") (pin "2") (pinfunction "2_2") (pintype "passive"))
    )
    (net (code "569") (name "unconnected-(S1-P-Pad4)") (class "Default")
      (node (ref "S1") (pin "4") (pinfunction "P_4") (pintype "passive"))
    )
    (net (code "570") (name "unconnected-(S1-S-Pad5)") (class "Default")
      (node (ref "S1") (pin "5") (pinfunction "S_5") (pintype "passive"))
    )
    (net (code "571") (name "unconnected-(S2-P-Pad4)") (class "Default")
      (node (ref "S2") (pin "4") (pinfunction "P_4") (pintype "passive"))
    )
    (net (code "572") (name "unconnected-(S2-S-Pad5)") (class "Default")
      (node (ref "S2") (pin "5") (pinfunction "S_5") (pintype "passive"))
    )
    (net (code "573") (name "unconnected-(S3-P-Pad4)") (class "Default")
      (node (ref "S3") (pin "4") (pinfunction "P_4") (pintype "passive"))
    )
    (net (code "574") (name "unconnected-(S3-S-Pad5)") (class "Default")
      (node (ref "S3") (pin "5") (pinfunction "S_5") (pintype "passive"))
    )
    (net (code "575") (name "unconnected-(S4-P-Pad4)") (class "Default")
      (node (ref "S4") (pin "4") (pinfunction "P_4") (pintype "passive"))
    )
    (net (code "576") (name "unconnected-(S4-S-Pad5)") (class "Default")
      (node (ref "S4") (pin "5") (pinfunction "S_5") (pintype "passive"))
    )
  )
)
